# VCFA_v2_mix.net
KiCad netlist of a schematic drawn in EAGLE
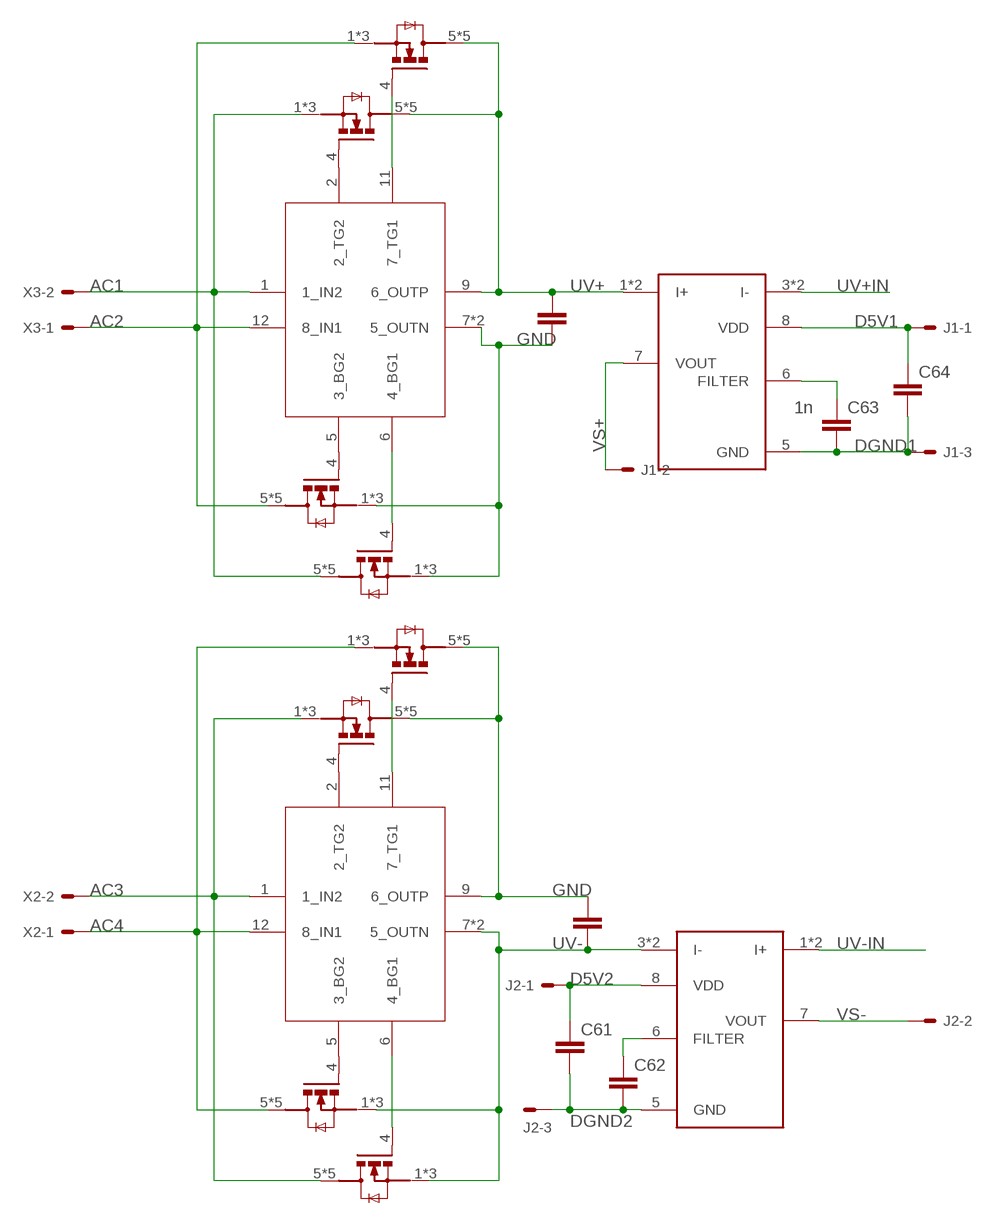
[diagram p0: schematic, sheet 1]
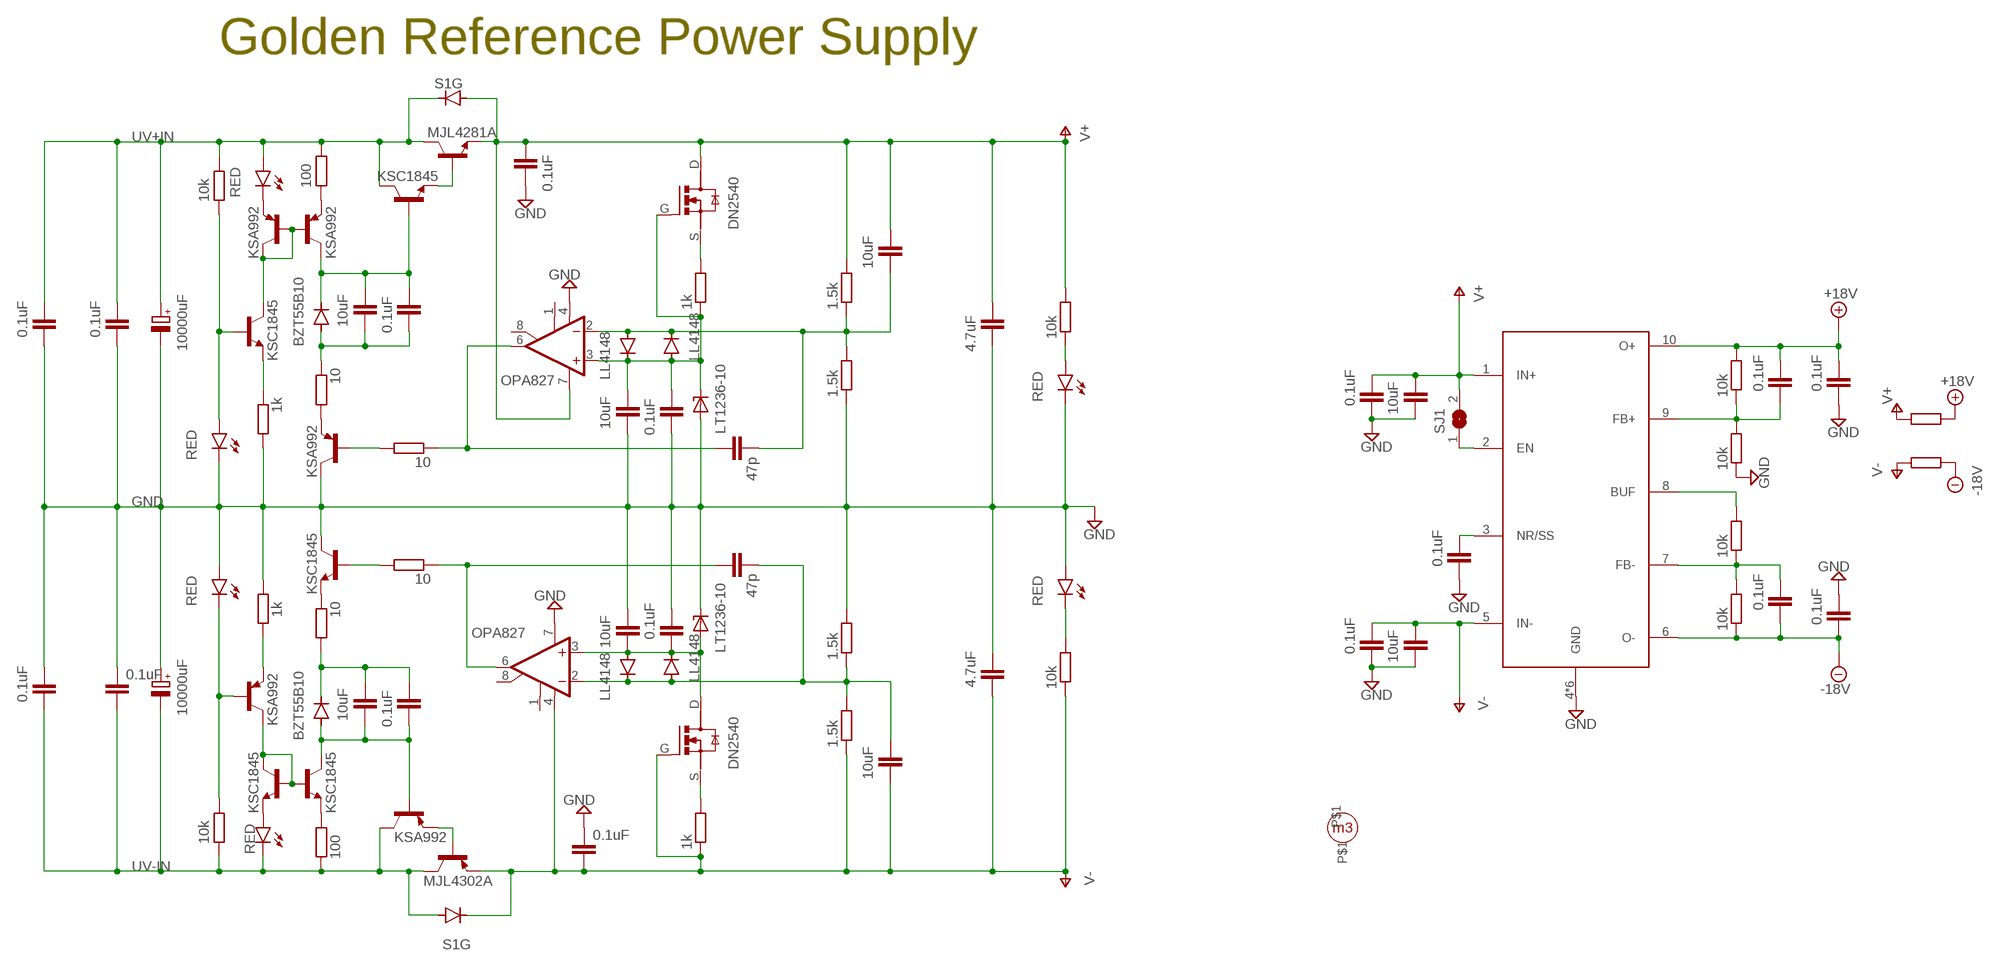
[diagram p1: schematic, sheet 2]
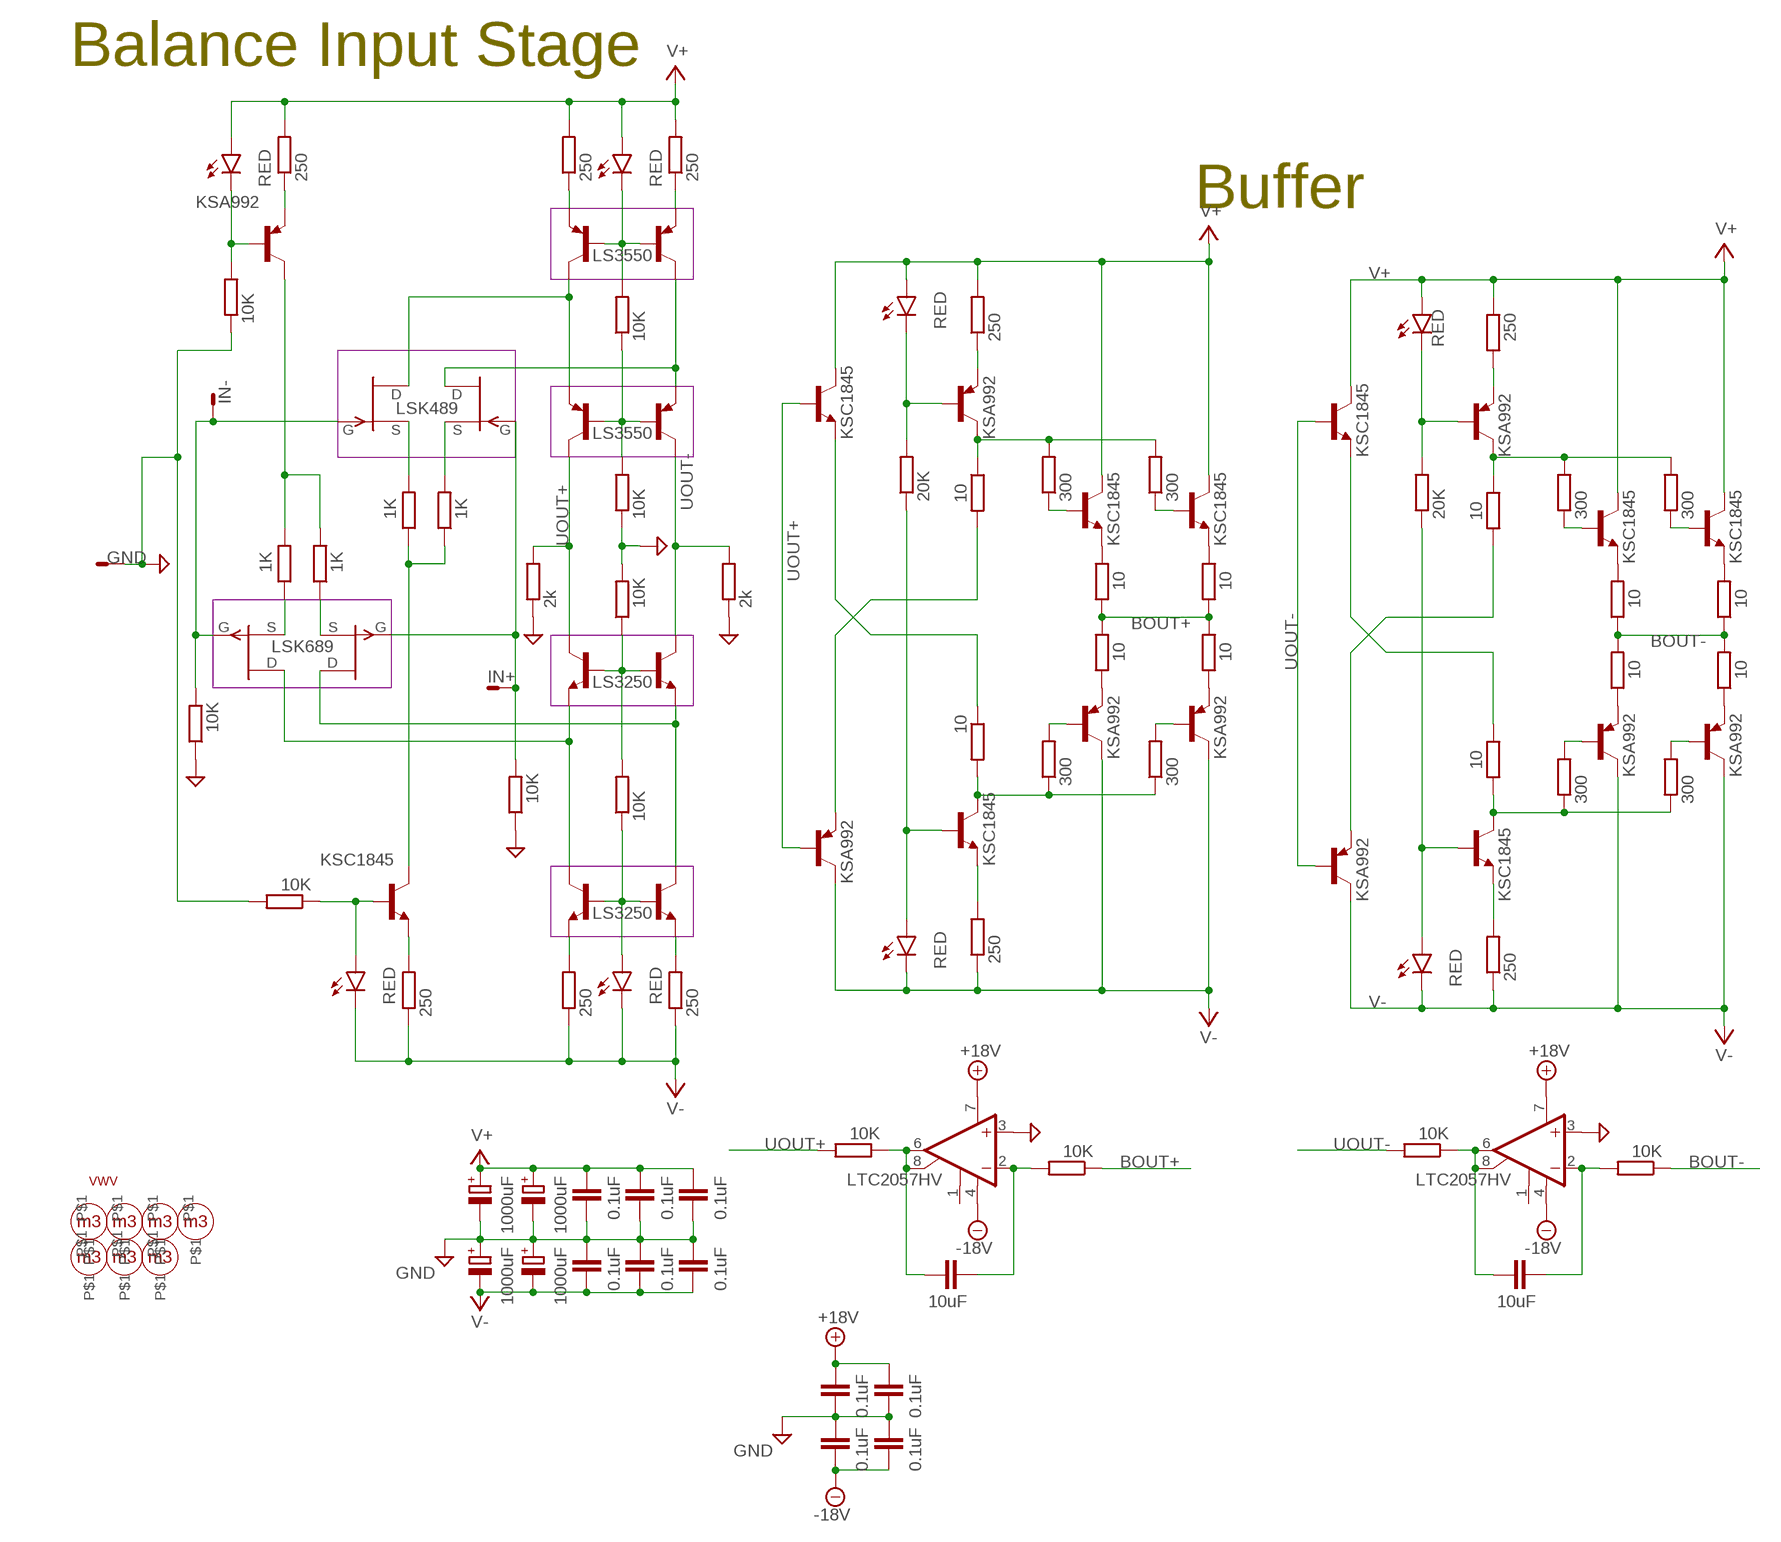
[diagram p2: schematic, sheet 3]
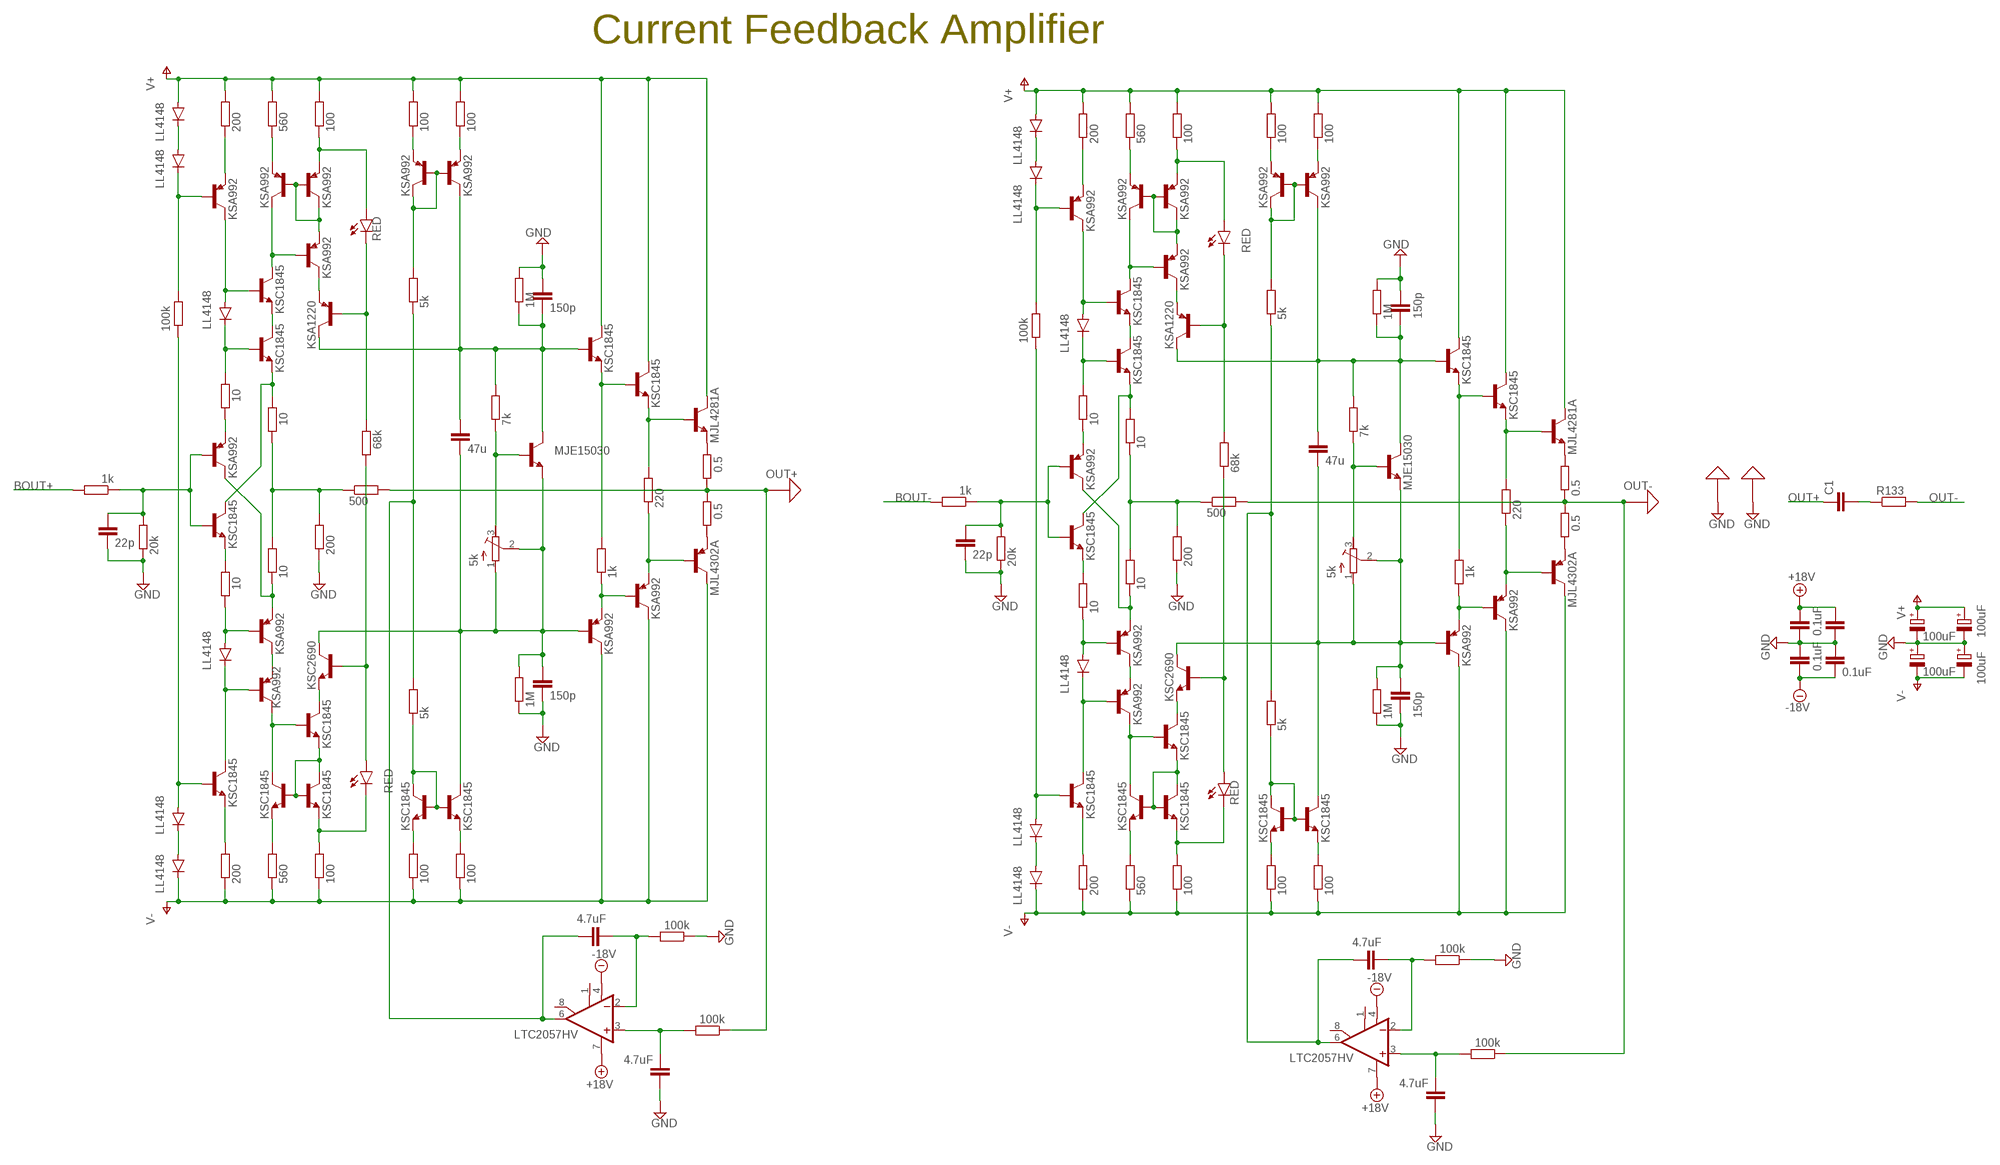
[diagram p3: schematic, sheet 4]

(export (version "E")
  (design (tool "Eeschema 10.0.6"))
  (components
    (comp (ref "C57")
      (value "47uF")
      (footprint "eagle-import:C1206")
      (libsource (lib "eagle-import") (part "C-EUC1206"))
    )
    (comp (ref "C59")
      (value "47uF")
      (footprint "eagle-import:C1206")
      (libsource (lib "eagle-import") (part "C-EUC1206"))
    )
    (comp (ref "C61")
      (value "C-EUC0805")
      (footprint "eagle-import:C0805")
      (libsource (lib "eagle-import") (part "C-EUC0805"))
    )
    (comp (ref "C62")
      (value "C-EUC0805")
      (footprint "eagle-import:C0805")
      (libsource (lib "eagle-import") (part "C-EUC0805"))
    )
    (comp (ref "C63")
      (value "1n")
      (footprint "eagle-import:C0805")
      (libsource (lib "eagle-import") (part "C-EUC0805"))
    )
    (comp (ref "C64")
      (value "C-EUC0805")
      (footprint "eagle-import:C0805")
      (libsource (lib "eagle-import") (part "C-EUC0805"))
    )
    (comp (ref "J1")
      (value "22-27-2031-03")
      (footprint "eagle-import:6410-03")
      (fields (field (name "MF") "MOLEX"))
      (libsource (lib "eagle-import") (part "22-?-0327-2031"))
    )
    (comp (ref "J2")
      (value "22-27-2031-03")
      (footprint "eagle-import:6410-03")
      (fields (field (name "MF") "MOLEX"))
      (libsource (lib "eagle-import") (part "22-?-0327-2031"))
    )
    (comp (ref "Q97")
      (value "MOS_SMDTDSON-8")
      (footprint "eagle-import:PG-TDSON-8")
      (libsource (lib "eagle-import") (part "MOS_SMDTDSON-8"))
    )
    (comp (ref "Q98")
      (value "MOS_SMDTDSON-8")
      (footprint "eagle-import:PG-TDSON-8")
      (libsource (lib "eagle-import") (part "MOS_SMDTDSON-8"))
    )
    (comp (ref "Q99")
      (value "MOS_SMDTDSON-8")
      (footprint "eagle-import:PG-TDSON-8")
      (libsource (lib "eagle-import") (part "MOS_SMDTDSON-8"))
    )
    (comp (ref "Q100")
      (value "MOS_SMDTDSON-8")
      (footprint "eagle-import:PG-TDSON-8")
      (libsource (lib "eagle-import") (part "MOS_SMDTDSON-8"))
    )
    (comp (ref "Q105")
      (value "MOS_SMDTDSON-8")
      (footprint "eagle-import:PG-TDSON-8")
      (libsource (lib "eagle-import") (part "MOS_SMDTDSON-8"))
    )
    (comp (ref "Q106")
      (value "MOS_SMDTDSON-8")
      (footprint "eagle-import:PG-TDSON-8")
      (libsource (lib "eagle-import") (part "MOS_SMDTDSON-8"))
    )
    (comp (ref "Q107")
      (value "MOS_SMDTDSON-8")
      (footprint "eagle-import:PG-TDSON-8")
      (libsource (lib "eagle-import") (part "MOS_SMDTDSON-8"))
    )
    (comp (ref "Q108")
      (value "MOS_SMDTDSON-8")
      (footprint "eagle-import:PG-TDSON-8")
      (libsource (lib "eagle-import") (part "MOS_SMDTDSON-8"))
    )
    (comp (ref "U$1")
      (value "ACHS-712X")
      (footprint "eagle-import:SO8")
      (libsource (lib "eagle-import") (part "ACHS-712X"))
    )
    (comp (ref "U$2")
      (value "LT4320MSOP")
      (footprint "eagle-import:LT4320_MSOP")
      (libsource (lib "eagle-import") (part "LT4320MSOP"))
    )
    (comp (ref "U$3")
      (value "ACHS-712X")
      (footprint "eagle-import:SO8")
      (libsource (lib "eagle-import") (part "ACHS-712X"))
    )
    (comp (ref "U$4")
      (value "LT4320MSOP")
      (footprint "eagle-import:LT4320_MSOP")
      (libsource (lib "eagle-import") (part "LT4320MSOP"))
    )
    (comp (ref "X2")
      (value "KK-156-2")
      (footprint "eagle-import:KK-156-2")
      (fields (field (name "MF") "MOLEX"))
      (libsource (lib "eagle-import") (part "KK-156-2"))
    )
    (comp (ref "X3")
      (value "KK-156-2")
      (footprint "eagle-import:KK-156-2")
      (fields (field (name "MF") "MOLEX"))
      (libsource (lib "eagle-import") (part "KK-156-2"))
    )
    (comp (ref "C3")
      (value "0.1uF")
      (footprint "eagle-import:C0805")
      (libsource (lib "eagle-import") (part "C-EUC0805"))
    )
    (comp (ref "C4")
      (value "0.1uF")
      (footprint "eagle-import:C0805")
      (libsource (lib "eagle-import") (part "C-EUC0805"))
    )
    (comp (ref "C5")
      (value "1000uF")
      (footprint "eagle-import:E7,5-18")
      (libsource (lib "eagle-import") (part "CPOL-EUE7.5-18"))
    )
    (comp (ref "C6")
      (value "1000uF")
      (footprint "eagle-import:E7,5-18")
      (libsource (lib "eagle-import") (part "CPOL-EUE7.5-18"))
    )
    (comp (ref "C7")
      (value "1000uF")
      (footprint "eagle-import:E7,5-18")
      (libsource (lib "eagle-import") (part "CPOL-EUE7.5-18"))
    )
    (comp (ref "C8")
      (value "1000uF")
      (footprint "eagle-import:E7,5-18")
      (libsource (lib "eagle-import") (part "CPOL-EUE7.5-18"))
    )
    (comp (ref "C9")
      (value "0.1uF")
      (footprint "eagle-import:C050-045X075")
      (libsource (lib "eagle-import") (part "C-EU050-045X075"))
    )
    (comp (ref "C10")
      (value "0.1uF")
      (footprint "eagle-import:C050-045X075")
      (libsource (lib "eagle-import") (part "C-EU050-045X075"))
    )
    (comp (ref "C11")
      (value "0.1uF")
      (footprint "eagle-import:C050-045X075")
      (libsource (lib "eagle-import") (part "C-EU050-045X075"))
    )
    (comp (ref "C12")
      (value "0.1uF")
      (footprint "eagle-import:C050-045X075")
      (libsource (lib "eagle-import") (part "C-EU050-045X075"))
    )
    (comp (ref "C13")
      (value "10uF")
      (footprint "eagle-import:C1206")
      (libsource (lib "eagle-import") (part "C-EUC1206"))
    )
    (comp (ref "C14")
      (value "0.1uF")
      (footprint "eagle-import:C0805")
      (libsource (lib "eagle-import") (part "C-EUC0805"))
    )
    (comp (ref "C15")
      (value "0.1uF")
      (footprint "eagle-import:C0805")
      (libsource (lib "eagle-import") (part "C-EUC0805"))
    )
    (comp (ref "C16")
      (value "10uF")
      (footprint "eagle-import:C1206")
      (libsource (lib "eagle-import") (part "C-EUC1206"))
    )
    (comp (ref "C74")
      (value "0.1uF")
      (footprint "eagle-import:C050-045X075")
      (libsource (lib "eagle-import") (part "C-EU050-045X075"))
    )
    (comp (ref "C75")
      (value "0.1uF")
      (footprint "eagle-import:C050-045X075")
      (libsource (lib "eagle-import") (part "C-EU050-045X075"))
    )
    (comp (ref "H1")
      (value "HOLE")
      (footprint "eagle-import:M3_HOLE")
      (libsource (lib "eagle-import") (part "HOLE"))
    )
    (comp (ref "H2")
      (value "HOLE")
      (footprint "eagle-import:M3_HOLE")
      (libsource (lib "eagle-import") (part "HOLE"))
    )
    (comp (ref "H3")
      (value "HOLE")
      (footprint "eagle-import:M3_HOLE")
      (libsource (lib "eagle-import") (part "HOLE"))
    )
    (comp (ref "H4")
      (value "HOLE")
      (footprint "eagle-import:M3_HOLE")
      (libsource (lib "eagle-import") (part "HOLE"))
    )
    (comp (ref "H5")
      (value "HOLE")
      (footprint "eagle-import:M3_HOLE")
      (libsource (lib "eagle-import") (part "HOLE"))
    )
    (comp (ref "H6")
      (value "HOLE")
      (footprint "eagle-import:M3_HOLE")
      (libsource (lib "eagle-import") (part "HOLE"))
    )
    (comp (ref "H7")
      (value "HOLE")
      (footprint "eagle-import:M3_HOLE")
      (libsource (lib "eagle-import") (part "HOLE"))
    )
    (comp (ref "IC1")
      (value "LTC2057HV")
      (footprint "eagle-import:SOIC8")
      (libsource (lib "eagle-import") (part "LT10S807C"))
    )
    (comp (ref "IC2")
      (value "LTC2057HV")
      (footprint "eagle-import:SOIC8")
      (libsource (lib "eagle-import") (part "LT10S807C"))
    )
    (comp (ref "LED1")
      (value "RED")
      (footprint "eagle-import:LED_SML1206")
      (libsource (lib "eagle-import") (part "LEDVWV1206"))
    )
    (comp (ref "LED2")
      (value "RED")
      (footprint "eagle-import:LED_SML1206")
      (fields (field (name "SPICEPREFIX") "D"))
      (libsource (lib "eagle-import") (part "LEDVWV1206"))
    )
    (comp (ref "LED3")
      (value "RED")
      (footprint "eagle-import:LED_SML1206")
      (libsource (lib "eagle-import") (part "LEDVWV1206"))
    )
    (comp (ref "LED4")
      (value "RED")
      (footprint "eagle-import:LED_SML1206")
      (libsource (lib "eagle-import") (part "LEDVWV1206"))
    )
    (comp (ref "LED5")
      (value "RED")
      (footprint "eagle-import:LED_SML1206")
      (libsource (lib "eagle-import") (part "LEDVWV1206"))
    )
    (comp (ref "LED6")
      (value "RED")
      (footprint "eagle-import:LED_SML1206")
      (libsource (lib "eagle-import") (part "LEDVWV1206"))
    )
    (comp (ref "LED7")
      (value "RED")
      (footprint "eagle-import:LED_SML1206")
      (libsource (lib "eagle-import") (part "LEDVWV1206"))
    )
    (comp (ref "LED8")
      (value "RED")
      (footprint "eagle-import:LED_SML1206")
      (libsource (lib "eagle-import") (part "LEDVWV1206"))
    )
    (comp (ref "Q1")
      (value "LSK689")
      (footprint "eagle-import:SOT-23-6")
      (libsource (lib "eagle-import") (part "LSK689"))
    )
    (comp (ref "Q2")
      (value "KSA992")
      (footprint "eagle-import:TRANSISTOR_TO92-ECB_P")
      (libsource (lib "eagle-import") (part "BJT_PNPKSA992"))
    )
    (comp (ref "Q3")
      (value "KSC1845")
      (footprint "eagle-import:TRANSISTOR_TO92-ECB_N")
      (libsource (lib "eagle-import") (part "BJT_NPNKSC1845"))
    )
    (comp (ref "Q4")
      (value "LSK489")
      (footprint "eagle-import:SOT-23-6")
      (libsource (lib "eagle-import") (part "LSK489SOP-6"))
    )
    (comp (ref "Q5")
      (value "LS3550")
      (footprint "eagle-import:SOT-23-6")
      (libsource (lib "eagle-import") (part "LS3550"))
    )
    (comp (ref "Q6")
      (value "LS3250")
      (footprint "eagle-import:SOT-23-6")
      (libsource (lib "eagle-import") (part "LS3250"))
    )
    (comp (ref "Q7")
      (value "LS3250")
      (footprint "eagle-import:SOT-23-6")
      (libsource (lib "eagle-import") (part "LS3250"))
    )
    (comp (ref "Q8")
      (value "LS3550")
      (footprint "eagle-import:SOT-23-6")
      (libsource (lib "eagle-import") (part "LS3550"))
    )
    (comp (ref "Q9")
      (value "KSC1845")
      (footprint "eagle-import:TRANSISTOR_TO92-ECB_N")
      (libsource (lib "eagle-import") (part "BJT_NPNKSC1845"))
    )
    (comp (ref "Q10")
      (value "KSA992")
      (footprint "eagle-import:TRANSISTOR_TO92-ECB_P")
      (libsource (lib "eagle-import") (part "BJT_PNPKSA992"))
    )
    (comp (ref "Q11")
      (value "KSA992")
      (footprint "eagle-import:TRANSISTOR_TO92-ECB_P")
      (libsource (lib "eagle-import") (part "BJT_PNPKSA992"))
    )
    (comp (ref "Q12")
      (value "KSC1845")
      (footprint "eagle-import:TRANSISTOR_TO92-ECB_N")
      (libsource (lib "eagle-import") (part "BJT_NPNKSC1845"))
    )
    (comp (ref "Q13")
      (value "KSC1845")
      (footprint "eagle-import:TRANSISTOR_TO92-ECB_N")
      (libsource (lib "eagle-import") (part "BJT_NPNKSC1845"))
    )
    (comp (ref "Q14")
      (value "KSA992")
      (footprint "eagle-import:TRANSISTOR_TO92-ECB_P")
      (libsource (lib "eagle-import") (part "BJT_PNPKSA992"))
    )
    (comp (ref "Q15")
      (value "KSC1845")
      (footprint "eagle-import:TRANSISTOR_TO92-ECB_N")
      (libsource (lib "eagle-import") (part "BJT_NPNKSC1845"))
    )
    (comp (ref "Q16")
      (value "KSA992")
      (footprint "eagle-import:TRANSISTOR_TO92-ECB_P")
      (libsource (lib "eagle-import") (part "BJT_PNPKSA992"))
    )
    (comp (ref "Q17")
      (value "KSC1845")
      (footprint "eagle-import:TRANSISTOR_TO92-ECB_N")
      (libsource (lib "eagle-import") (part "BJT_NPNKSC1845"))
    )
    (comp (ref "Q18")
      (value "KSA992")
      (footprint "eagle-import:TRANSISTOR_TO92-ECB_P")
      (libsource (lib "eagle-import") (part "BJT_PNPKSA992"))
    )
    (comp (ref "Q19")
      (value "KSA992")
      (footprint "eagle-import:TRANSISTOR_TO92-ECB_P")
      (libsource (lib "eagle-import") (part "BJT_PNPKSA992"))
    )
    (comp (ref "Q20")
      (value "KSC1845")
      (footprint "eagle-import:TRANSISTOR_TO92-ECB_N")
      (libsource (lib "eagle-import") (part "BJT_NPNKSC1845"))
    )
    (comp (ref "Q21")
      (value "KSC1845")
      (footprint "eagle-import:TRANSISTOR_TO92-ECB_N")
      (libsource (lib "eagle-import") (part "BJT_NPNKSC1845"))
    )
    (comp (ref "Q22")
      (value "KSA992")
      (footprint "eagle-import:TRANSISTOR_TO92-ECB_P")
      (libsource (lib "eagle-import") (part "BJT_PNPKSA992"))
    )
    (comp (ref "Q23")
      (value "KSC1845")
      (footprint "eagle-import:TRANSISTOR_TO92-ECB_N")
      (libsource (lib "eagle-import") (part "BJT_NPNKSC1845"))
    )
    (comp (ref "Q24")
      (value "KSA992")
      (footprint "eagle-import:TRANSISTOR_TO92-ECB_P")
      (libsource (lib "eagle-import") (part "BJT_PNPKSA992"))
    )
    (comp (ref "R3")
      (value "10K")
      (footprint "eagle-import:MINI_MELF-0204W")
      (libsource (lib "eagle-import") (part "R-EU_MELF0204W"))
    )
    (comp (ref "R4")
      (value "10K")
      (footprint "eagle-import:MINI_MELF-0204W")
      (libsource (lib "eagle-import") (part "R-EU_MELF0204W"))
    )
    (comp (ref "R5")
      (value "250")
      (footprint "eagle-import:MINI_MELF-0204W")
      (libsource (lib "eagle-import") (part "R-EU_MELF0204W"))
    )
    (comp (ref "R6")
      (value "1K")
      (footprint "eagle-import:MINI_MELF-0204W")
      (libsource (lib "eagle-import") (part "R-EU_MELF0204W"))
    )
    (comp (ref "R7")
      (value "250")
      (footprint "eagle-import:MINI_MELF-0204W")
      (fields (field (name "SPICEPREFIX") "R"))
      (libsource (lib "eagle-import") (part "R-EU_MELF0204W"))
    )
    (comp (ref "R8")
      (value "1K")
      (footprint "eagle-import:MINI_MELF-0204W")
      (libsource (lib "eagle-import") (part "R-EU_MELF0204W"))
    )
    (comp (ref "R9")
      (value "1K")
      (footprint "eagle-import:MINI_MELF-0204W")
      (libsource (lib "eagle-import") (part "R-EU_MELF0204W"))
    )
    (comp (ref "R10")
      (value "1K")
      (footprint "eagle-import:MINI_MELF-0204W")
      (libsource (lib "eagle-import") (part "R-EU_MELF0204W"))
    )
    (comp (ref "R11")
      (value "2k")
      (footprint "eagle-import:MINI_MELF-0204W")
      (libsource (lib "eagle-import") (part "R-EU_MELF0204W"))
    )
    (comp (ref "R12")
      (value "250")
      (footprint "eagle-import:MINI_MELF-0204W")
      (libsource (lib "eagle-import") (part "R-EU_MELF0204W"))
    )
    (comp (ref "R13")
      (value "250")
      (footprint "eagle-import:MINI_MELF-0204W")
      (libsource (lib "eagle-import") (part "R-EU_MELF0204W"))
    )
    (comp (ref "R14")
      (value "10K")
      (footprint "eagle-import:MINI_MELF-0204W")
      (libsource (lib "eagle-import") (part "R-EU_MELF0204W"))
    )
    (comp (ref "R15")
      (value "10K")
      (footprint "eagle-import:MINI_MELF-0204W")
      (libsource (lib "eagle-import") (part "R-EU_MELF0204W"))
    )
    (comp (ref "R16")
      (value "10K")
      (footprint "eagle-import:MINI_MELF-0204W")
      (libsource (lib "eagle-import") (part "R-EU_MELF0204W"))
    )
    (comp (ref "R17")
      (value "10K")
      (footprint "eagle-import:MINI_MELF-0204W")
      (libsource (lib "eagle-import") (part "R-EU_MELF0204W"))
    )
    (comp (ref "R18")
      (value "250")
      (footprint "eagle-import:MINI_MELF-0204W")
      (libsource (lib "eagle-import") (part "R-EU_MELF0204W"))
    )
    (comp (ref "R19")
      (value "250")
      (footprint "eagle-import:MINI_MELF-0204W")
      (libsource (lib "eagle-import") (part "R-EU_MELF0204W"))
    )
    (comp (ref "R20")
      (value "2k")
      (footprint "eagle-import:MINI_MELF-0204W")
      (libsource (lib "eagle-import") (part "R-EU_MELF0204W"))
    )
    (comp (ref "R21")
      (value "10K")
      (footprint "eagle-import:MINI_MELF-0204W")
      (libsource (lib "eagle-import") (part "R-EU_MELF0204W"))
    )
    (comp (ref "R22")
      (value "20K")
      (footprint "eagle-import:MINI_MELF-0204W")
      (libsource (lib "eagle-import") (part "R-EU_MELF0204W"))
    )
    (comp (ref "R23")
      (value "250")
      (footprint "eagle-import:MINI_MELF-0204W")
      (libsource (lib "eagle-import") (part "R-EU_MELF0204W"))
    )
    (comp (ref "R24")
      (value "10")
      (footprint "eagle-import:MINI_MELF-0204W")
      (libsource (lib "eagle-import") (part "R-EU_MELF0204W"))
    )
    (comp (ref "R25")
      (value "10")
      (footprint "eagle-import:MINI_MELF-0204W")
      (libsource (lib "eagle-import") (part "R-EU_MELF0204W"))
    )
    (comp (ref "R26")
      (value "250")
      (footprint "eagle-import:MINI_MELF-0204W")
      (libsource (lib "eagle-import") (part "R-EU_MELF0204W"))
    )
    (comp (ref "R27")
      (value "300")
      (footprint "eagle-import:MINI_MELF-0204W")
      (libsource (lib "eagle-import") (part "R-EU_MELF0204W"))
    )
    (comp (ref "R28")
      (value "300")
      (footprint "eagle-import:MINI_MELF-0204W")
      (libsource (lib "eagle-import") (part "R-EU_MELF0204W"))
    )
    (comp (ref "R29")
      (value "10K")
      (footprint "eagle-import:MINI_MELF-0204W")
      (libsource (lib "eagle-import") (part "R-EU_MELF0204W"))
    )
    (comp (ref "R30")
      (value "10")
      (footprint "eagle-import:MINI_MELF-0204W")
      (libsource (lib "eagle-import") (part "R-EU_MELF0204W"))
    )
    (comp (ref "R31")
      (value "10")
      (footprint "eagle-import:MINI_MELF-0204W")
      (libsource (lib "eagle-import") (part "R-EU_MELF0204W"))
    )
    (comp (ref "R32")
      (value "300")
      (footprint "eagle-import:MINI_MELF-0204W")
      (libsource (lib "eagle-import") (part "R-EU_MELF0204W"))
    )
    (comp (ref "R33")
      (value "300")
      (footprint "eagle-import:MINI_MELF-0204W")
      (libsource (lib "eagle-import") (part "R-EU_MELF0204W"))
    )
    (comp (ref "R34")
      (value "10")
      (footprint "eagle-import:MINI_MELF-0204W")
      (libsource (lib "eagle-import") (part "R-EU_MELF0204W"))
    )
    (comp (ref "R35")
      (value "10")
      (footprint "eagle-import:MINI_MELF-0204W")
      (libsource (lib "eagle-import") (part "R-EU_MELF0204W"))
    )
    (comp (ref "R36")
      (value "10K")
      (footprint "eagle-import:MINI_MELF-0204W")
      (libsource (lib "eagle-import") (part "R-EU_MELF0204W"))
    )
    (comp (ref "R37")
      (value "20K")
      (footprint "eagle-import:MINI_MELF-0204W")
      (libsource (lib "eagle-import") (part "R-EU_MELF0204W"))
    )
    (comp (ref "R38")
      (value "250")
      (footprint "eagle-import:MINI_MELF-0204W")
      (libsource (lib "eagle-import") (part "R-EU_MELF0204W"))
    )
    (comp (ref "R39")
      (value "10")
      (footprint "eagle-import:MINI_MELF-0204W")
      (libsource (lib "eagle-import") (part "R-EU_MELF0204W"))
    )
    (comp (ref "R40")
      (value "10")
      (footprint "eagle-import:MINI_MELF-0204W")
      (libsource (lib "eagle-import") (part "R-EU_MELF0204W"))
    )
    (comp (ref "R41")
      (value "250")
      (footprint "eagle-import:MINI_MELF-0204W")
      (libsource (lib "eagle-import") (part "R-EU_MELF0204W"))
    )
    (comp (ref "R42")
      (value "300")
      (footprint "eagle-import:MINI_MELF-0204W")
      (libsource (lib "eagle-import") (part "R-EU_MELF0204W"))
    )
    (comp (ref "R43")
      (value "300")
      (footprint "eagle-import:MINI_MELF-0204W")
      (libsource (lib "eagle-import") (part "R-EU_MELF0204W"))
    )
    (comp (ref "R44")
      (value "10K")
      (footprint "eagle-import:MINI_MELF-0204W")
      (libsource (lib "eagle-import") (part "R-EU_MELF0204W"))
    )
    (comp (ref "R45")
      (value "10")
      (footprint "eagle-import:MINI_MELF-0204W")
      (libsource (lib "eagle-import") (part "R-EU_MELF0204W"))
    )
    (comp (ref "R46")
      (value "10")
      (footprint "eagle-import:MINI_MELF-0204W")
      (libsource (lib "eagle-import") (part "R-EU_MELF0204W"))
    )
    (comp (ref "R47")
      (value "300")
      (footprint "eagle-import:MINI_MELF-0204W")
      (libsource (lib "eagle-import") (part "R-EU_MELF0204W"))
    )
    (comp (ref "R48")
      (value "300")
      (footprint "eagle-import:MINI_MELF-0204W")
      (libsource (lib "eagle-import") (part "R-EU_MELF0204W"))
    )
    (comp (ref "R49")
      (value "10")
      (footprint "eagle-import:MINI_MELF-0204W")
      (libsource (lib "eagle-import") (part "R-EU_MELF0204W"))
    )
    (comp (ref "R50")
      (value "10")
      (footprint "eagle-import:MINI_MELF-0204W")
      (libsource (lib "eagle-import") (part "R-EU_MELF0204W"))
    )
    (comp (ref "R134")
      (value "10K")
      (footprint "eagle-import:MINI_MELF-0204W")
      (libsource (lib "eagle-import") (part "R-EU_MELF0204W"))
    )
    (comp (ref "R135")
      (value "10K")
      (footprint "eagle-import:MINI_MELF-0204W")
      (libsource (lib "eagle-import") (part "R-EU_MELF0204W"))
    )
    (comp (ref "S1")
      (value "VWV")
      (footprint "eagle-import:VWV")
      (libsource (lib "eagle-import") (part "VWV"))
    )
    (comp (ref "X1")
      (value "KK-156-3")
      (footprint "eagle-import:KK-156-3")
      (fields (field (name "MF") "MOLEX"))
      (libsource (lib "eagle-import") (part "KK-156-3"))
    )
    (comp (ref "C2")
      (value "0.1uF")
      (footprint "eagle-import:C0805")
      (libsource (lib "eagle-import") (part "C-EUC0805"))
    )
    (comp (ref "C37")
      (value "10000uF")
      (footprint "eagle-import:EB35D-8.5")
      (libsource (lib "eagle-import") (part "CPOL-EU"))
    )
    (comp (ref "C38")
      (value "10000uF")
      (footprint "eagle-import:EB35D-8.5")
      (libsource (lib "eagle-import") (part "CPOL-EU"))
    )
    (comp (ref "C39")
      (value "0.1uF")
      (footprint "eagle-import:C050-045X075")
      (libsource (lib "eagle-import") (part "C-EU050-045X075"))
    )
    (comp (ref "C40")
      (value "10uF")
      (footprint "eagle-import:C1206")
      (libsource (lib "eagle-import") (part "C-EUC1206"))
    )
    (comp (ref "C41")
      (value "10uF")
      (footprint "eagle-import:C1206")
      (libsource (lib "eagle-import") (part "C-EUC1206"))
    )
    (comp (ref "C42")
      (value "0.1uF")
      (footprint "eagle-import:C050-045X075")
      (libsource (lib "eagle-import") (part "C-EU050-045X075"))
    )
    (comp (ref "C43")
      (value "0.1uF")
      (footprint "eagle-import:C0805")
      (libsource (lib "eagle-import") (part "C-EUC0805"))
    )
    (comp (ref "C44")
      (value "0.1uF")
      (footprint "eagle-import:C0805")
      (libsource (lib "eagle-import") (part "C-EUC0805"))
    )
    (comp (ref "C45")
      (value "0.1uF")
      (footprint "eagle-import:C0805")
      (libsource (lib "eagle-import") (part "C-EUC0805"))
    )
    (comp (ref "C46")
      (value "0.1uF")
      (footprint "eagle-import:C0805")
      (libsource (lib "eagle-import") (part "C-EUC0805"))
    )
    (comp (ref "C47")
      (value "10uF")
      (footprint "eagle-import:C1206")
      (libsource (lib "eagle-import") (part "C-EUC1206"))
    )
    (comp (ref "C48")
      (value "10uF")
      (footprint "eagle-import:C1206")
      (libsource (lib "eagle-import") (part "C-EUC1206"))
    )
    (comp (ref "C49")
      (value "0.1uF")
      (footprint "eagle-import:C0805")
      (libsource (lib "eagle-import") (part "C-EUC0805"))
    )
    (comp (ref "C50")
      (value "0.1uF")
      (footprint "eagle-import:C0805")
      (libsource (lib "eagle-import") (part "C-EUC0805"))
    )
    (comp (ref "C51")
      (value "47p")
      (footprint "eagle-import:C0805")
      (libsource (lib "eagle-import") (part "C-EUC0805"))
    )
    (comp (ref "C52")
      (value "47p")
      (footprint "eagle-import:C0805")
      (libsource (lib "eagle-import") (part "C-EUC0805"))
    )
    (comp (ref "C53")
      (value "10uF")
      (footprint "eagle-import:C1206")
      (libsource (lib "eagle-import") (part "C-EUC1206"))
    )
    (comp (ref "C54")
      (value "10uF")
      (footprint "eagle-import:C1206")
      (libsource (lib "eagle-import") (part "C-EUC1206"))
    )
    (comp (ref "C55")
      (value "4.7uF")
      (footprint "eagle-import:C050-075X075")
      (libsource (lib "eagle-import") (part "C-EU050-075X075"))
    )
    (comp (ref "C56")
      (value "4.7uF")
      (footprint "eagle-import:C050-075X075")
      (libsource (lib "eagle-import") (part "C-EU050-075X075"))
    )
    (comp (ref "C58")
      (value "0.1uF")
      (footprint "eagle-import:C050-045X075")
      (libsource (lib "eagle-import") (part "C-EU050-045X075"))
    )
    (comp (ref "C60")
      (value "0.1uF")
      (footprint "eagle-import:C050-045X075")
      (libsource (lib "eagle-import") (part "C-EU050-045X075"))
    )
    (comp (ref "C65")
      (value "10uF")
      (footprint "eagle-import:C1206")
      (libsource (lib "eagle-import") (part "C-EUC1206"))
    )
    (comp (ref "C66")
      (value "10uF")
      (footprint "eagle-import:C1206")
      (libsource (lib "eagle-import") (part "C-EUC1206"))
    )
    (comp (ref "C67")
      (value "0.1uF")
      (footprint "eagle-import:C0805")
      (libsource (lib "eagle-import") (part "C-EUC0805"))
    )
    (comp (ref "C68")
      (value "0.1uF")
      (footprint "eagle-import:C0805")
      (libsource (lib "eagle-import") (part "C-EUC0805"))
    )
    (comp (ref "C69")
      (value "0.1uF")
      (footprint "eagle-import:C0805")
      (libsource (lib "eagle-import") (part "C-EUC0805"))
    )
    (comp (ref "C70")
      (value "0.1uF")
      (footprint "eagle-import:C0805")
      (libsource (lib "eagle-import") (part "C-EUC0805"))
    )
    (comp (ref "C71")
      (value "0.1uF")
      (footprint "eagle-import:C0805")
      (libsource (lib "eagle-import") (part "C-EUC0805"))
    )
    (comp (ref "C72")
      (value "0.1uF")
      (footprint "eagle-import:C0805")
      (libsource (lib "eagle-import") (part "C-EUC0805"))
    )
    (comp (ref "D13")
      (value "BZT55B10")
      (footprint "eagle-import:SOD80C")
      (libsource (lib "eagle-import") (part "DIODE-SOD80C"))
    )
    (comp (ref "D14")
      (value "BZT55B10")
      (footprint "eagle-import:SOD80C")
      (libsource (lib "eagle-import") (part "DIODE-SOD80C"))
    )
    (comp (ref "D15")
      (value "S1G")
      (footprint "eagle-import:DO214AA")
      (libsource (lib "eagle-import") (part "DIODE-DO214AA"))
    )
    (comp (ref "D16")
      (value "S1G")
      (footprint "eagle-import:DO214AA")
      (libsource (lib "eagle-import") (part "DIODE-DO214AA"))
    )
    (comp (ref "D17")
      (value "LT1236-10")
      (footprint "eagle-import:SO8")
      (libsource (lib "eagle-import") (part "LINEAR-TECHNOLOGY_LT1021-VSO-8"))
    )
    (comp (ref "D18")
      (value "LT1236-10")
      (footprint "eagle-import:SO8")
      (libsource (lib "eagle-import") (part "LINEAR-TECHNOLOGY_LT1021-VSO-8"))
    )
    (comp (ref "D19")
      (value "LL4148")
      (footprint "eagle-import:SOD80C")
      (fields (field (name "SPICEPREFIX") "D"))
      (libsource (lib "eagle-import") (part "DIODE-SOD80C"))
    )
    (comp (ref "D20")
      (value "LL4148")
      (footprint "eagle-import:SOD80C")
      (fields (field (name "SPICEPREFIX") "D"))
      (libsource (lib "eagle-import") (part "DIODE-SOD80C"))
    )
    (comp (ref "D21")
      (value "LL4148")
      (footprint "eagle-import:SOD80C")
      (fields (field (name "SPICEPREFIX") "D"))
      (libsource (lib "eagle-import") (part "DIODE-SOD80C"))
    )
    (comp (ref "D22")
      (value "LL4148")
      (footprint "eagle-import:SOD80C")
      (fields (field (name "SPICEPREFIX") "D"))
      (libsource (lib "eagle-import") (part "DIODE-SOD80C"))
    )
    (comp (ref "H8")
      (value "HOLE")
      (footprint "eagle-import:M3_HOLE")
      (libsource (lib "eagle-import") (part "HOLE"))
    )
    (comp (ref "IC5")
      (value "OPA827")
      (footprint "eagle-import:SOIC8")
      (libsource (lib "eagle-import") (part "LT10S837C"))
    )
    (comp (ref "IC6")
      (value "OPA827")
      (footprint "eagle-import:SOIC8")
      (libsource (lib "eagle-import") (part "LT10S837C"))
    )
    (comp (ref "LED13")
      (value "RED")
      (footprint "eagle-import:LED_SML1206")
      (libsource (lib "eagle-import") (part "LEDVWV1206"))
    )
    (comp (ref "LED14")
      (value "RED")
      (footprint "eagle-import:LED_SML1206")
      (libsource (lib "eagle-import") (part "LEDVWV1206"))
    )
    (comp (ref "LED15")
      (value "RED")
      (footprint "eagle-import:LED_SML1206")
      (libsource (lib "eagle-import") (part "LEDVWV1206"))
    )
    (comp (ref "LED16")
      (value "RED")
      (footprint "eagle-import:LED_SML1206")
      (libsource (lib "eagle-import") (part "LEDVWV1206"))
    )
    (comp (ref "LED17")
      (value "RED")
      (footprint "eagle-import:LED_SML1206")
      (libsource (lib "eagle-import") (part "LEDVWV1206"))
    )
    (comp (ref "LED18")
      (value "RED")
      (footprint "eagle-import:LED_SML1206")
      (libsource (lib "eagle-import") (part "LEDVWV1206"))
    )
    (comp (ref "Q79")
      (value "KSC1845")
      (footprint "eagle-import:TRANSISTOR_TO92-ECB_N")
      (libsource (lib "eagle-import") (part "BJT_NPNKSC1845"))
    )
    (comp (ref "Q80")
      (value "KSA992")
      (footprint "eagle-import:TRANSISTOR_TO92-ECB_P")
      (libsource (lib "eagle-import") (part "BJT_PNPKSA992"))
    )
    (comp (ref "Q81")
      (value "KSA992")
      (footprint "eagle-import:TRANSISTOR_TO92-ECB_P")
      (libsource (lib "eagle-import") (part "BJT_PNPKSA992"))
    )
    (comp (ref "Q82")
      (value "KSC1845")
      (footprint "eagle-import:TRANSISTOR_TO92-ECB_N")
      (libsource (lib "eagle-import") (part "BJT_NPNKSC1845"))
    )
    (comp (ref "Q83")
      (value "KSA992")
      (footprint "eagle-import:TRANSISTOR_TO92-ECB_P")
      (libsource (lib "eagle-import") (part "BJT_PNPKSA992"))
    )
    (comp (ref "Q84")
      (value "KSC1845")
      (footprint "eagle-import:TRANSISTOR_TO92-ECB_N")
      (libsource (lib "eagle-import") (part "BJT_NPNKSC1845"))
    )
    (comp (ref "Q85")
      (value "KSA992")
      (footprint "eagle-import:TRANSISTOR_TO92-ECB_P")
      (libsource (lib "eagle-import") (part "BJT_PNPKSA992"))
    )
    (comp (ref "Q86")
      (value "KSC1845")
      (footprint "eagle-import:TRANSISTOR_TO92-ECB_N")
      (libsource (lib "eagle-import") (part "BJT_NPNKSC1845"))
    )
    (comp (ref "Q87")
      (value "KSC1845")
      (footprint "eagle-import:TRANSISTOR_TO92-ECB_N")
      (libsource (lib "eagle-import") (part "BJT_NPNKSC1845"))
    )
    (comp (ref "Q88")
      (value "KSA992")
      (footprint "eagle-import:TRANSISTOR_TO92-ECB_P")
      (libsource (lib "eagle-import") (part "BJT_PNPKSA992"))
    )
    (comp (ref "Q89")
      (value "MJL4281A")
      (footprint "eagle-import:TRANSISTOR_TO247_BCE_N")
      (libsource (lib "eagle-import") (part "BJT_NPNMJL4281"))
    )
    (comp (ref "Q90")
      (value "MJL4302A")
      (footprint "eagle-import:TRANSISTOR_TO247_BCE_P")
      (libsource (lib "eagle-import") (part "BJT_PNPMJL4302"))
    )
    (comp (ref "Q91")
      (value "DN2540")
      (footprint "eagle-import:TRANSISTOR_TO92-SGD_N")
      (libsource (lib "eagle-import") (part "DN2540"))
    )
    (comp (ref "Q92")
      (value "DN2540")
      (footprint "eagle-import:TRANSISTOR_TO92-SGD_N")
      (libsource (lib "eagle-import") (part "DN2540"))
    )
    (comp (ref "R115")
      (value "10k")
      (footprint "eagle-import:MINI_MELF-0204W")
      (libsource (lib "eagle-import") (part "R-EU_MELF0204W"))
    )
    (comp (ref "R116")
      (value "10k")
      (footprint "eagle-import:MINI_MELF-0204W")
      (libsource (lib "eagle-import") (part "R-EU_MELF0204W"))
    )
    (comp (ref "R117")
      (value "1k")
      (footprint "eagle-import:MINI_MELF-0204W")
      (libsource (lib "eagle-import") (part "R-EU_MELF0204W"))
    )
    (comp (ref "R118")
      (value "1k")
      (footprint "eagle-import:MINI_MELF-0204W")
      (libsource (lib "eagle-import") (part "R-EU_MELF0204W"))
    )
    (comp (ref "R119")
      (value "100")
      (footprint "eagle-import:MINI_MELF-0204W")
      (libsource (lib "eagle-import") (part "R-EU_MELF0204W"))
    )
    (comp (ref "R120")
      (value "10")
      (footprint "eagle-import:MINI_MELF-0204W")
      (libsource (lib "eagle-import") (part "R-EU_MELF0204W"))
    )
    (comp (ref "R121")
      (value "10")
      (footprint "eagle-import:MINI_MELF-0204W")
      (libsource (lib "eagle-import") (part "R-EU_MELF0204W"))
    )
    (comp (ref "R122")
      (value "100")
      (footprint "eagle-import:MINI_MELF-0204W")
      (libsource (lib "eagle-import") (part "R-EU_MELF0204W"))
    )
    (comp (ref "R123")
      (value "10")
      (footprint "eagle-import:MINI_MELF-0204W")
      (libsource (lib "eagle-import") (part "R-EU_MELF0204W"))
    )
    (comp (ref "R124")
      (value "10")
      (footprint "eagle-import:MINI_MELF-0204W")
      (libsource (lib "eagle-import") (part "R-EU_MELF0204W"))
    )
    (comp (ref "R125")
      (value "1k")
      (footprint "eagle-import:MINI_MELF-0204W")
      (libsource (lib "eagle-import") (part "R-EU_MELF0204W"))
    )
    (comp (ref "R126")
      (value "1k")
      (footprint "eagle-import:MINI_MELF-0204W")
      (libsource (lib "eagle-import") (part "R-EU_MELF0204W"))
    )
    (comp (ref "R127")
      (value "1.5k")
      (footprint "eagle-import:MINI_MELF-0204W")
      (libsource (lib "eagle-import") (part "R-EU_MELF0204W"))
    )
    (comp (ref "R128")
      (value "1.5k")
      (footprint "eagle-import:MINI_MELF-0204W")
      (libsource (lib "eagle-import") (part "R-EU_MELF0204W"))
    )
    (comp (ref "R129")
      (value "1.5k")
      (footprint "eagle-import:MINI_MELF-0204W")
      (libsource (lib "eagle-import") (part "R-EU_MELF0204W"))
    )
    (comp (ref "R130")
      (value "1.5k")
      (footprint "eagle-import:MINI_MELF-0204W")
      (libsource (lib "eagle-import") (part "R-EU_MELF0204W"))
    )
    (comp (ref "R131")
      (value "10k")
      (footprint "eagle-import:MINI_MELF-0204W")
      (libsource (lib "eagle-import") (part "R-EU_MELF0204W"))
    )
    (comp (ref "R132")
      (value "10k")
      (footprint "eagle-import:MINI_MELF-0204W")
      (libsource (lib "eagle-import") (part "R-EU_MELF0204W"))
    )
    (comp (ref "R136")
      (value "10k")
      (footprint "eagle-import:MINI_MELF-0204W")
      (libsource (lib "eagle-import") (part "R-EU_MELF0204W"))
    )
    (comp (ref "R137")
      (value "10k")
      (footprint "eagle-import:MINI_MELF-0204W")
      (libsource (lib "eagle-import") (part "R-EU_MELF0204W"))
    )
    (comp (ref "R138")
      (value "10k")
      (footprint "eagle-import:MINI_MELF-0204W")
      (libsource (lib "eagle-import") (part "R-EU_MELF0204W"))
    )
    (comp (ref "R139")
      (value "10k")
      (footprint "eagle-import:MINI_MELF-0204W")
      (libsource (lib "eagle-import") (part "R-EU_MELF0204W"))
    )
    (comp (ref "R140")
      (value "10k")
      (footprint "eagle-import:MINI_MELF-0204W")
      (libsource (lib "eagle-import") (part "R-EU_MELF0204W"))
    )
    (comp (ref "R141")
      (value "10k")
      (footprint "eagle-import:MINI_MELF-0204W")
      (libsource (lib "eagle-import") (part "R-EU_MELF0204W"))
    )
    (comp (ref "SJ1") (value "SJ") (footprint "eagle-import:SJ") (libsource (lib "eagle-import") (part "SJ")))
    (comp (ref "U$5")
      (value "TPS7A39WSON10-7A39")
      (footprint "eagle-import:SON50P300X300X80-11T165X240N")
      (libsource (lib "eagle-import") (part "TPS7A39WSON10-7A39"))
    )
    (comp (ref "C1")
      (value "C-EUECWU-V")
      (footprint "eagle-import:ECHU-Y")
      (libsource (lib "eagle-import") (part "C-EUECWU-V"))
    )
    (comp (ref "C17")
      (value "22p")
      (footprint "eagle-import:C0805")
      (fields (field (name "SPICEPREFIX") "C"))
      (libsource (lib "eagle-import") (part "C-EUC0805"))
    )
    (comp (ref "C18")
      (value "47u")
      (footprint "eagle-import:C1210")
      (fields (field (name "SPICEPREFIX") "C"))
      (libsource (lib "eagle-import") (part "C-EUC1210"))
    )
    (comp (ref "C19")
      (value "150p")
      (footprint "eagle-import:C0805")
      (fields (field (name "SPICEPREFIX") "C"))
      (libsource (lib "eagle-import") (part "C-EUC0805"))
    )
    (comp (ref "C20")
      (value "150p")
      (footprint "eagle-import:C0805")
      (fields (field (name "SPICEPREFIX") "C"))
      (libsource (lib "eagle-import") (part "C-EUC0805"))
    )
    (comp (ref "C21")
      (value "4.7uF")
      (footprint "eagle-import:C1210")
      (fields (field (name "SPICEPREFIX") "C"))
      (libsource (lib "eagle-import") (part "C-EUC1210"))
    )
    (comp (ref "C22")
      (value "4.7uF")
      (footprint "eagle-import:C1210")
      (fields (field (name "SPICEPREFIX") "C"))
      (libsource (lib "eagle-import") (part "C-EUC1210"))
    )
    (comp (ref "C23")
      (value "0.1uF")
      (footprint "eagle-import:C0603K")
      (libsource (lib "eagle-import") (part "C-EUC0603K"))
    )
    (comp (ref "C24")
      (value "0.1uF")
      (footprint "eagle-import:C0603K")
      (libsource (lib "eagle-import") (part "C-EUC0603K"))
    )
    (comp (ref "C25")
      (value "100uF")
      (footprint "eagle-import:E5-8,5")
      (libsource (lib "eagle-import") (part "CPOL-EUE5-8.5"))
    )
    (comp (ref "C26")
      (value "100uF")
      (footprint "eagle-import:E5-8,5")
      (libsource (lib "eagle-import") (part "CPOL-EUE5-8.5"))
    )
    (comp (ref "C27")
      (value "22p")
      (footprint "eagle-import:C0805")
      (fields (field (name "SPICEPREFIX") "C"))
      (libsource (lib "eagle-import") (part "C-EUC0805"))
    )
    (comp (ref "C28")
      (value "47u")
      (footprint "eagle-import:C1210")
      (fields (field (name "SPICEPREFIX") "C"))
      (libsource (lib "eagle-import") (part "C-EUC1210"))
    )
    (comp (ref "C29")
      (value "150p")
      (footprint "eagle-import:C0805")
      (fields (field (name "SPICEPREFIX") "C"))
      (libsource (lib "eagle-import") (part "C-EUC0805"))
    )
    (comp (ref "C30")
      (value "150p")
      (footprint "eagle-import:C0805")
      (fields (field (name "SPICEPREFIX") "C"))
      (libsource (lib "eagle-import") (part "C-EUC0805"))
    )
    (comp (ref "C31")
      (value "4.7uF")
      (footprint "eagle-import:C1210")
      (fields (field (name "SPICEPREFIX") "C"))
      (libsource (lib "eagle-import") (part "C-EUC1210"))
    )
    (comp (ref "C32")
      (value "4.7uF")
      (footprint "eagle-import:C1210")
      (fields (field (name "SPICEPREFIX") "C"))
      (libsource (lib "eagle-import") (part "C-EUC1210"))
    )
    (comp (ref "C33")
      (value "0.1uF")
      (footprint "eagle-import:C0603K")
      (libsource (lib "eagle-import") (part "C-EUC0603K"))
    )
    (comp (ref "C34")
      (value "0.1uF")
      (footprint "eagle-import:C0603K")
      (libsource (lib "eagle-import") (part "C-EUC0603K"))
    )
    (comp (ref "C35")
      (value "100uF")
      (footprint "eagle-import:E5-8,5")
      (libsource (lib "eagle-import") (part "CPOL-EUE5-8.5"))
    )
    (comp (ref "C36")
      (value "100uF")
      (footprint "eagle-import:E5-8,5")
      (libsource (lib "eagle-import") (part "CPOL-EUE5-8.5"))
    )
    (comp (ref "D1")
      (value "LL4148")
      (footprint "eagle-import:SOD80C")
      (fields (field (name "SPICEPREFIX") "D"))
      (libsource (lib "eagle-import") (part "DIODE-SOD80C"))
    )
    (comp (ref "D2")
      (value "LL4148")
      (footprint "eagle-import:SOD80C")
      (fields (field (name "SPICEPREFIX") "D"))
      (libsource (lib "eagle-import") (part "DIODE-SOD80C"))
    )
    (comp (ref "D3")
      (value "LL4148")
      (footprint "eagle-import:SOD80C")
      (fields (field (name "SPICEPREFIX") "D"))
      (libsource (lib "eagle-import") (part "DIODE-SOD80C"))
    )
    (comp (ref "D4")
      (value "LL4148")
      (footprint "eagle-import:SOD80C")
      (fields (field (name "SPICEPREFIX") "D"))
      (libsource (lib "eagle-import") (part "DIODE-SOD80C"))
    )
    (comp (ref "D5")
      (value "LL4148")
      (footprint "eagle-import:SOD80C")
      (fields (field (name "SPICEPREFIX") "D"))
      (libsource (lib "eagle-import") (part "DIODE-SOD80C"))
    )
    (comp (ref "D6")
      (value "LL4148")
      (footprint "eagle-import:SOD80C")
      (fields (field (name "SPICEPREFIX") "D"))
      (libsource (lib "eagle-import") (part "DIODE-SOD80C"))
    )
    (comp (ref "D7")
      (value "LL4148")
      (footprint "eagle-import:SOD80C")
      (fields (field (name "SPICEPREFIX") "D"))
      (libsource (lib "eagle-import") (part "DIODE-SOD80C"))
    )
    (comp (ref "D8")
      (value "LL4148")
      (footprint "eagle-import:SOD80C")
      (fields (field (name "SPICEPREFIX") "D"))
      (libsource (lib "eagle-import") (part "DIODE-SOD80C"))
    )
    (comp (ref "D9")
      (value "LL4148")
      (footprint "eagle-import:SOD80C")
      (fields (field (name "SPICEPREFIX") "D"))
      (libsource (lib "eagle-import") (part "DIODE-SOD80C"))
    )
    (comp (ref "D10")
      (value "LL4148")
      (footprint "eagle-import:SOD80C")
      (fields (field (name "SPICEPREFIX") "D"))
      (libsource (lib "eagle-import") (part "DIODE-SOD80C"))
    )
    (comp (ref "D11")
      (value "LL4148")
      (footprint "eagle-import:SOD80C")
      (fields (field (name "SPICEPREFIX") "D"))
      (libsource (lib "eagle-import") (part "DIODE-SOD80C"))
    )
    (comp (ref "D12")
      (value "LL4148")
      (footprint "eagle-import:SOD80C")
      (fields (field (name "SPICEPREFIX") "D"))
      (libsource (lib "eagle-import") (part "DIODE-SOD80C"))
    )
    (comp (ref "IC3")
      (value "LTC2057HV")
      (footprint "eagle-import:SOIC8")
      (libsource (lib "eagle-import") (part "LT10S837I"))
    )
    (comp (ref "IC4")
      (value "LTC2057HV")
      (footprint "eagle-import:SOIC8")
      (libsource (lib "eagle-import") (part "LT10S837I"))
    )
    (comp (ref "LED9")
      (value "RED")
      (footprint "eagle-import:LED_SML1206")
      (fields (field (name "SPICEPREFIX") "D"))
      (libsource (lib "eagle-import") (part "LEDVWV1206"))
    )
    (comp (ref "LED10")
      (value "RED")
      (footprint "eagle-import:LED_SML1206")
      (fields (field (name "SPICEPREFIX") "D"))
      (libsource (lib "eagle-import") (part "LEDVWV1206"))
    )
    (comp (ref "LED11")
      (value "RED")
      (footprint "eagle-import:LED_SML1206")
      (fields (field (name "SPICEPREFIX") "D"))
      (libsource (lib "eagle-import") (part "LEDVWV1206"))
    )
    (comp (ref "LED12")
      (value "RED")
      (footprint "eagle-import:LED_SML1206")
      (fields (field (name "SPICEPREFIX") "D"))
      (libsource (lib "eagle-import") (part "LEDVWV1206"))
    )
    (comp (ref "PAD1")
      (value "PAD")
      (footprint "eagle-import:PAD-16")
      (libsource (lib "eagle-import") (part "PAD"))
    )
    (comp (ref "PAD2")
      (value "PAD")
      (footprint "eagle-import:PAD-16")
      (libsource (lib "eagle-import") (part "PAD"))
    )
    (comp (ref "PAD3")
      (value "PAD")
      (footprint "eagle-import:PAD-16")
      (libsource (lib "eagle-import") (part "PAD"))
    )
    (comp (ref "PAD4")
      (value "PAD")
      (footprint "eagle-import:PAD-16")
      (libsource (lib "eagle-import") (part "PAD"))
    )
    (comp (ref "Q25")
      (value "KSA992")
      (footprint "eagle-import:TRANSISTOR_TO92-ECB_P")
      (fields (field (name "SPICEPREFIX") "Q"))
      (libsource (lib "eagle-import") (part "BJT_PNPKSA992"))
    )
    (comp (ref "Q26")
      (value "KSA992")
      (footprint "eagle-import:TRANSISTOR_TO92-ECB_P")
      (fields (field (name "SPICEPREFIX") "Q"))
      (libsource (lib "eagle-import") (part "BJT_PNPKSA992"))
    )
    (comp (ref "Q27")
      (value "KSC1845")
      (footprint "eagle-import:TRANSISTOR_TO92-ECB_N")
      (fields (field (name "SPICEPREFIX") "Q"))
      (libsource (lib "eagle-import") (part "BJT_NPNKSC1845"))
    )
    (comp (ref "Q28")
      (value "KSC1845")
      (footprint "eagle-import:TRANSISTOR_TO92-ECB_N")
      (fields (field (name "SPICEPREFIX") "Q"))
      (libsource (lib "eagle-import") (part "BJT_NPNKSC1845"))
    )
    (comp (ref "Q29")
      (value "KSC1845")
      (footprint "eagle-import:TRANSISTOR_TO92-ECB_N")
      (fields (field (name "SPICEPREFIX") "Q"))
      (libsource (lib "eagle-import") (part "BJT_NPNKSC1845"))
    )
    (comp (ref "Q30")
      (value "KSC1845")
      (footprint "eagle-import:TRANSISTOR_TO92-ECB_N")
      (fields (field (name "SPICEPREFIX") "Q"))
      (libsource (lib "eagle-import") (part "BJT_NPNKSC1845"))
    )
    (comp (ref "Q31")
      (value "KSA992")
      (footprint "eagle-import:TRANSISTOR_TO92-ECB_P")
      (fields (field (name "SPICEPREFIX") "Q"))
      (libsource (lib "eagle-import") (part "BJT_PNPKSA992"))
    )
    (comp (ref "Q32")
      (value "KSA992")
      (footprint "eagle-import:TRANSISTOR_TO92-ECB_P")
      (fields (field (name "SPICEPREFIX") "Q"))
      (libsource (lib "eagle-import") (part "BJT_PNPKSA992"))
    )
    (comp (ref "Q33")
      (value "KSA992")
      (footprint "eagle-import:TRANSISTOR_TO92-ECB_P")
      (fields (field (name "SPICEPREFIX") "Q"))
      (libsource (lib "eagle-import") (part "BJT_PNPKSA992"))
    )
    (comp (ref "Q34")
      (value "KSC1845")
      (footprint "eagle-import:TRANSISTOR_TO92-ECB_N")
      (fields (field (name "SPICEPREFIX") "Q"))
      (libsource (lib "eagle-import") (part "BJT_NPNKSC1845"))
    )
    (comp (ref "Q35")
      (value "KSA992")
      (footprint "eagle-import:TRANSISTOR_TO92-ECB_P")
      (fields (field (name "SPICEPREFIX") "Q"))
      (libsource (lib "eagle-import") (part "BJT_PNPKSA992"))
    )
    (comp (ref "Q36")
      (value "KSA992")
      (footprint "eagle-import:TRANSISTOR_TO92-ECB_P")
      (fields (field (name "SPICEPREFIX") "Q"))
      (libsource (lib "eagle-import") (part "BJT_PNPKSA992"))
    )
    (comp (ref "Q37")
      (value "KSC1845")
      (footprint "eagle-import:TRANSISTOR_TO92-ECB_N")
      (fields (field (name "SPICEPREFIX") "Q"))
      (libsource (lib "eagle-import") (part "BJT_NPNKSC1845"))
    )
    (comp (ref "Q38")
      (value "KSC1845")
      (footprint "eagle-import:TRANSISTOR_TO92-ECB_N")
      (fields (field (name "SPICEPREFIX") "Q"))
      (libsource (lib "eagle-import") (part "BJT_NPNKSC1845"))
    )
    (comp (ref "Q39")
      (value "KSA1220")
      (footprint "eagle-import:TRANSISTOR_TO126_P")
      (fields (field (name "SPICEPREFIX") "Q"))
      (libsource (lib "eagle-import") (part "BJT_PNPKSA1220"))
    )
    (comp (ref "Q40")
      (value "KSC2690")
      (footprint "eagle-import:TRANSISTOR_TO126_N")
      (fields (field (name "SPICEPREFIX") "Q"))
      (libsource (lib "eagle-import") (part "BJT_NPNKSC2690"))
    )
    (comp (ref "Q41")
      (value "KSA992")
      (footprint "eagle-import:TRANSISTOR_TO92-ECB_P")
      (fields (field (name "SPICEPREFIX") "Q"))
      (libsource (lib "eagle-import") (part "BJT_PNPKSA992"))
    )
    (comp (ref "Q42")
      (value "KSC1845")
      (footprint "eagle-import:TRANSISTOR_TO92-ECB_N")
      (fields (field (name "SPICEPREFIX") "Q"))
      (libsource (lib "eagle-import") (part "BJT_NPNKSC1845"))
    )
    (comp (ref "Q43")
      (value "KSA992")
      (footprint "eagle-import:TRANSISTOR_TO92-ECB_P")
      (fields (field (name "SPICEPREFIX") "Q"))
      (libsource (lib "eagle-import") (part "BJT_PNPKSA992"))
    )
    (comp (ref "Q44")
      (value "KSC1845")
      (footprint "eagle-import:TRANSISTOR_TO92-ECB_N")
      (fields (field (name "SPICEPREFIX") "Q"))
      (libsource (lib "eagle-import") (part "BJT_NPNKSC1845"))
    )
    (comp (ref "Q45")
      (value "MJE15030")
      (footprint "eagle-import:TRANSISTOR_TO220_BCE_N")
      (fields (field (name "SPICEPREFIX") "Q"))
      (libsource (lib "eagle-import") (part "BJT_NPNMJE15030"))
    )
    (comp (ref "Q46")
      (value "KSC1845")
      (footprint "eagle-import:TRANSISTOR_TO92-ECB_N")
      (fields (field (name "SPICEPREFIX") "Q"))
      (libsource (lib "eagle-import") (part "BJT_NPNKSC1845"))
    )
    (comp (ref "Q47")
      (value "KSA992")
      (footprint "eagle-import:TRANSISTOR_TO92-ECB_P")
      (fields (field (name "SPICEPREFIX") "Q"))
      (libsource (lib "eagle-import") (part "BJT_PNPKSA992"))
    )
    (comp (ref "Q48")
      (value "KSC1845")
      (footprint "eagle-import:TRANSISTOR_TO92-ECB_N")
      (fields (field (name "SPICEPREFIX") "Q"))
      (libsource (lib "eagle-import") (part "BJT_NPNKSC1845"))
    )
    (comp (ref "Q49")
      (value "KSA992")
      (footprint "eagle-import:TRANSISTOR_TO92-ECB_P")
      (fields (field (name "SPICEPREFIX") "Q"))
      (libsource (lib "eagle-import") (part "BJT_PNPKSA992"))
    )
    (comp (ref "Q50")
      (value "MJL4281A")
      (footprint "eagle-import:TRANSISTOR_TO247_BCE_N")
      (fields (field (name "SPICEPREFIX") "Q"))
      (libsource (lib "eagle-import") (part "BJT_NPNMJL4281"))
    )
    (comp (ref "Q51")
      (value "MJL4302A")
      (footprint "eagle-import:TRANSISTOR_TO247_BCE_P")
      (fields (field (name "SPICEPREFIX") "Q"))
      (libsource (lib "eagle-import") (part "BJT_PNPMJL4302"))
    )
    (comp (ref "Q52")
      (value "KSA992")
      (footprint "eagle-import:TRANSISTOR_TO92-ECB_P")
      (fields (field (name "SPICEPREFIX") "Q"))
      (libsource (lib "eagle-import") (part "BJT_PNPKSA992"))
    )
    (comp (ref "Q53")
      (value "KSA992")
      (footprint "eagle-import:TRANSISTOR_TO92-ECB_P")
      (fields (field (name "SPICEPREFIX") "Q"))
      (libsource (lib "eagle-import") (part "BJT_PNPKSA992"))
    )
    (comp (ref "Q54")
      (value "KSC1845")
      (footprint "eagle-import:TRANSISTOR_TO92-ECB_N")
      (fields (field (name "SPICEPREFIX") "Q"))
      (libsource (lib "eagle-import") (part "BJT_NPNKSC1845"))
    )
    (comp (ref "Q55")
      (value "KSC1845")
      (footprint "eagle-import:TRANSISTOR_TO92-ECB_N")
      (fields (field (name "SPICEPREFIX") "Q"))
      (libsource (lib "eagle-import") (part "BJT_NPNKSC1845"))
    )
    (comp (ref "Q56")
      (value "KSC1845")
      (footprint "eagle-import:TRANSISTOR_TO92-ECB_N")
      (fields (field (name "SPICEPREFIX") "Q"))
      (libsource (lib "eagle-import") (part "BJT_NPNKSC1845"))
    )
    (comp (ref "Q57")
      (value "KSC1845")
      (footprint "eagle-import:TRANSISTOR_TO92-ECB_N")
      (fields (field (name "SPICEPREFIX") "Q"))
      (libsource (lib "eagle-import") (part "BJT_NPNKSC1845"))
    )
    (comp (ref "Q58")
      (value "KSA992")
      (footprint "eagle-import:TRANSISTOR_TO92-ECB_P")
      (fields (field (name "SPICEPREFIX") "Q"))
      (libsource (lib "eagle-import") (part "BJT_PNPKSA992"))
    )
    (comp (ref "Q59")
      (value "KSA992")
      (footprint "eagle-import:TRANSISTOR_TO92-ECB_P")
      (fields (field (name "SPICEPREFIX") "Q"))
      (libsource (lib "eagle-import") (part "BJT_PNPKSA992"))
    )
    (comp (ref "Q60")
      (value "KSA992")
      (footprint "eagle-import:TRANSISTOR_TO92-ECB_P")
      (fields (field (name "SPICEPREFIX") "Q"))
      (libsource (lib "eagle-import") (part "BJT_PNPKSA992"))
    )
    (comp (ref "Q61")
      (value "KSC1845")
      (footprint "eagle-import:TRANSISTOR_TO92-ECB_N")
      (fields (field (name "SPICEPREFIX") "Q"))
      (libsource (lib "eagle-import") (part "BJT_NPNKSC1845"))
    )
    (comp (ref "Q62")
      (value "KSA992")
      (footprint "eagle-import:TRANSISTOR_TO92-ECB_P")
      (fields (field (name "SPICEPREFIX") "Q"))
      (libsource (lib "eagle-import") (part "BJT_PNPKSA992"))
    )
    (comp (ref "Q63")
      (value "KSA992")
      (footprint "eagle-import:TRANSISTOR_TO92-ECB_P")
      (fields (field (name "SPICEPREFIX") "Q"))
      (libsource (lib "eagle-import") (part "BJT_PNPKSA992"))
    )
    (comp (ref "Q64")
      (value "KSC1845")
      (footprint "eagle-import:TRANSISTOR_TO92-ECB_N")
      (fields (field (name "SPICEPREFIX") "Q"))
      (libsource (lib "eagle-import") (part "BJT_NPNKSC1845"))
    )
    (comp (ref "Q65")
      (value "KSC1845")
      (footprint "eagle-import:TRANSISTOR_TO92-ECB_N")
      (fields (field (name "SPICEPREFIX") "Q"))
      (libsource (lib "eagle-import") (part "BJT_NPNKSC1845"))
    )
    (comp (ref "Q66")
      (value "KSA1220")
      (footprint "eagle-import:TRANSISTOR_TO126_P")
      (fields (field (name "SPICEPREFIX") "Q"))
      (libsource (lib "eagle-import") (part "BJT_PNPKSA1220"))
    )
    (comp (ref "Q67")
      (value "KSC2690")
      (footprint "eagle-import:TRANSISTOR_TO126_N")
      (fields (field (name "SPICEPREFIX") "Q"))
      (libsource (lib "eagle-import") (part "BJT_NPNKSC2690"))
    )
    (comp (ref "Q68")
      (value "KSA992")
      (footprint "eagle-import:TRANSISTOR_TO92-ECB_P")
      (fields (field (name "SPICEPREFIX") "Q"))
      (libsource (lib "eagle-import") (part "BJT_PNPKSA992"))
    )
    (comp (ref "Q69")
      (value "KSC1845")
      (footprint "eagle-import:TRANSISTOR_TO92-ECB_N")
      (fields (field (name "SPICEPREFIX") "Q"))
      (libsource (lib "eagle-import") (part "BJT_NPNKSC1845"))
    )
    (comp (ref "Q70")
      (value "KSA992")
      (footprint "eagle-import:TRANSISTOR_TO92-ECB_P")
      (fields (field (name "SPICEPREFIX") "Q"))
      (libsource (lib "eagle-import") (part "BJT_PNPKSA992"))
    )
    (comp (ref "Q71")
      (value "KSC1845")
      (footprint "eagle-import:TRANSISTOR_TO92-ECB_N")
      (fields (field (name "SPICEPREFIX") "Q"))
      (libsource (lib "eagle-import") (part "BJT_NPNKSC1845"))
    )
    (comp (ref "Q72")
      (value "MJE15030")
      (footprint "eagle-import:TRANSISTOR_TO220_BCE_N")
      (fields (field (name "SPICEPREFIX") "Q"))
      (libsource (lib "eagle-import") (part "BJT_NPNMJE15030"))
    )
    (comp (ref "Q73")
      (value "KSC1845")
      (footprint "eagle-import:TRANSISTOR_TO92-ECB_N")
      (fields (field (name "SPICEPREFIX") "Q"))
      (libsource (lib "eagle-import") (part "BJT_NPNKSC1845"))
    )
    (comp (ref "Q74")
      (value "KSA992")
      (footprint "eagle-import:TRANSISTOR_TO92-ECB_P")
      (fields (field (name "SPICEPREFIX") "Q"))
      (libsource (lib "eagle-import") (part "BJT_PNPKSA992"))
    )
    (comp (ref "Q75")
      (value "KSC1845")
      (footprint "eagle-import:TRANSISTOR_TO92-ECB_N")
      (fields (field (name "SPICEPREFIX") "Q"))
      (libsource (lib "eagle-import") (part "BJT_NPNKSC1845"))
    )
    (comp (ref "Q76")
      (value "KSA992")
      (footprint "eagle-import:TRANSISTOR_TO92-ECB_P")
      (fields (field (name "SPICEPREFIX") "Q"))
      (libsource (lib "eagle-import") (part "BJT_PNPKSA992"))
    )
    (comp (ref "Q77")
      (value "MJL4281A")
      (footprint "eagle-import:TRANSISTOR_TO247_BCE_N")
      (fields (field (name "SPICEPREFIX") "Q"))
      (libsource (lib "eagle-import") (part "BJT_NPNMJL4281"))
    )
    (comp (ref "Q78")
      (value "MJL4302A")
      (footprint "eagle-import:TRANSISTOR_TO247_BCE_P")
      (fields (field (name "SPICEPREFIX") "Q"))
      (libsource (lib "eagle-import") (part "BJT_PNPMJL4302"))
    )
    (comp (ref "R51")
      (value "1k")
      (footprint "eagle-import:MINI_MELF-0204W")
      (fields (field (name "SPICEPREFIX") "R"))
      (libsource (lib "eagle-import") (part "R-EU_MELF0204W"))
    )
    (comp (ref "R52")
      (value "20k")
      (footprint "eagle-import:MINI_MELF-0204W")
      (fields (field (name "SPICEPREFIX") "R"))
      (libsource (lib "eagle-import") (part "R-EU_MELF0204W"))
    )
    (comp (ref "R53")
      (value "100k")
      (footprint "eagle-import:MINI_MELF-0204W")
      (fields (field (name "SPICEPREFIX") "R"))
      (libsource (lib "eagle-import") (part "R-EU_MELF0204W"))
    )
    (comp (ref "R54")
      (value "200")
      (footprint "eagle-import:MINI_MELF-0204W")
      (fields (field (name "SPICEPREFIX") "R"))
      (libsource (lib "eagle-import") (part "R-EU_MELF0204W"))
    )
    (comp (ref "R55")
      (value "10")
      (footprint "eagle-import:MINI_MELF-0204W")
      (fields (field (name "SPICEPREFIX") "R"))
      (libsource (lib "eagle-import") (part "R-EU_MELF0204W"))
    )
    (comp (ref "R56")
      (value "10")
      (footprint "eagle-import:MINI_MELF-0204W")
      (fields (field (name "SPICEPREFIX") "R"))
      (libsource (lib "eagle-import") (part "R-EU_MELF0204W"))
    )
    (comp (ref "R57")
      (value "200")
      (footprint "eagle-import:MINI_MELF-0204W")
      (fields (field (name "SPICEPREFIX") "R"))
      (libsource (lib "eagle-import") (part "R-EU_MELF0204W"))
    )
    (comp (ref "R58")
      (value "560")
      (footprint "eagle-import:MINI_MELF-0204W")
      (fields (field (name "SPICEPREFIX") "R"))
      (libsource (lib "eagle-import") (part "R-EU_MELF0204W"))
    )
    (comp (ref "R59")
      (value "10")
      (footprint "eagle-import:MINI_MELF-0204W")
      (fields (field (name "SPICEPREFIX") "R"))
      (libsource (lib "eagle-import") (part "R-EU_MELF0204W"))
    )
    (comp (ref "R60")
      (value "10")
      (footprint "eagle-import:MINI_MELF-0204W")
      (fields (field (name "SPICEPREFIX") "R"))
      (libsource (lib "eagle-import") (part "R-EU_MELF0204W"))
    )
    (comp (ref "R61")
      (value "560")
      (footprint "eagle-import:MINI_MELF-0204W")
      (fields (field (name "SPICEPREFIX") "R"))
      (libsource (lib "eagle-import") (part "R-EU_MELF0204W"))
    )
    (comp (ref "R62")
      (value "100")
      (footprint "eagle-import:MINI_MELF-0204W")
      (fields (field (name "SPICEPREFIX") "R"))
      (libsource (lib "eagle-import") (part "R-EU_MELF0204W"))
    )
    (comp (ref "R63")
      (value "200")
      (footprint "eagle-import:MINI_MELF-0204W")
      (fields (field (name "SPICEPREFIX") "R"))
      (libsource (lib "eagle-import") (part "R-EU_MELF0204W"))
    )
    (comp (ref "R64")
      (value "100")
      (footprint "eagle-import:MINI_MELF-0204W")
      (fields (field (name "SPICEPREFIX") "R"))
      (libsource (lib "eagle-import") (part "R-EU_MELF0204W"))
    )
    (comp (ref "R65")
      (value "68k")
      (footprint "eagle-import:MINI_MELF-0204W")
      (fields (field (name "SPICEPREFIX") "R"))
      (libsource (lib "eagle-import") (part "R-EU_MELF0204W"))
    )
    (comp (ref "R66")
      (value "500")
      (footprint "eagle-import:MINI_MELF-0204W")
      (fields (field (name "SPICEPREFIX") "R"))
      (libsource (lib "eagle-import") (part "R-EU_MELF0204W"))
    )
    (comp (ref "R67")
      (value "100")
      (footprint "eagle-import:MINI_MELF-0204W")
      (fields (field (name "SPICEPREFIX") "R"))
      (libsource (lib "eagle-import") (part "R-EU_MELF0204W"))
    )
    (comp (ref "R68")
      (value "5k")
      (footprint "eagle-import:MINI_MELF-0204W")
      (fields (field (name "SPICEPREFIX") "R"))
      (libsource (lib "eagle-import") (part "R-EU_MELF0204W"))
    )
    (comp (ref "R69")
      (value "5k")
      (footprint "eagle-import:MINI_MELF-0204W")
      (fields (field (name "SPICEPREFIX") "R"))
      (libsource (lib "eagle-import") (part "R-EU_MELF0204W"))
    )
    (comp (ref "R70")
      (value "100")
      (footprint "eagle-import:MINI_MELF-0204W")
      (fields (field (name "SPICEPREFIX") "R"))
      (libsource (lib "eagle-import") (part "R-EU_MELF0204W"))
    )
    (comp (ref "R71")
      (value "100")
      (footprint "eagle-import:MINI_MELF-0204W")
      (fields (field (name "SPICEPREFIX") "R"))
      (libsource (lib "eagle-import") (part "R-EU_MELF0204W"))
    )
    (comp (ref "R72")
      (value "100")
      (footprint "eagle-import:MINI_MELF-0204W")
      (fields (field (name "SPICEPREFIX") "R"))
      (libsource (lib "eagle-import") (part "R-EU_MELF0204W"))
    )
    (comp (ref "R73")
      (value "7k")
      (footprint "eagle-import:MINI_MELF-0204W")
      (fields (field (name "SPICEPREFIX") "R"))
      (libsource (lib "eagle-import") (part "R-EU_MELF0204W"))
    )
    (comp (ref "R74")
      (value "5k")
      (footprint "eagle-import:RTRIM3296W")
      (fields (field (name "SPICEPREFIX") "Z"))
      (libsource (lib "eagle-import") (part "R-TRIMM3296W"))
    )
    (comp (ref "R75")
      (value "1M")
      (footprint "eagle-import:MINI_MELF-0204W")
      (fields (field (name "SPICEPREFIX") "R"))
      (libsource (lib "eagle-import") (part "R-EU_MELF0204W"))
    )
    (comp (ref "R76")
      (value "1M")
      (footprint "eagle-import:MINI_MELF-0204W")
      (fields (field (name "SPICEPREFIX") "R"))
      (libsource (lib "eagle-import") (part "R-EU_MELF0204W"))
    )
    (comp (ref "R77")
      (value "1k")
      (footprint "eagle-import:MINI_MELF-0204W")
      (fields (field (name "SPICEPREFIX") "R"))
      (libsource (lib "eagle-import") (part "R-EU_MELF0204W"))
    )
    (comp (ref "R78")
      (value "220")
      (footprint "eagle-import:MINI_MELF-0204W")
      (fields (field (name "SPICEPREFIX") "R"))
      (libsource (lib "eagle-import") (part "R-EU_MELF0204W"))
    )
    (comp (ref "R79")
      (value "100k")
      (footprint "eagle-import:MINI_MELF-0204W")
      (fields (field (name "SPICEPREFIX") "R"))
      (libsource (lib "eagle-import") (part "R-EU_MELF0204W"))
    )
    (comp (ref "R80")
      (value "0.5")
      (footprint "eagle-import:R2512")
      (fields (field (name "SPICEPREFIX") "R"))
      (libsource (lib "eagle-import") (part "R-EU_R2512"))
    )
    (comp (ref "R81")
      (value "0.5")
      (footprint "eagle-import:R2512")
      (fields (field (name "SPICEPREFIX") "R"))
      (libsource (lib "eagle-import") (part "R-EU_R2512"))
    )
    (comp (ref "R82")
      (value "100k")
      (footprint "eagle-import:MINI_MELF-0204W")
      (fields (field (name "SPICEPREFIX") "R"))
      (libsource (lib "eagle-import") (part "R-EU_MELF0204W"))
    )
    (comp (ref "R83")
      (value "1k")
      (footprint "eagle-import:MINI_MELF-0204W")
      (fields (field (name "SPICEPREFIX") "R"))
      (libsource (lib "eagle-import") (part "R-EU_MELF0204W"))
    )
    (comp (ref "R84")
      (value "20k")
      (footprint "eagle-import:MINI_MELF-0204W")
      (fields (field (name "SPICEPREFIX") "R"))
      (libsource (lib "eagle-import") (part "R-EU_MELF0204W"))
    )
    (comp (ref "R85")
      (value "100k")
      (footprint "eagle-import:MINI_MELF-0204W")
      (fields (field (name "SPICEPREFIX") "R"))
      (libsource (lib "eagle-import") (part "R-EU_MELF0204W"))
    )
    (comp (ref "R86")
      (value "200")
      (footprint "eagle-import:MINI_MELF-0204W")
      (fields (field (name "SPICEPREFIX") "R"))
      (libsource (lib "eagle-import") (part "R-EU_MELF0204W"))
    )
    (comp (ref "R87")
      (value "10")
      (footprint "eagle-import:MINI_MELF-0204W")
      (fields (field (name "SPICEPREFIX") "R"))
      (libsource (lib "eagle-import") (part "R-EU_MELF0204W"))
    )
    (comp (ref "R88")
      (value "10")
      (footprint "eagle-import:MINI_MELF-0204W")
      (fields (field (name "SPICEPREFIX") "R"))
      (libsource (lib "eagle-import") (part "R-EU_MELF0204W"))
    )
    (comp (ref "R89")
      (value "200")
      (footprint "eagle-import:MINI_MELF-0204W")
      (fields (field (name "SPICEPREFIX") "R"))
      (libsource (lib "eagle-import") (part "R-EU_MELF0204W"))
    )
    (comp (ref "R90")
      (value "560")
      (footprint "eagle-import:MINI_MELF-0204W")
      (fields (field (name "SPICEPREFIX") "R"))
      (libsource (lib "eagle-import") (part "R-EU_MELF0204W"))
    )
    (comp (ref "R91")
      (value "10")
      (footprint "eagle-import:MINI_MELF-0204W")
      (fields (field (name "SPICEPREFIX") "R"))
      (libsource (lib "eagle-import") (part "R-EU_MELF0204W"))
    )
    (comp (ref "R92")
      (value "10")
      (footprint "eagle-import:MINI_MELF-0204W")
      (fields (field (name "SPICEPREFIX") "R"))
      (libsource (lib "eagle-import") (part "R-EU_MELF0204W"))
    )
    (comp (ref "R93")
      (value "560")
      (footprint "eagle-import:MINI_MELF-0204W")
      (fields (field (name "SPICEPREFIX") "R"))
      (libsource (lib "eagle-import") (part "R-EU_MELF0204W"))
    )
    (comp (ref "R94")
      (value "100")
      (footprint "eagle-import:MINI_MELF-0204W")
      (fields (field (name "SPICEPREFIX") "R"))
      (libsource (lib "eagle-import") (part "R-EU_MELF0204W"))
    )
    (comp (ref "R95")
      (value "200")
      (footprint "eagle-import:MINI_MELF-0204W")
      (fields (field (name "SPICEPREFIX") "R"))
      (libsource (lib "eagle-import") (part "R-EU_MELF0204W"))
    )
    (comp (ref "R96")
      (value "100")
      (footprint "eagle-import:MINI_MELF-0204W")
      (fields (field (name "SPICEPREFIX") "R"))
      (libsource (lib "eagle-import") (part "R-EU_MELF0204W"))
    )
    (comp (ref "R97")
      (value "68k")
      (footprint "eagle-import:MINI_MELF-0204W")
      (fields (field (name "SPICEPREFIX") "R"))
      (libsource (lib "eagle-import") (part "R-EU_MELF0204W"))
    )
    (comp (ref "R98")
      (value "500")
      (footprint "eagle-import:MINI_MELF-0204W")
      (fields (field (name "SPICEPREFIX") "R"))
      (libsource (lib "eagle-import") (part "R-EU_MELF0204W"))
    )
    (comp (ref "R99")
      (value "100")
      (footprint "eagle-import:MINI_MELF-0204W")
      (fields (field (name "SPICEPREFIX") "R"))
      (libsource (lib "eagle-import") (part "R-EU_MELF0204W"))
    )
    (comp (ref "R100")
      (value "5k")
      (footprint "eagle-import:MINI_MELF-0204W")
      (fields (field (name "SPICEPREFIX") "R"))
      (libsource (lib "eagle-import") (part "R-EU_MELF0204W"))
    )
    (comp (ref "R101")
      (value "5k")
      (footprint "eagle-import:MINI_MELF-0204W")
      (fields (field (name "SPICEPREFIX") "R"))
      (libsource (lib "eagle-import") (part "R-EU_MELF0204W"))
    )
    (comp (ref "R102")
      (value "100")
      (footprint "eagle-import:MINI_MELF-0204W")
      (fields (field (name "SPICEPREFIX") "R"))
      (libsource (lib "eagle-import") (part "R-EU_MELF0204W"))
    )
    (comp (ref "R103")
      (value "100")
      (footprint "eagle-import:MINI_MELF-0204W")
      (fields (field (name "SPICEPREFIX") "R"))
      (libsource (lib "eagle-import") (part "R-EU_MELF0204W"))
    )
    (comp (ref "R104")
      (value "100")
      (footprint "eagle-import:MINI_MELF-0204W")
      (fields (field (name "SPICEPREFIX") "R"))
      (libsource (lib "eagle-import") (part "R-EU_MELF0204W"))
    )
    (comp (ref "R105")
      (value "7k")
      (footprint "eagle-import:MINI_MELF-0204W")
      (fields (field (name "SPICEPREFIX") "R"))
      (libsource (lib "eagle-import") (part "R-EU_MELF0204W"))
    )
    (comp (ref "R106")
      (value "5k")
      (footprint "eagle-import:RTRIM3296W")
      (fields (field (name "SPICEPREFIX") "Z"))
      (libsource (lib "eagle-import") (part "R-TRIMM3296W"))
    )
    (comp (ref "R107")
      (value "1M")
      (footprint "eagle-import:MINI_MELF-0204W")
      (fields (field (name "SPICEPREFIX") "R"))
      (libsource (lib "eagle-import") (part "R-EU_MELF0204W"))
    )
    (comp (ref "R108")
      (value "1M")
      (footprint "eagle-import:MINI_MELF-0204W")
      (fields (field (name "SPICEPREFIX") "R"))
      (libsource (lib "eagle-import") (part "R-EU_MELF0204W"))
    )
    (comp (ref "R109")
      (value "1k")
      (footprint "eagle-import:MINI_MELF-0204W")
      (fields (field (name "SPICEPREFIX") "R"))
      (libsource (lib "eagle-import") (part "R-EU_MELF0204W"))
    )
    (comp (ref "R110")
      (value "220")
      (footprint "eagle-import:MINI_MELF-0204W")
      (fields (field (name "SPICEPREFIX") "R"))
      (libsource (lib "eagle-import") (part "R-EU_MELF0204W"))
    )
    (comp (ref "R111")
      (value "100k")
      (footprint "eagle-import:MINI_MELF-0204W")
      (fields (field (name "SPICEPREFIX") "R"))
      (libsource (lib "eagle-import") (part "R-EU_MELF0204W"))
    )
    (comp (ref "R112")
      (value "0.5")
      (footprint "eagle-import:R2512")
      (fields (field (name "SPICEPREFIX") "R"))
      (libsource (lib "eagle-import") (part "R-EU_R2512"))
    )
    (comp (ref "R113")
      (value "0.5")
      (footprint "eagle-import:R2512")
      (fields (field (name "SPICEPREFIX") "R"))
      (libsource (lib "eagle-import") (part "R-EU_R2512"))
    )
    (comp (ref "R114")
      (value "100k")
      (footprint "eagle-import:MINI_MELF-0204W")
      (fields (field (name "SPICEPREFIX") "R"))
      (libsource (lib "eagle-import") (part "R-EU_MELF0204W"))
    )
    (comp (ref "R133")
      (value "R-EU_R2512")
      (footprint "eagle-import:R2512")
      (libsource (lib "eagle-import") (part "R-EU_R2512"))
    )
  )
  (nets
    (net (code "1") (name "+18V") (class "Default")
      (node (ref "C14") (pin "2") (pinfunction "2_2") (pintype "passive"))
      (node (ref "C23") (pin "1") (pinfunction "1_1") (pintype "passive"))
      (node (ref "C3") (pin "2") (pinfunction "2_2") (pintype "passive"))
      (node (ref "C33") (pin "1") (pinfunction "1_1") (pintype "passive"))
      (node (ref "C69") (pin "1") (pinfunction "1_1") (pintype "passive"))
      (node (ref "C71") (pin "1") (pinfunction "1_1") (pintype "passive"))
      (node (ref "IC1") (pin "7") (pinfunction "V+_7") (pintype "power_in"))
      (node (ref "IC2") (pin "7") (pinfunction "V+_7") (pintype "power_in"))
      (node (ref "IC3") (pin "7") (pinfunction "V+_7") (pintype "power_in"))
      (node (ref "IC4") (pin "7") (pinfunction "V+_7") (pintype "power_in"))
      (node (ref "R136") (pin "2") (pinfunction "2_2") (pintype "passive"))
      (node (ref "R141") (pin "1") (pinfunction "1_1") (pintype "passive"))
      (node (ref "U$5") (pin "10") (pinfunction "O+_10") (pintype "bidirectional"))
    )
    (net (code "2") (name "-18V") (class "Default")
      (node (ref "C15") (pin "1") (pinfunction "1_1") (pintype "passive"))
      (node (ref "C24") (pin "2") (pinfunction "2_2") (pintype "passive"))
      (node (ref "C34") (pin "2") (pinfunction "2_2") (pintype "passive"))
      (node (ref "C4") (pin "1") (pinfunction "1_1") (pintype "passive"))
      (node (ref "C70") (pin "2") (pinfunction "2_2") (pintype "passive"))
      (node (ref "C72") (pin "2") (pinfunction "2_2") (pintype "passive"))
      (node (ref "IC1") (pin "4") (pinfunction "V-_4") (pintype "power_in"))
      (node (ref "IC2") (pin "4") (pinfunction "V-_4") (pintype "power_in"))
      (node (ref "IC3") (pin "4") (pinfunction "V-_4") (pintype "power_in"))
      (node (ref "IC4") (pin "4") (pinfunction "V-_4") (pintype "power_in"))
      (node (ref "R139") (pin "1") (pinfunction "1_1") (pintype "passive"))
      (node (ref "R140") (pin "1") (pinfunction "1_1") (pintype "passive"))
      (node (ref "U$5") (pin "6") (pinfunction "O-_6") (pintype "bidirectional"))
    )
    (net (code "3") (name "AC1") (class "Default")
      (node (ref "Q100") (pin "5") (pinfunction "D_5") (pintype "passive"))
      (node (ref "Q100") (pin "6") (pinfunction "D_6") (pintype "passive"))
      (node (ref "Q100") (pin "7") (pinfunction "D_7") (pintype "passive"))
      (node (ref "Q100") (pin "8") (pinfunction "D_8") (pintype "passive"))
      (node (ref "Q100") (pin "TH") (pinfunction "D_TH") (pintype "passive"))
      (node (ref "Q97") (pin "1") (pinfunction "S_1") (pintype "passive"))
      (node (ref "Q97") (pin "2") (pinfunction "S_2") (pintype "passive"))
      (node (ref "Q97") (pin "3") (pinfunction "S_3") (pintype "passive"))
      (node (ref "U$2") (pin "1") (pinfunction "1_IN2_1") (pintype "bidirectional"))
      (node (ref "X3") (pin "2") (pinfunction "S_2") (pintype "passive"))
    )
    (net (code "4") (name "AC2") (class "Default")
      (node (ref "Q98") (pin "1") (pinfunction "S_1") (pintype "passive"))
      (node (ref "Q98") (pin "2") (pinfunction "S_2") (pintype "passive"))
      (node (ref "Q98") (pin "3") (pinfunction "S_3") (pintype "passive"))
      (node (ref "Q99") (pin "5") (pinfunction "D_5") (pintype "passive"))
      (node (ref "Q99") (pin "6") (pinfunction "D_6") (pintype "passive"))
      (node (ref "Q99") (pin "7") (pinfunction "D_7") (pintype "passive"))
      (node (ref "Q99") (pin "8") (pinfunction "D_8") (pintype "passive"))
      (node (ref "Q99") (pin "TH") (pinfunction "D_TH") (pintype "passive"))
      (node (ref "U$2") (pin "12") (pinfunction "8_IN1_12") (pintype "bidirectional"))
      (node (ref "X3") (pin "1") (pinfunction "S_1") (pintype "passive"))
    )
    (net (code "5") (name "AC3") (class "Default")
      (node (ref "Q105") (pin "1") (pinfunction "S_1") (pintype "passive"))
      (node (ref "Q105") (pin "2") (pinfunction "S_2") (pintype "passive"))
      (node (ref "Q105") (pin "3") (pinfunction "S_3") (pintype "passive"))
      (node (ref "Q108") (pin "5") (pinfunction "D_5") (pintype "passive"))
      (node (ref "Q108") (pin "6") (pinfunction "D_6") (pintype "passive"))
      (node (ref "Q108") (pin "7") (pinfunction "D_7") (pintype "passive"))
      (node (ref "Q108") (pin "8") (pinfunction "D_8") (pintype "passive"))
      (node (ref "Q108") (pin "TH") (pinfunction "D_TH") (pintype "passive"))
      (node (ref "U$4") (pin "1") (pinfunction "1_IN2_1") (pintype "bidirectional"))
      (node (ref "X2") (pin "2") (pinfunction "S_2") (pintype "passive"))
    )
    (net (code "6") (name "AC4") (class "Default")
      (node (ref "Q106") (pin "1") (pinfunction "S_1") (pintype "passive"))
      (node (ref "Q106") (pin "2") (pinfunction "S_2") (pintype "passive"))
      (node (ref "Q106") (pin "3") (pinfunction "S_3") (pintype "passive"))
      (node (ref "Q107") (pin "5") (pinfunction "D_5") (pintype "passive"))
      (node (ref "Q107") (pin "6") (pinfunction "D_6") (pintype "passive"))
      (node (ref "Q107") (pin "7") (pinfunction "D_7") (pintype "passive"))
      (node (ref "Q107") (pin "8") (pinfunction "D_8") (pintype "passive"))
      (node (ref "Q107") (pin "TH") (pinfunction "D_TH") (pintype "passive"))
      (node (ref "U$4") (pin "12") (pinfunction "8_IN1_12") (pintype "bidirectional"))
      (node (ref "X2") (pin "1") (pinfunction "S_1") (pintype "passive"))
    )
    (net (code "7") (name "BOUT+") (class "Default")
      (node (ref "R29") (pin "1") (pinfunction "1_1") (pintype "passive"))
      (node (ref "R30") (pin "1") (pinfunction "1_1") (pintype "passive"))
      (node (ref "R31") (pin "2") (pinfunction "2_2") (pintype "passive"))
      (node (ref "R34") (pin "1") (pinfunction "1_1") (pintype "passive"))
      (node (ref "R35") (pin "2") (pinfunction "2_2") (pintype "passive"))
      (node (ref "R51") (pin "2") (pinfunction "2_2") (pintype "passive"))
    )
    (net (code "8") (name "BOUT-") (class "Default")
      (node (ref "R44") (pin "1") (pinfunction "1_1") (pintype "passive"))
      (node (ref "R45") (pin "1") (pinfunction "1_1") (pintype "passive"))
      (node (ref "R46") (pin "2") (pinfunction "2_2") (pintype "passive"))
      (node (ref "R49") (pin "1") (pinfunction "1_1") (pintype "passive"))
      (node (ref "R50") (pin "2") (pinfunction "2_2") (pintype "passive"))
      (node (ref "R83") (pin "2") (pinfunction "2_2") (pintype "passive"))
    )
    (net (code "9") (name "D5V1") (class "Default")
      (node (ref "C64") (pin "1") (pinfunction "1_1") (pintype "passive"))
      (node (ref "J1") (pin "1") (pinfunction "S_1") (pintype "passive"))
      (node (ref "U$1") (pin "8") (pinfunction "VDD_8") (pintype "bidirectional"))
    )
    (net (code "10") (name "D5V2") (class "Default")
      (node (ref "C61") (pin "1") (pinfunction "1_1") (pintype "passive"))
      (node (ref "J2") (pin "1") (pinfunction "S_1") (pintype "passive"))
      (node (ref "U$3") (pin "8") (pinfunction "VDD_8") (pintype "bidirectional"))
    )
    (net (code "11") (name "DGND1") (class "Default")
      (node (ref "C63") (pin "2") (pinfunction "2_2") (pintype "passive"))
      (node (ref "C64") (pin "2") (pinfunction "2_2") (pintype "passive"))
      (node (ref "J1") (pin "3") (pinfunction "S_3") (pintype "passive"))
      (node (ref "U$1") (pin "5") (pinfunction "GND_5") (pintype "bidirectional"))
    )
    (net (code "12") (name "DGND2") (class "Default")
      (node (ref "C61") (pin "2") (pinfunction "2_2") (pintype "passive"))
      (node (ref "C62") (pin "2") (pinfunction "2_2") (pintype "passive"))
      (node (ref "J2") (pin "3") (pinfunction "S_3") (pintype "passive"))
      (node (ref "U$3") (pin "5") (pinfunction "GND_5") (pintype "bidirectional"))
    )
    (net (code "13") (name "GND") (class "Default")
      (node (ref "C10") (pin "1") (pinfunction "1_1") (pintype "passive"))
      (node (ref "C11") (pin "2") (pinfunction "2_2") (pintype "passive"))
      (node (ref "C12") (pin "1") (pinfunction "1_1") (pintype "passive"))
      (node (ref "C14") (pin "1") (pinfunction "1_1") (pintype "passive"))
      (node (ref "C15") (pin "2") (pinfunction "2_2") (pintype "passive"))
      (node (ref "C17") (pin "2") (pinfunction "2_2") (pintype "passive"))
      (node (ref "C19") (pin "1") (pinfunction "1_1") (pintype "passive"))
      (node (ref "C2") (pin "2") (pinfunction "2_2") (pintype "passive"))
      (node (ref "C20") (pin "2") (pinfunction "2_2") (pintype "passive"))
      (node (ref "C22") (pin "1") (pinfunction "1_1") (pintype "passive"))
      (node (ref "C23") (pin "2") (pinfunction "2_2") (pintype "passive"))
      (node (ref "C24") (pin "1") (pinfunction "1_1") (pintype "passive"))
      (node (ref "C25") (pin "-") (pinfunction "-_-") (pintype "passive"))
      (node (ref "C26") (pin "+") (pinfunction "+_+") (pintype "passive"))
      (node (ref "C27") (pin "2") (pinfunction "2_2") (pintype "passive"))
      (node (ref "C29") (pin "1") (pinfunction "1_1") (pintype "passive"))
      (node (ref "C3") (pin "1") (pinfunction "1_1") (pintype "passive"))
      (node (ref "C30") (pin "2") (pinfunction "2_2") (pintype "passive"))
      (node (ref "C32") (pin "1") (pinfunction "1_1") (pintype "passive"))
      (node (ref "C33") (pin "2") (pinfunction "2_2") (pintype "passive"))
      (node (ref "C34") (pin "1") (pinfunction "1_1") (pintype "passive"))
      (node (ref "C35") (pin "-") (pinfunction "-_-") (pintype "passive"))
      (node (ref "C36") (pin "+") (pinfunction "+_+") (pintype "passive"))
      (node (ref "C37") (pin "-") (pinfunction "-_-") (pintype "passive"))
      (node (ref "C38") (pin "+") (pinfunction "+_+") (pintype "passive"))
      (node (ref "C39") (pin "2") (pinfunction "2_2") (pintype "passive"))
      (node (ref "C4") (pin "2") (pinfunction "2_2") (pintype "passive"))
      (node (ref "C42") (pin "1") (pinfunction "1_1") (pintype "passive"))
      (node (ref "C45") (pin "1") (pinfunction "1_1") (pintype "passive"))
      (node (ref "C46") (pin "2") (pinfunction "2_2") (pintype "passive"))
      (node (ref "C47") (pin "2") (pinfunction "2_2") (pintype "passive"))
      (node (ref "C48") (pin "1") (pinfunction "1_1") (pintype "passive"))
      (node (ref "C49") (pin "2") (pinfunction "2_2") (pintype "passive"))
      (node (ref "C5") (pin "-") (pinfunction "-_-") (pintype "passive"))
      (node (ref "C50") (pin "1") (pinfunction "1_1") (pintype "passive"))
      (node (ref "C55") (pin "1") (pinfunction "1_1") (pintype "passive"))
      (node (ref "C56") (pin "2") (pinfunction "2_2") (pintype "passive"))
      (node (ref "C57") (pin "2") (pinfunction "2_2") (pintype "passive"))
      (node (ref "C58") (pin "1") (pinfunction "1_1") (pintype "passive"))
      (node (ref "C59") (pin "1") (pinfunction "1_1") (pintype "passive"))
      (node (ref "C6") (pin "+") (pinfunction "+_+") (pintype "passive"))
      (node (ref "C60") (pin "2") (pinfunction "2_2") (pintype "passive"))
      (node (ref "C65") (pin "2") (pinfunction "2_2") (pintype "passive"))
      (node (ref "C66") (pin "2") (pinfunction "2_2") (pintype "passive"))
      (node (ref "C67") (pin "2") (pinfunction "2_2") (pintype "passive"))
      (node (ref "C68") (pin "2") (pinfunction "2_2") (pintype "passive"))
      (node (ref "C69") (pin "2") (pinfunction "2_2") (pintype "passive"))
      (node (ref "C7") (pin "-") (pinfunction "-_-") (pintype "passive"))
      (node (ref "C70") (pin "1") (pinfunction "1_1") (pintype "passive"))
      (node (ref "C74") (pin "2") (pinfunction "2_2") (pintype "passive"))
      (node (ref "C75") (pin "1") (pinfunction "1_1") (pintype "passive"))
      (node (ref "C8") (pin "+") (pinfunction "+_+") (pintype "passive"))
      (node (ref "C9") (pin "2") (pinfunction "2_2") (pintype "passive"))
      (node (ref "D17") (pin "4") (pinfunction "GND_4") (pintype "passive"))
      (node (ref "D18") (pin "6") (pinfunction "OUT_6") (pintype "passive"))
      (node (ref "IC1") (pin "3") (pinfunction "+IN_3") (pintype "input"))
      (node (ref "IC2") (pin "3") (pinfunction "+IN_3") (pintype "input"))
      (node (ref "IC5") (pin "7") (pinfunction "V+_7") (pintype "power_in"))
      (node (ref "IC6") (pin "4") (pinfunction "V-_4") (pintype "power_in"))
      (node (ref "LED13") (pin "C") (pinfunction "C_C") (pintype "passive"))
      (node (ref "LED14") (pin "A") (pinfunction "A_A") (pintype "passive"))
      (node (ref "LED17") (pin "C") (pinfunction "C_C") (pintype "passive"))
      (node (ref "LED18") (pin "A") (pinfunction "A_A") (pintype "passive"))
      (node (ref "PAD3") (pin "P$1") (pinfunction "P$1_P$1") (pintype "bidirectional"))
      (node (ref "PAD4") (pin "P$1") (pinfunction "P$1_P$1") (pintype "bidirectional"))
      (node (ref "Q100") (pin "1") (pinfunction "S_1") (pintype "passive"))
      (node (ref "Q100") (pin "2") (pinfunction "S_2") (pintype "passive"))
      (node (ref "Q100") (pin "3") (pinfunction "S_3") (pintype "passive"))
      (node (ref "Q105") (pin "5") (pinfunction "D_5") (pintype "passive"))
      (node (ref "Q105") (pin "6") (pinfunction "D_6") (pintype "passive"))
      (node (ref "Q105") (pin "7") (pinfunction "D_7") (pintype "passive"))
      (node (ref "Q105") (pin "8") (pinfunction "D_8") (pintype "passive"))
      (node (ref "Q105") (pin "TH") (pinfunction "D_TH") (pintype "passive"))
      (node (ref "Q106") (pin "5") (pinfunction "D_5") (pintype "passive"))
      (node (ref "Q106") (pin "6") (pinfunction "D_6") (pintype "passive"))
      (node (ref "Q106") (pin "7") (pinfunction "D_7") (pintype "passive"))
      (node (ref "Q106") (pin "8") (pinfunction "D_8") (pintype "passive"))
      (node (ref "Q106") (pin "TH") (pinfunction "D_TH") (pintype "passive"))
      (node (ref "Q85") (pin "C") (pinfunction "C_C") (pintype "passive"))
      (node (ref "Q86") (pin "C") (pinfunction "C_C") (pintype "passive"))
      (node (ref "Q99") (pin "1") (pinfunction "S_1") (pintype "passive"))
      (node (ref "Q99") (pin "2") (pinfunction "S_2") (pintype "passive"))
      (node (ref "Q99") (pin "3") (pinfunction "S_3") (pintype "passive"))
      (node (ref "R107") (pin "2") (pinfunction "2_2") (pintype "passive"))
      (node (ref "R108") (pin "1") (pinfunction "1_1") (pintype "passive"))
      (node (ref "R11") (pin "1") (pinfunction "1_1") (pintype "passive"))
      (node (ref "R111") (pin "1") (pinfunction "1_1") (pintype "passive"))
      (node (ref "R117") (pin "2") (pinfunction "2_2") (pintype "passive"))
      (node (ref "R118") (pin "1") (pinfunction "1_1") (pintype "passive"))
      (node (ref "R128") (pin "1") (pinfunction "1_1") (pintype "passive"))
      (node (ref "R129") (pin "2") (pinfunction "2_2") (pintype "passive"))
      (node (ref "R134") (pin "1") (pinfunction "1_1") (pintype "passive"))
      (node (ref "R135") (pin "1") (pinfunction "1_1") (pintype "passive"))
      (node (ref "R137") (pin "1") (pinfunction "1_1") (pintype "passive"))
      (node (ref "R15") (pin "1") (pinfunction "1_1") (pintype "passive"))
      (node (ref "R16") (pin "2") (pinfunction "2_2") (pintype "passive"))
      (node (ref "R20") (pin "1") (pinfunction "1_1") (pintype "passive"))
      (node (ref "R3") (pin "1") (pinfunction "1_1") (pintype "passive"))
      (node (ref "R4") (pin "2") (pinfunction "2_2") (pintype "passive"))
      (node (ref "R52") (pin "1") (pinfunction "1_1") (pintype "passive"))
      (node (ref "R63") (pin "1") (pinfunction "1_1") (pintype "passive"))
      (node (ref "R75") (pin "2") (pinfunction "2_2") (pintype "passive"))
      (node (ref "R76") (pin "1") (pinfunction "1_1") (pintype "passive"))
      (node (ref "R79") (pin "1") (pinfunction "1_1") (pintype "passive"))
      (node (ref "R84") (pin "1") (pinfunction "1_1") (pintype "passive"))
      (node (ref "R95") (pin "1") (pinfunction "1_1") (pintype "passive"))
      (node (ref "U$2") (pin "7") (pinfunction "5_OUTN_7") (pintype "bidirectional"))
      (node (ref "U$2") (pin "EXP") (pinfunction "5_OUTN_EXP") (pintype "bidirectional"))
      (node (ref "U$4") (pin "9") (pinfunction "6_OUTP_9") (pintype "bidirectional"))
      (node (ref "U$5") (pin "11") (pinfunction "GND_11") (pintype "bidirectional"))
      (node (ref "U$5") (pin "12") (pinfunction "GND_12") (pintype "bidirectional"))
      (node (ref "U$5") (pin "13") (pinfunction "GND_13") (pintype "bidirectional"))
      (node (ref "U$5") (pin "14") (pinfunction "GND_14") (pintype "bidirectional"))
      (node (ref "U$5") (pin "15") (pinfunction "GND_15") (pintype "bidirectional"))
      (node (ref "U$5") (pin "4") (pinfunction "GND_4") (pintype "bidirectional"))
      (node (ref "X1") (pin "2") (pinfunction "S_2") (pintype "passive"))
    )
    (net (code "14") (name "IN+") (class "Default")
      (node (ref "Q1") (pin "4") (pinfunction "G_4") (pintype "passive"))
      (node (ref "Q4") (pin "4") (pinfunction "G_4") (pintype "passive"))
      (node (ref "R134") (pin "2") (pinfunction "2_2") (pintype "passive"))
      (node (ref "X1") (pin "3") (pinfunction "S_3") (pintype "passive"))
    )
    (net (code "15") (name "IN-") (class "Default")
      (node (ref "Q1") (pin "1") (pinfunction "G_1") (pintype "passive"))
      (node (ref "Q4") (pin "1") (pinfunction "G_1") (pintype "passive"))
      (node (ref "R135") (pin "2") (pinfunction "2_2") (pintype "passive"))
      (node (ref "X1") (pin "1") (pinfunction "S_1") (pintype "passive"))
    )
    (net (code "16") (name "Net-(C1-Pad2)") (class "Default")
      (node (ref "C1") (pin "2") (pinfunction "2_2") (pintype "passive"))
      (node (ref "R133") (pin "1") (pinfunction "1_1") (pintype "passive"))
    )
    (net (code "17") (name "Net-(C17-Pad1)") (class "Default")
      (node (ref "C17") (pin "1") (pinfunction "1_1") (pintype "passive"))
      (node (ref "Q26") (pin "B") (pinfunction "B_B") (pintype "passive"))
      (node (ref "Q27") (pin "B") (pinfunction "B_B") (pintype "passive"))
      (node (ref "R51") (pin "1") (pinfunction "1_1") (pintype "passive"))
      (node (ref "R52") (pin "2") (pinfunction "2_2") (pintype "passive"))
    )
    (net (code "18") (name "Net-(C18-Pad1)") (class "Default")
      (node (ref "C18") (pin "1") (pinfunction "1_1") (pintype "passive"))
      (node (ref "C19") (pin "2") (pinfunction "2_2") (pintype "passive"))
      (node (ref "Q39") (pin "C") (pinfunction "C_C") (pintype "passive"))
      (node (ref "Q43") (pin "C") (pinfunction "C_C") (pintype "passive"))
      (node (ref "Q45") (pin "C") (pinfunction "C_C") (pintype "passive"))
      (node (ref "Q46") (pin "B") (pinfunction "B_B") (pintype "passive"))
      (node (ref "R73") (pin "2") (pinfunction "2_2") (pintype "passive"))
      (node (ref "R75") (pin "1") (pinfunction "1_1") (pintype "passive"))
    )
    (net (code "19") (name "Net-(C27-Pad1)") (class "Default")
      (node (ref "C27") (pin "1") (pinfunction "1_1") (pintype "passive"))
      (node (ref "Q53") (pin "B") (pinfunction "B_B") (pintype "passive"))
      (node (ref "Q54") (pin "B") (pinfunction "B_B") (pintype "passive"))
      (node (ref "R83") (pin "1") (pinfunction "1_1") (pintype "passive"))
      (node (ref "R84") (pin "2") (pinfunction "2_2") (pintype "passive"))
    )
    (net (code "20") (name "Net-(C28-Pad1)") (class "Default")
      (node (ref "C28") (pin "1") (pinfunction "1_1") (pintype "passive"))
      (node (ref "C29") (pin "2") (pinfunction "2_2") (pintype "passive"))
      (node (ref "Q66") (pin "C") (pinfunction "C_C") (pintype "passive"))
      (node (ref "Q70") (pin "C") (pinfunction "C_C") (pintype "passive"))
      (node (ref "Q72") (pin "C") (pinfunction "C_C") (pintype "passive"))
      (node (ref "Q73") (pin "B") (pinfunction "B_B") (pintype "passive"))
      (node (ref "R105") (pin "2") (pinfunction "2_2") (pintype "passive"))
      (node (ref "R107") (pin "1") (pinfunction "1_1") (pintype "passive"))
    )
    (net (code "21") (name "Net-(C40-Pad1)") (class "Default")
      (node (ref "C40") (pin "1") (pinfunction "1_1") (pintype "passive"))
      (node (ref "C43") (pin "1") (pinfunction "1_1") (pintype "passive"))
      (node (ref "D13") (pin "C") (pinfunction "C_C") (pintype "passive"))
      (node (ref "Q83") (pin "C") (pinfunction "C_C") (pintype "passive"))
      (node (ref "Q87") (pin "B") (pinfunction "B_B") (pintype "passive"))
    )
    (net (code "22") (name "Net-(C40-Pad2)") (class "Default")
      (node (ref "C40") (pin "2") (pinfunction "2_2") (pintype "passive"))
      (node (ref "C43") (pin "2") (pinfunction "2_2") (pintype "passive"))
      (node (ref "D13") (pin "A") (pinfunction "A_A") (pintype "passive"))
      (node (ref "R120") (pin "1") (pinfunction "1_1") (pintype "passive"))
    )
    (net (code "23") (name "Net-(C41-Pad1)") (class "Default")
      (node (ref "C41") (pin "1") (pinfunction "1_1") (pintype "passive"))
      (node (ref "C44") (pin "1") (pinfunction "1_1") (pintype "passive"))
      (node (ref "D14") (pin "C") (pinfunction "C_C") (pintype "passive"))
      (node (ref "R121") (pin "2") (pinfunction "2_2") (pintype "passive"))
    )
    (net (code "24") (name "Net-(C41-Pad2)") (class "Default")
      (node (ref "C41") (pin "2") (pinfunction "2_2") (pintype "passive"))
      (node (ref "C44") (pin "2") (pinfunction "2_2") (pintype "passive"))
      (node (ref "D14") (pin "A") (pinfunction "A_A") (pintype "passive"))
      (node (ref "Q84") (pin "C") (pinfunction "C_C") (pintype "passive"))
      (node (ref "Q88") (pin "B") (pinfunction "B_B") (pintype "passive"))
    )
    (net (code "25") (name "Net-(D1-PadC)") (class "Default")
      (node (ref "D1") (pin "C") (pinfunction "C_C") (pintype "passive"))
      (node (ref "D2") (pin "A") (pinfunction "A_A") (pintype "passive"))
    )
    (net (code "26") (name "Net-(D2-PadC)") (class "Default")
      (node (ref "D2") (pin "C") (pinfunction "C_C") (pintype "passive"))
      (node (ref "Q25") (pin "B") (pinfunction "B_B") (pintype "passive"))
      (node (ref "R53") (pin "2") (pinfunction "2_2") (pintype "passive"))
    )
    (net (code "27") (name "Net-(D3-PadA)") (class "Default")
      (node (ref "D3") (pin "A") (pinfunction "A_A") (pintype "passive"))
      (node (ref "Q28") (pin "B") (pinfunction "B_B") (pintype "passive"))
      (node (ref "R53") (pin "1") (pinfunction "1_1") (pintype "passive"))
    )
    (net (code "28") (name "Net-(D3-PadC)") (class "Default")
      (node (ref "D3") (pin "C") (pinfunction "C_C") (pintype "passive"))
      (node (ref "D4") (pin "A") (pinfunction "A_A") (pintype "passive"))
    )
    (net (code "29") (name "Net-(D5-PadA)") (class "Default")
      (node (ref "D5") (pin "A") (pinfunction "A_A") (pintype "passive"))
      (node (ref "Q25") (pin "C") (pinfunction "C_C") (pintype "passive"))
      (node (ref "Q29") (pin "B") (pinfunction "B_B") (pintype "passive"))
    )
    (net (code "30") (name "Net-(D5-PadC)") (class "Default")
      (node (ref "D5") (pin "C") (pinfunction "C_C") (pintype "passive"))
      (node (ref "Q30") (pin "B") (pinfunction "B_B") (pintype "passive"))
      (node (ref "R55") (pin "2") (pinfunction "2_2") (pintype "passive"))
    )
    (net (code "31") (name "Net-(D6-PadA)") (class "Default")
      (node (ref "D6") (pin "A") (pinfunction "A_A") (pintype "passive"))
      (node (ref "Q31") (pin "B") (pinfunction "B_B") (pintype "passive"))
      (node (ref "R56") (pin "1") (pinfunction "1_1") (pintype "passive"))
    )
    (net (code "32") (name "Net-(D6-PadC)") (class "Default")
      (node (ref "D6") (pin "C") (pinfunction "C_C") (pintype "passive"))
      (node (ref "Q28") (pin "C") (pinfunction "C_C") (pintype "passive"))
      (node (ref "Q32") (pin "B") (pinfunction "B_B") (pintype "passive"))
    )
    (net (code "33") (name "Net-(D7-PadC)") (class "Default")
      (node (ref "D7") (pin "C") (pinfunction "C_C") (pintype "passive"))
      (node (ref "D8") (pin "A") (pinfunction "A_A") (pintype "passive"))
    )
    (net (code "34") (name "Net-(D8-PadC)") (class "Default")
      (node (ref "D8") (pin "C") (pinfunction "C_C") (pintype "passive"))
      (node (ref "Q52") (pin "B") (pinfunction "B_B") (pintype "passive"))
      (node (ref "R85") (pin "2") (pinfunction "2_2") (pintype "passive"))
    )
    (net (code "35") (name "Net-(D9-PadA)") (class "Default")
      (node (ref "D9") (pin "A") (pinfunction "A_A") (pintype "passive"))
      (node (ref "Q55") (pin "B") (pinfunction "B_B") (pintype "passive"))
      (node (ref "R85") (pin "1") (pinfunction "1_1") (pintype "passive"))
    )
    (net (code "36") (name "Net-(D10-PadA)") (class "Default")
      (node (ref "D10") (pin "A") (pinfunction "A_A") (pintype "passive"))
      (node (ref "D9") (pin "C") (pinfunction "C_C") (pintype "passive"))
    )
    (net (code "37") (name "Net-(D11-PadA)") (class "Default")
      (node (ref "D11") (pin "A") (pinfunction "A_A") (pintype "passive"))
      (node (ref "Q52") (pin "C") (pinfunction "C_C") (pintype "passive"))
      (node (ref "Q56") (pin "B") (pinfunction "B_B") (pintype "passive"))
    )
    (net (code "38") (name "Net-(D11-PadC)") (class "Default")
      (node (ref "D11") (pin "C") (pinfunction "C_C") (pintype "passive"))
      (node (ref "Q57") (pin "B") (pinfunction "B_B") (pintype "passive"))
      (node (ref "R87") (pin "2") (pinfunction "2_2") (pintype "passive"))
    )
    (net (code "39") (name "Net-(D12-PadA)") (class "Default")
      (node (ref "D12") (pin "A") (pinfunction "A_A") (pintype "passive"))
      (node (ref "Q58") (pin "B") (pinfunction "B_B") (pintype "passive"))
      (node (ref "R88") (pin "1") (pinfunction "1_1") (pintype "passive"))
    )
    (net (code "40") (name "Net-(D12-PadC)") (class "Default")
      (node (ref "D12") (pin "C") (pinfunction "C_C") (pintype "passive"))
      (node (ref "Q55") (pin "C") (pinfunction "C_C") (pintype "passive"))
      (node (ref "Q59") (pin "B") (pinfunction "B_B") (pintype "passive"))
    )
    (net (code "41") (name "Net-(D17-OUT)") (class "Default")
      (node (ref "C47") (pin "1") (pinfunction "1_1") (pintype "passive"))
      (node (ref "C49") (pin "1") (pinfunction "1_1") (pintype "passive"))
      (node (ref "D17") (pin "6") (pinfunction "OUT_6") (pintype "passive"))
      (node (ref "D19") (pin "C") (pinfunction "C_C") (pintype "passive"))
      (node (ref "D20") (pin "A") (pinfunction "A_A") (pintype "passive"))
      (node (ref "IC6") (pin "3") (pinfunction "+IN_3") (pintype "input"))
      (node (ref "Q91") (pin "G") (pinfunction "G_G") (pintype "passive"))
      (node (ref "R125") (pin "1") (pinfunction "1_1") (pintype "passive"))
    )
    (net (code "42") (name "Net-(D18-GND)") (class "Default")
      (node (ref "C48") (pin "2") (pinfunction "2_2") (pintype "passive"))
      (node (ref "C50") (pin "2") (pinfunction "2_2") (pintype "passive"))
      (node (ref "D18") (pin "4") (pinfunction "GND_4") (pintype "passive"))
      (node (ref "D21") (pin "A") (pinfunction "A_A") (pintype "passive"))
      (node (ref "D22") (pin "C") (pinfunction "C_C") (pintype "passive"))
      (node (ref "IC5") (pin "3") (pinfunction "+IN_3") (pintype "input"))
      (node (ref "Q92") (pin "D") (pinfunction "D_D") (pintype "passive"))
    )
    (net (code "43") (name "Net-(IC1--IN)") (class "Default")
      (node (ref "C13") (pin "2") (pinfunction "2_2") (pintype "passive"))
      (node (ref "IC1") (pin "2") (pinfunction "-IN_2") (pintype "input"))
      (node (ref "R29") (pin "2") (pinfunction "2_2") (pintype "passive"))
    )
    (net (code "44") (name "Net-(IC1-CMP2)") (class "Default")
      (node (ref "C13") (pin "1") (pinfunction "1_1") (pintype "passive"))
      (node (ref "IC1") (pin "6") (pinfunction "OUT_6") (pintype "output"))
      (node (ref "IC1") (pin "8") (pinfunction "CMP2_8") (pintype "passive"))
      (node (ref "R21") (pin "1") (pinfunction "1_1") (pintype "passive"))
    )
    (net (code "45") (name "Net-(IC2--IN)") (class "Default")
      (node (ref "C16") (pin "2") (pinfunction "2_2") (pintype "passive"))
      (node (ref "IC2") (pin "2") (pinfunction "-IN_2") (pintype "input"))
      (node (ref "R44") (pin "2") (pinfunction "2_2") (pintype "passive"))
    )
    (net (code "46") (name "Net-(IC2-CMP2)") (class "Default")
      (node (ref "C16") (pin "1") (pinfunction "1_1") (pintype "passive"))
      (node (ref "IC2") (pin "6") (pinfunction "OUT_6") (pintype "output"))
      (node (ref "IC2") (pin "8") (pinfunction "CMP2_8") (pintype "passive"))
      (node (ref "R36") (pin "1") (pinfunction "1_1") (pintype "passive"))
    )
    (net (code "47") (name "Net-(IC3-+IN)") (class "Default")
      (node (ref "C22") (pin "2") (pinfunction "2_2") (pintype "passive"))
      (node (ref "IC3") (pin "3") (pinfunction "+IN_3") (pintype "input"))
      (node (ref "R82") (pin "2") (pinfunction "2_2") (pintype "passive"))
    )
    (net (code "48") (name "Net-(IC3--IN)") (class "Default")
      (node (ref "C21") (pin "2") (pinfunction "2_2") (pintype "passive"))
      (node (ref "IC3") (pin "2") (pinfunction "-IN_2") (pintype "input"))
      (node (ref "R79") (pin "2") (pinfunction "2_2") (pintype "passive"))
    )
    (net (code "49") (name "Net-(IC3-OUT)") (class "Default")
      (node (ref "C21") (pin "1") (pinfunction "1_1") (pintype "passive"))
      (node (ref "IC3") (pin "6") (pinfunction "OUT_6") (pintype "output"))
      (node (ref "R68") (pin "1") (pinfunction "1_1") (pintype "passive"))
      (node (ref "R69") (pin "2") (pinfunction "2_2") (pintype "passive"))
    )
    (net (code "50") (name "Net-(IC4-+IN)") (class "Default")
      (node (ref "C32") (pin "2") (pinfunction "2_2") (pintype "passive"))
      (node (ref "IC4") (pin "3") (pinfunction "+IN_3") (pintype "input"))
      (node (ref "R114") (pin "2") (pinfunction "2_2") (pintype "passive"))
    )
    (net (code "51") (name "Net-(IC4--IN)") (class "Default")
      (node (ref "C31") (pin "2") (pinfunction "2_2") (pintype "passive"))
      (node (ref "IC4") (pin "2") (pinfunction "-IN_2") (pintype "input"))
      (node (ref "R111") (pin "2") (pinfunction "2_2") (pintype "passive"))
    )
    (net (code "52") (name "Net-(IC4-OUT)") (class "Default")
      (node (ref "C31") (pin "1") (pinfunction "1_1") (pintype "passive"))
      (node (ref "IC4") (pin "6") (pinfunction "OUT_6") (pintype "output"))
      (node (ref "R100") (pin "1") (pinfunction "1_1") (pintype "passive"))
      (node (ref "R101") (pin "2") (pinfunction "2_2") (pintype "passive"))
    )
    (net (code "53") (name "Net-(IC5--IN)") (class "Default")
      (node (ref "C52") (pin "2") (pinfunction "2_2") (pintype "passive"))
      (node (ref "C54") (pin "1") (pinfunction "1_1") (pintype "passive"))
      (node (ref "D21") (pin "C") (pinfunction "C_C") (pintype "passive"))
      (node (ref "D22") (pin "A") (pinfunction "A_A") (pintype "passive"))
      (node (ref "IC5") (pin "2") (pinfunction "-IN_2") (pintype "input"))
      (node (ref "R129") (pin "1") (pinfunction "1_1") (pintype "passive"))
      (node (ref "R130") (pin "2") (pinfunction "2_2") (pintype "passive"))
    )
    (net (code "54") (name "Net-(IC5-OUT)") (class "Default")
      (node (ref "C52") (pin "1") (pinfunction "1_1") (pintype "passive"))
      (node (ref "IC5") (pin "6") (pinfunction "OUT_6") (pintype "output"))
      (node (ref "R124") (pin "1") (pinfunction "1_1") (pintype "passive"))
    )
    (net (code "55") (name "Net-(IC6--IN)") (class "Default")
      (node (ref "C51") (pin "2") (pinfunction "2_2") (pintype "passive"))
      (node (ref "C53") (pin "2") (pinfunction "2_2") (pintype "passive"))
      (node (ref "D19") (pin "A") (pinfunction "A_A") (pintype "passive"))
      (node (ref "D20") (pin "C") (pinfunction "C_C") (pintype "passive"))
      (node (ref "IC6") (pin "2") (pinfunction "-IN_2") (pintype "input"))
      (node (ref "R127") (pin "1") (pinfunction "1_1") (pintype "passive"))
      (node (ref "R128") (pin "2") (pinfunction "2_2") (pintype "passive"))
    )
    (net (code "56") (name "Net-(IC6-OUT)") (class "Default")
      (node (ref "C51") (pin "1") (pinfunction "1_1") (pintype "passive"))
      (node (ref "IC6") (pin "6") (pinfunction "OUT_6") (pintype "output"))
      (node (ref "R123") (pin "1") (pinfunction "1_1") (pintype "passive"))
    )
    (net (code "57") (name "Net-(LED1-PadC)") (class "Default")
      (node (ref "LED1") (pin "C") (pinfunction "C_C") (pintype "passive"))
      (node (ref "Q2") (pin "B") (pinfunction "B_B") (pintype "passive"))
      (node (ref "R3") (pin "2") (pinfunction "2_2") (pintype "passive"))
    )
    (net (code "58") (name "Net-(LED2-PadA)") (class "Default")
      (node (ref "LED2") (pin "A") (pinfunction "A_A") (pintype "passive"))
      (node (ref "Q3") (pin "B") (pinfunction "B_B") (pintype "passive"))
      (node (ref "R4") (pin "1") (pinfunction "1_1") (pintype "passive"))
    )
    (net (code "59") (name "Net-(LED5-PadC)") (class "Default")
      (node (ref "LED5") (pin "C") (pinfunction "C_C") (pintype "passive"))
      (node (ref "Q11") (pin "B") (pinfunction "B_B") (pintype "passive"))
      (node (ref "R22") (pin "2") (pinfunction "2_2") (pintype "passive"))
    )
    (net (code "60") (name "Net-(LED6-PadA)") (class "Default")
      (node (ref "LED6") (pin "A") (pinfunction "A_A") (pintype "passive"))
      (node (ref "Q12") (pin "B") (pinfunction "B_B") (pintype "passive"))
      (node (ref "R22") (pin "1") (pinfunction "1_1") (pintype "passive"))
    )
    (net (code "61") (name "Net-(LED7-PadC)") (class "Default")
      (node (ref "LED7") (pin "C") (pinfunction "C_C") (pintype "passive"))
      (node (ref "Q19") (pin "B") (pinfunction "B_B") (pintype "passive"))
      (node (ref "R37") (pin "2") (pinfunction "2_2") (pintype "passive"))
    )
    (net (code "62") (name "Net-(LED8-PadA)") (class "Default")
      (node (ref "LED8") (pin "A") (pinfunction "A_A") (pintype "passive"))
      (node (ref "Q20") (pin "B") (pinfunction "B_B") (pintype "passive"))
      (node (ref "R37") (pin "1") (pinfunction "1_1") (pintype "passive"))
    )
    (net (code "63") (name "Net-(LED9-PadA)") (class "Default")
      (node (ref "LED9") (pin "A") (pinfunction "A_A") (pintype "passive"))
      (node (ref "Q35") (pin "E") (pinfunction "E_E") (pintype "passive"))
      (node (ref "R62") (pin "1") (pinfunction "1_1") (pintype "passive"))
    )
    (net (code "64") (name "Net-(LED9-PadC)") (class "Default")
      (node (ref "LED9") (pin "C") (pinfunction "C_C") (pintype "passive"))
      (node (ref "Q39") (pin "B") (pinfunction "B_B") (pintype "passive"))
      (node (ref "R65") (pin "2") (pinfunction "2_2") (pintype "passive"))
    )
    (net (code "65") (name "Net-(LED10-PadA)") (class "Default")
      (node (ref "LED10") (pin "A") (pinfunction "A_A") (pintype "passive"))
      (node (ref "Q40") (pin "B") (pinfunction "B_B") (pintype "passive"))
      (node (ref "R65") (pin "1") (pinfunction "1_1") (pintype "passive"))
    )
    (net (code "66") (name "Net-(LED10-PadC)") (class "Default")
      (node (ref "LED10") (pin "C") (pinfunction "C_C") (pintype "passive"))
      (node (ref "Q38") (pin "E") (pinfunction "E_E") (pintype "passive"))
      (node (ref "R64") (pin "2") (pinfunction "2_2") (pintype "passive"))
    )
    (net (code "67") (name "Net-(LED11-PadA)") (class "Default")
      (node (ref "LED11") (pin "A") (pinfunction "A_A") (pintype "passive"))
      (node (ref "Q62") (pin "E") (pinfunction "E_E") (pintype "passive"))
      (node (ref "R94") (pin "1") (pinfunction "1_1") (pintype "passive"))
    )
    (net (code "68") (name "Net-(LED11-PadC)") (class "Default")
      (node (ref "LED11") (pin "C") (pinfunction "C_C") (pintype "passive"))
      (node (ref "Q66") (pin "B") (pinfunction "B_B") (pintype "passive"))
      (node (ref "R97") (pin "2") (pinfunction "2_2") (pintype "passive"))
    )
    (net (code "69") (name "Net-(LED12-PadA)") (class "Default")
      (node (ref "LED12") (pin "A") (pinfunction "A_A") (pintype "passive"))
      (node (ref "Q67") (pin "B") (pinfunction "B_B") (pintype "passive"))
      (node (ref "R97") (pin "1") (pinfunction "1_1") (pintype "passive"))
    )
    (net (code "70") (name "Net-(LED12-PadC)") (class "Default")
      (node (ref "LED12") (pin "C") (pinfunction "C_C") (pintype "passive"))
      (node (ref "Q65") (pin "E") (pinfunction "E_E") (pintype "passive"))
      (node (ref "R96") (pin "2") (pinfunction "2_2") (pintype "passive"))
    )
    (net (code "71") (name "Net-(LED13-PadA)") (class "Default")
      (node (ref "LED13") (pin "A") (pinfunction "A_A") (pintype "passive"))
      (node (ref "Q79") (pin "B") (pinfunction "B_B") (pintype "passive"))
      (node (ref "R115") (pin "2") (pinfunction "2_2") (pintype "passive"))
    )
    (net (code "72") (name "Net-(LED14-PadC)") (class "Default")
      (node (ref "LED14") (pin "C") (pinfunction "C_C") (pintype "passive"))
      (node (ref "Q80") (pin "B") (pinfunction "B_B") (pintype "passive"))
      (node (ref "R116") (pin "1") (pinfunction "1_1") (pintype "passive"))
    )
    (net (code "73") (name "Net-(LED15-PadC)") (class "Default")
      (node (ref "LED15") (pin "C") (pinfunction "C_C") (pintype "passive"))
      (node (ref "Q81") (pin "E") (pinfunction "E_E") (pintype "passive"))
    )
    (net (code "74") (name "Net-(LED16-PadA)") (class "Default")
      (node (ref "LED16") (pin "A") (pinfunction "A_A") (pintype "passive"))
      (node (ref "Q82") (pin "E") (pinfunction "E_E") (pintype "passive"))
    )
    (net (code "75") (name "Net-(LED17-PadA)") (class "Default")
      (node (ref "LED17") (pin "A") (pinfunction "A_A") (pintype "passive"))
      (node (ref "R131") (pin "1") (pinfunction "1_1") (pintype "passive"))
    )
    (net (code "76") (name "Net-(LED18-PadC)") (class "Default")
      (node (ref "LED18") (pin "C") (pinfunction "C_C") (pintype "passive"))
      (node (ref "R132") (pin "2") (pinfunction "2_2") (pintype "passive"))
    )
    (net (code "77") (name "Net-(Q1A-D)") (class "Default")
      (node (ref "Q1") (pin "2") (pinfunction "D_2") (pintype "passive"))
      (node (ref "Q6") (pin "5") (pinfunction "E_5") (pintype "passive"))
      (node (ref "Q7") (pin "6") (pinfunction "C_6") (pintype "passive"))
    )
    (net (code "78") (name "Net-(Q1A-S)") (class "Default")
      (node (ref "Q1") (pin "3") (pinfunction "S_3") (pintype "passive"))
      (node (ref "R6") (pin "1") (pinfunction "1_1") (pintype "passive"))
    )
    (net (code "79") (name "Net-(Q1B-D)") (class "Default")
      (node (ref "Q1") (pin "5") (pinfunction "D_5") (pintype "passive"))
      (node (ref "Q6") (pin "2") (pinfunction "E_2") (pintype "passive"))
      (node (ref "Q7") (pin "4") (pinfunction "C_4") (pintype "passive"))
    )
    (net (code "80") (name "Net-(Q1B-S)") (class "Default")
      (node (ref "Q1") (pin "6") (pinfunction "S_6") (pintype "passive"))
      (node (ref "R8") (pin "1") (pinfunction "1_1") (pintype "passive"))
    )
    (net (code "81") (name "Net-(Q2-PadC)") (class "Default")
      (node (ref "Q2") (pin "C") (pinfunction "C_C") (pintype "passive"))
      (node (ref "R6") (pin "2") (pinfunction "2_2") (pintype "passive"))
      (node (ref "R8") (pin "2") (pinfunction "2_2") (pintype "passive"))
    )
    (net (code "82") (name "Net-(Q2-PadE)") (class "Default")
      (node (ref "Q2") (pin "E") (pinfunction "E_E") (pintype "passive"))
      (node (ref "R5") (pin "1") (pinfunction "1_1") (pintype "passive"))
    )
    (net (code "83") (name "Net-(Q3-PadC)") (class "Default")
      (node (ref "Q3") (pin "C") (pinfunction "C_C") (pintype "passive"))
      (node (ref "R10") (pin "1") (pinfunction "1_1") (pintype "passive"))
      (node (ref "R9") (pin "1") (pinfunction "1_1") (pintype "passive"))
    )
    (net (code "84") (name "Net-(Q3-PadE)") (class "Default")
      (node (ref "Q3") (pin "E") (pinfunction "E_E") (pintype "passive"))
      (node (ref "R7") (pin "2") (pinfunction "2_2") (pintype "passive"))
    )
    (net (code "85") (name "Net-(Q4A-D)") (class "Default")
      (node (ref "Q4") (pin "2") (pinfunction "D_2") (pintype "passive"))
      (node (ref "Q5") (pin "5") (pinfunction "E_5") (pintype "passive"))
      (node (ref "Q8") (pin "4") (pinfunction "C_4") (pintype "passive"))
    )
    (net (code "86") (name "Net-(Q4A-S)") (class "Default")
      (node (ref "Q4") (pin "3") (pinfunction "S_3") (pintype "passive"))
      (node (ref "R9") (pin "2") (pinfunction "2_2") (pintype "passive"))
    )
    (net (code "87") (name "Net-(Q4B-D)") (class "Default")
      (node (ref "Q4") (pin "5") (pinfunction "D_5") (pintype "passive"))
      (node (ref "Q5") (pin "2") (pinfunction "E_2") (pintype "passive"))
      (node (ref "Q8") (pin "6") (pinfunction "C_6") (pintype "passive"))
    )
    (net (code "88") (name "Net-(Q4B-S)") (class "Default")
      (node (ref "Q4") (pin "6") (pinfunction "S_6") (pintype "passive"))
      (node (ref "R10") (pin "2") (pinfunction "2_2") (pintype "passive"))
    )
    (net (code "89") (name "Net-(Q5A-B)") (class "Default")
      (node (ref "Q5") (pin "1") (pinfunction "B_1") (pintype "passive"))
      (node (ref "Q5") (pin "3") (pinfunction "B_3") (pintype "passive"))
      (node (ref "R14") (pin "1") (pinfunction "1_1") (pintype "passive"))
      (node (ref "R15") (pin "2") (pinfunction "2_2") (pintype "passive"))
    )
    (net (code "90") (name "Net-(Q6A-B)") (class "Default")
      (node (ref "Q6") (pin "1") (pinfunction "B_1") (pintype "passive"))
      (node (ref "Q6") (pin "3") (pinfunction "B_3") (pintype "passive"))
      (node (ref "R16") (pin "1") (pinfunction "1_1") (pintype "passive"))
      (node (ref "R17") (pin "2") (pinfunction "2_2") (pintype "passive"))
    )
    (net (code "91") (name "Net-(Q7A-B)") (class "Default")
      (node (ref "LED4") (pin "A") (pinfunction "A_A") (pintype "passive"))
      (node (ref "Q7") (pin "1") (pinfunction "B_1") (pintype "passive"))
      (node (ref "Q7") (pin "3") (pinfunction "B_3") (pintype "passive"))
      (node (ref "R17") (pin "1") (pinfunction "1_1") (pintype "passive"))
    )
    (net (code "92") (name "Net-(Q7A-E)") (class "Default")
      (node (ref "Q7") (pin "5") (pinfunction "E_5") (pintype "passive"))
      (node (ref "R13") (pin "2") (pinfunction "2_2") (pintype "passive"))
    )
    (net (code "93") (name "Net-(Q7B-E)") (class "Default")
      (node (ref "Q7") (pin "2") (pinfunction "E_2") (pintype "passive"))
      (node (ref "R19") (pin "2") (pinfunction "2_2") (pintype "passive"))
    )
    (net (code "94") (name "Net-(Q8A-B)") (class "Default")
      (node (ref "LED3") (pin "C") (pinfunction "C_C") (pintype "passive"))
      (node (ref "Q8") (pin "1") (pinfunction "B_1") (pintype "passive"))
      (node (ref "Q8") (pin "3") (pinfunction "B_3") (pintype "passive"))
      (node (ref "R14") (pin "2") (pinfunction "2_2") (pintype "passive"))
    )
    (net (code "95") (name "Net-(Q8A-E)") (class "Default")
      (node (ref "Q8") (pin "5") (pinfunction "E_5") (pintype "passive"))
      (node (ref "R18") (pin "1") (pinfunction "1_1") (pintype "passive"))
    )
    (net (code "96") (name "Net-(Q8B-E)") (class "Default")
      (node (ref "Q8") (pin "2") (pinfunction "E_2") (pintype "passive"))
      (node (ref "R12") (pin "1") (pinfunction "1_1") (pintype "passive"))
    )
    (net (code "97") (name "Net-(Q9-PadE)") (class "Default")
      (node (ref "Q9") (pin "E") (pinfunction "E_E") (pintype "passive"))
      (node (ref "R25") (pin "1") (pinfunction "1_1") (pintype "passive"))
    )
    (net (code "98") (name "Net-(Q10-PadE)") (class "Default")
      (node (ref "Q10") (pin "E") (pinfunction "E_E") (pintype "passive"))
      (node (ref "R24") (pin "2") (pinfunction "2_2") (pintype "passive"))
    )
    (net (code "99") (name "Net-(Q11-PadC)") (class "Default")
      (node (ref "Q11") (pin "C") (pinfunction "C_C") (pintype "passive"))
      (node (ref "R24") (pin "1") (pinfunction "1_1") (pintype "passive"))
      (node (ref "R27") (pin "2") (pinfunction "2_2") (pintype "passive"))
      (node (ref "R32") (pin "2") (pinfunction "2_2") (pintype "passive"))
    )
    (net (code "100") (name "Net-(Q11-PadE)") (class "Default")
      (node (ref "Q11") (pin "E") (pinfunction "E_E") (pintype "passive"))
      (node (ref "R23") (pin "1") (pinfunction "1_1") (pintype "passive"))
    )
    (net (code "101") (name "Net-(Q12-PadC)") (class "Default")
      (node (ref "Q12") (pin "C") (pinfunction "C_C") (pintype "passive"))
      (node (ref "R25") (pin "2") (pinfunction "2_2") (pintype "passive"))
      (node (ref "R28") (pin "1") (pinfunction "1_1") (pintype "passive"))
      (node (ref "R33") (pin "1") (pinfunction "1_1") (pintype "passive"))
    )
    (net (code "102") (name "Net-(Q12-PadE)") (class "Default")
      (node (ref "Q12") (pin "E") (pinfunction "E_E") (pintype "passive"))
      (node (ref "R26") (pin "2") (pinfunction "2_2") (pintype "passive"))
    )
    (net (code "103") (name "Net-(Q13-PadB)") (class "Default")
      (node (ref "Q13") (pin "B") (pinfunction "B_B") (pintype "passive"))
      (node (ref "R27") (pin "1") (pinfunction "1_1") (pintype "passive"))
    )
    (net (code "104") (name "Net-(Q13-PadE)") (class "Default")
      (node (ref "Q13") (pin "E") (pinfunction "E_E") (pintype "passive"))
      (node (ref "R30") (pin "2") (pinfunction "2_2") (pintype "passive"))
    )
    (net (code "105") (name "Net-(Q14-PadB)") (class "Default")
      (node (ref "Q14") (pin "B") (pinfunction "B_B") (pintype "passive"))
      (node (ref "R28") (pin "2") (pinfunction "2_2") (pintype "passive"))
    )
    (net (code "106") (name "Net-(Q14-PadE)") (class "Default")
      (node (ref "Q14") (pin "E") (pinfunction "E_E") (pintype "passive"))
      (node (ref "R31") (pin "1") (pinfunction "1_1") (pintype "passive"))
    )
    (net (code "107") (name "Net-(Q15-PadB)") (class "Default")
      (node (ref "Q15") (pin "B") (pinfunction "B_B") (pintype "passive"))
      (node (ref "R32") (pin "1") (pinfunction "1_1") (pintype "passive"))
    )
    (net (code "108") (name "Net-(Q15-PadE)") (class "Default")
      (node (ref "Q15") (pin "E") (pinfunction "E_E") (pintype "passive"))
      (node (ref "R34") (pin "2") (pinfunction "2_2") (pintype "passive"))
    )
    (net (code "109") (name "Net-(Q16-PadB)") (class "Default")
      (node (ref "Q16") (pin "B") (pinfunction "B_B") (pintype "passive"))
      (node (ref "R33") (pin "2") (pinfunction "2_2") (pintype "passive"))
    )
    (net (code "110") (name "Net-(Q16-PadE)") (class "Default")
      (node (ref "Q16") (pin "E") (pinfunction "E_E") (pintype "passive"))
      (node (ref "R35") (pin "1") (pinfunction "1_1") (pintype "passive"))
    )
    (net (code "111") (name "Net-(Q17-PadE)") (class "Default")
      (node (ref "Q17") (pin "E") (pinfunction "E_E") (pintype "passive"))
      (node (ref "R40") (pin "1") (pinfunction "1_1") (pintype "passive"))
    )
    (net (code "112") (name "Net-(Q18-PadE)") (class "Default")
      (node (ref "Q18") (pin "E") (pinfunction "E_E") (pintype "passive"))
      (node (ref "R39") (pin "2") (pinfunction "2_2") (pintype "passive"))
    )
    (net (code "113") (name "Net-(Q19-PadC)") (class "Default")
      (node (ref "Q19") (pin "C") (pinfunction "C_C") (pintype "passive"))
      (node (ref "R39") (pin "1") (pinfunction "1_1") (pintype "passive"))
      (node (ref "R42") (pin "2") (pinfunction "2_2") (pintype "passive"))
      (node (ref "R47") (pin "2") (pinfunction "2_2") (pintype "passive"))
    )
    (net (code "114") (name "Net-(Q19-PadE)") (class "Default")
      (node (ref "Q19") (pin "E") (pinfunction "E_E") (pintype "passive"))
      (node (ref "R38") (pin "1") (pinfunction "1_1") (pintype "passive"))
    )
    (net (code "115") (name "Net-(Q20-PadC)") (class "Default")
      (node (ref "Q20") (pin "C") (pinfunction "C_C") (pintype "passive"))
      (node (ref "R40") (pin "2") (pinfunction "2_2") (pintype "passive"))
      (node (ref "R43") (pin "1") (pinfunction "1_1") (pintype "passive"))
      (node (ref "R48") (pin "1") (pinfunction "1_1") (pintype "passive"))
    )
    (net (code "116") (name "Net-(Q20-PadE)") (class "Default")
      (node (ref "Q20") (pin "E") (pinfunction "E_E") (pintype "passive"))
      (node (ref "R41") (pin "2") (pinfunction "2_2") (pintype "passive"))
    )
    (net (code "117") (name "Net-(Q21-PadB)") (class "Default")
      (node (ref "Q21") (pin "B") (pinfunction "B_B") (pintype "passive"))
      (node (ref "R42") (pin "1") (pinfunction "1_1") (pintype "passive"))
    )
    (net (code "118") (name "Net-(Q21-PadE)") (class "Default")
      (node (ref "Q21") (pin "E") (pinfunction "E_E") (pintype "passive"))
      (node (ref "R45") (pin "2") (pinfunction "2_2") (pintype "passive"))
    )
    (net (code "119") (name "Net-(Q22-PadB)") (class "Default")
      (node (ref "Q22") (pin "B") (pinfunction "B_B") (pintype "passive"))
      (node (ref "R43") (pin "2") (pinfunction "2_2") (pintype "passive"))
    )
    (net (code "120") (name "Net-(Q22-PadE)") (class "Default")
      (node (ref "Q22") (pin "E") (pinfunction "E_E") (pintype "passive"))
      (node (ref "R46") (pin "1") (pinfunction "1_1") (pintype "passive"))
    )
    (net (code "121") (name "Net-(Q23-PadB)") (class "Default")
      (node (ref "Q23") (pin "B") (pinfunction "B_B") (pintype "passive"))
      (node (ref "R47") (pin "1") (pinfunction "1_1") (pintype "passive"))
    )
    (net (code "122") (name "Net-(Q23-PadE)") (class "Default")
      (node (ref "Q23") (pin "E") (pinfunction "E_E") (pintype "passive"))
      (node (ref "R49") (pin "2") (pinfunction "2_2") (pintype "passive"))
    )
    (net (code "123") (name "Net-(Q24-PadB)") (class "Default")
      (node (ref "Q24") (pin "B") (pinfunction "B_B") (pintype "passive"))
      (node (ref "R48") (pin "2") (pinfunction "2_2") (pintype "passive"))
    )
    (net (code "124") (name "Net-(Q24-PadE)") (class "Default")
      (node (ref "Q24") (pin "E") (pinfunction "E_E") (pintype "passive"))
      (node (ref "R50") (pin "1") (pinfunction "1_1") (pintype "passive"))
    )
    (net (code "125") (name "Net-(Q25-PadE)") (class "Default")
      (node (ref "Q25") (pin "E") (pinfunction "E_E") (pintype "passive"))
      (node (ref "R54") (pin "1") (pinfunction "1_1") (pintype "passive"))
    )
    (net (code "126") (name "Net-(Q26-PadC)") (class "Default")
      (node (ref "Q26") (pin "C") (pinfunction "C_C") (pintype "passive"))
      (node (ref "Q31") (pin "E") (pinfunction "E_E") (pintype "passive"))
      (node (ref "R60") (pin "1") (pinfunction "1_1") (pintype "passive"))
    )
    (net (code "127") (name "Net-(Q26-PadE)") (class "Default")
      (node (ref "Q26") (pin "E") (pinfunction "E_E") (pintype "passive"))
      (node (ref "R55") (pin "1") (pinfunction "1_1") (pintype "passive"))
    )
    (net (code "128") (name "Net-(Q27-PadC)") (class "Default")
      (node (ref "Q27") (pin "C") (pinfunction "C_C") (pintype "passive"))
      (node (ref "Q30") (pin "E") (pinfunction "E_E") (pintype "passive"))
      (node (ref "R59") (pin "2") (pinfunction "2_2") (pintype "passive"))
    )
    (net (code "129") (name "Net-(Q27-PadE)") (class "Default")
      (node (ref "Q27") (pin "E") (pinfunction "E_E") (pintype "passive"))
      (node (ref "R56") (pin "2") (pinfunction "2_2") (pintype "passive"))
    )
    (net (code "130") (name "Net-(Q28-PadE)") (class "Default")
      (node (ref "Q28") (pin "E") (pinfunction "E_E") (pintype "passive"))
      (node (ref "R57") (pin "2") (pinfunction "2_2") (pintype "passive"))
    )
    (net (code "131") (name "Net-(Q29-PadC)") (class "Default")
      (node (ref "Q29") (pin "C") (pinfunction "C_C") (pintype "passive"))
      (node (ref "Q33") (pin "C") (pinfunction "C_C") (pintype "passive"))
      (node (ref "Q36") (pin "B") (pinfunction "B_B") (pintype "passive"))
    )
    (net (code "132") (name "Net-(Q29-PadE)") (class "Default")
      (node (ref "Q29") (pin "E") (pinfunction "E_E") (pintype "passive"))
      (node (ref "Q30") (pin "C") (pinfunction "C_C") (pintype "passive"))
    )
    (net (code "133") (name "Net-(Q31-PadC)") (class "Default")
      (node (ref "Q31") (pin "C") (pinfunction "C_C") (pintype "passive"))
      (node (ref "Q32") (pin "E") (pinfunction "E_E") (pintype "passive"))
    )
    (net (code "134") (name "Net-(Q32-PadC)") (class "Default")
      (node (ref "Q32") (pin "C") (pinfunction "C_C") (pintype "passive"))
      (node (ref "Q34") (pin "C") (pinfunction "C_C") (pintype "passive"))
      (node (ref "Q37") (pin "B") (pinfunction "B_B") (pintype "passive"))
    )
    (net (code "135") (name "Net-(Q33-PadB)") (class "Default")
      (node (ref "Q33") (pin "B") (pinfunction "B_B") (pintype "passive"))
      (node (ref "Q35") (pin "B") (pinfunction "B_B") (pintype "passive"))
      (node (ref "Q35") (pin "C") (pinfunction "C_C") (pintype "passive"))
      (node (ref "Q36") (pin "E") (pinfunction "E_E") (pintype "passive"))
    )
    (net (code "136") (name "Net-(Q33-PadE)") (class "Default")
      (node (ref "Q33") (pin "E") (pinfunction "E_E") (pintype "passive"))
      (node (ref "R58") (pin "1") (pinfunction "1_1") (pintype "passive"))
    )
    (net (code "137") (name "Net-(Q34-PadB)") (class "Default")
      (node (ref "Q34") (pin "B") (pinfunction "B_B") (pintype "passive"))
      (node (ref "Q37") (pin "E") (pinfunction "E_E") (pintype "passive"))
      (node (ref "Q38") (pin "B") (pinfunction "B_B") (pintype "passive"))
      (node (ref "Q38") (pin "C") (pinfunction "C_C") (pintype "passive"))
    )
    (net (code "138") (name "Net-(Q34-PadE)") (class "Default")
      (node (ref "Q34") (pin "E") (pinfunction "E_E") (pintype "passive"))
      (node (ref "R61") (pin "2") (pinfunction "2_2") (pintype "passive"))
    )
    (net (code "139") (name "Net-(Q36-PadC)") (class "Default")
      (node (ref "Q36") (pin "C") (pinfunction "C_C") (pintype "passive"))
      (node (ref "Q39") (pin "E") (pinfunction "E_E") (pintype "passive"))
    )
    (net (code "140") (name "Net-(Q37-PadC)") (class "Default")
      (node (ref "Q37") (pin "C") (pinfunction "C_C") (pintype "passive"))
      (node (ref "Q40") (pin "E") (pinfunction "E_E") (pintype "passive"))
    )
    (net (code "141") (name "Net-(Q41-PadB)") (class "Default")
      (node (ref "Q41") (pin "B") (pinfunction "B_B") (pintype "passive"))
      (node (ref "Q41") (pin "C") (pinfunction "C_C") (pintype "passive"))
      (node (ref "Q43") (pin "B") (pinfunction "B_B") (pintype "passive"))
      (node (ref "R68") (pin "2") (pinfunction "2_2") (pintype "passive"))
    )
    (net (code "142") (name "Net-(Q41-PadE)") (class "Default")
      (node (ref "Q41") (pin "E") (pinfunction "E_E") (pintype "passive"))
      (node (ref "R67") (pin "1") (pinfunction "1_1") (pintype "passive"))
    )
    (net (code "143") (name "Net-(Q42-PadB)") (class "Default")
      (node (ref "Q42") (pin "B") (pinfunction "B_B") (pintype "passive"))
      (node (ref "Q42") (pin "C") (pinfunction "C_C") (pintype "passive"))
      (node (ref "Q44") (pin "B") (pinfunction "B_B") (pintype "passive"))
      (node (ref "R69") (pin "1") (pinfunction "1_1") (pintype "passive"))
    )
    (net (code "144") (name "Net-(Q42-PadE)") (class "Default")
      (node (ref "Q42") (pin "E") (pinfunction "E_E") (pintype "passive"))
      (node (ref "R70") (pin "2") (pinfunction "2_2") (pintype "passive"))
    )
    (net (code "145") (name "Net-(Q43-PadE)") (class "Default")
      (node (ref "Q43") (pin "E") (pinfunction "E_E") (pintype "passive"))
      (node (ref "R71") (pin "1") (pinfunction "1_1") (pintype "passive"))
    )
    (net (code "146") (name "Net-(Q44-PadE)") (class "Default")
      (node (ref "Q44") (pin "E") (pinfunction "E_E") (pintype "passive"))
      (node (ref "R72") (pin "2") (pinfunction "2_2") (pintype "passive"))
    )
    (net (code "147") (name "Net-(Q46-PadE)") (class "Default")
      (node (ref "Q46") (pin "E") (pinfunction "E_E") (pintype "passive"))
      (node (ref "Q48") (pin "B") (pinfunction "B_B") (pintype "passive"))
      (node (ref "R77") (pin "2") (pinfunction "2_2") (pintype "passive"))
    )
    (net (code "148") (name "Net-(Q47-PadE)") (class "Default")
      (node (ref "Q47") (pin "E") (pinfunction "E_E") (pintype "passive"))
      (node (ref "Q49") (pin "B") (pinfunction "B_B") (pintype "passive"))
      (node (ref "R77") (pin "1") (pinfunction "1_1") (pintype "passive"))
    )
    (net (code "149") (name "Net-(Q48-PadE)") (class "Default")
      (node (ref "Q48") (pin "E") (pinfunction "E_E") (pintype "passive"))
      (node (ref "Q50") (pin "B") (pinfunction "B_B") (pintype "passive"))
      (node (ref "R78") (pin "2") (pinfunction "2_2") (pintype "passive"))
    )
    (net (code "150") (name "Net-(Q49-PadE)") (class "Default")
      (node (ref "Q49") (pin "E") (pinfunction "E_E") (pintype "passive"))
      (node (ref "Q51") (pin "B") (pinfunction "B_B") (pintype "passive"))
      (node (ref "R78") (pin "1") (pinfunction "1_1") (pintype "passive"))
    )
    (net (code "151") (name "Net-(Q50-PadE)") (class "Default")
      (node (ref "Q50") (pin "E") (pinfunction "E_E") (pintype "passive"))
      (node (ref "R80") (pin "2") (pinfunction "2_2") (pintype "passive"))
    )
    (net (code "152") (name "Net-(Q51-PadE)") (class "Default")
      (node (ref "Q51") (pin "E") (pinfunction "E_E") (pintype "passive"))
      (node (ref "R81") (pin "1") (pinfunction "1_1") (pintype "passive"))
    )
    (net (code "153") (name "Net-(Q52-PadE)") (class "Default")
      (node (ref "Q52") (pin "E") (pinfunction "E_E") (pintype "passive"))
      (node (ref "R86") (pin "1") (pinfunction "1_1") (pintype "passive"))
    )
    (net (code "154") (name "Net-(Q53-PadC)") (class "Default")
      (node (ref "Q53") (pin "C") (pinfunction "C_C") (pintype "passive"))
      (node (ref "Q58") (pin "E") (pinfunction "E_E") (pintype "passive"))
      (node (ref "R92") (pin "1") (pinfunction "1_1") (pintype "passive"))
    )
    (net (code "155") (name "Net-(Q53-PadE)") (class "Default")
      (node (ref "Q53") (pin "E") (pinfunction "E_E") (pintype "passive"))
      (node (ref "R87") (pin "1") (pinfunction "1_1") (pintype "passive"))
    )
    (net (code "156") (name "Net-(Q54-PadC)") (class "Default")
      (node (ref "Q54") (pin "C") (pinfunction "C_C") (pintype "passive"))
      (node (ref "Q57") (pin "E") (pinfunction "E_E") (pintype "passive"))
      (node (ref "R91") (pin "2") (pinfunction "2_2") (pintype "passive"))
    )
    (net (code "157") (name "Net-(Q54-PadE)") (class "Default")
      (node (ref "Q54") (pin "E") (pinfunction "E_E") (pintype "passive"))
      (node (ref "R88") (pin "2") (pinfunction "2_2") (pintype "passive"))
    )
    (net (code "158") (name "Net-(Q55-PadE)") (class "Default")
      (node (ref "Q55") (pin "E") (pinfunction "E_E") (pintype "passive"))
      (node (ref "R89") (pin "2") (pinfunction "2_2") (pintype "passive"))
    )
    (net (code "159") (name "Net-(Q56-PadC)") (class "Default")
      (node (ref "Q56") (pin "C") (pinfunction "C_C") (pintype "passive"))
      (node (ref "Q60") (pin "C") (pinfunction "C_C") (pintype "passive"))
      (node (ref "Q63") (pin "B") (pinfunction "B_B") (pintype "passive"))
    )
    (net (code "160") (name "Net-(Q56-PadE)") (class "Default")
      (node (ref "Q56") (pin "E") (pinfunction "E_E") (pintype "passive"))
      (node (ref "Q57") (pin "C") (pinfunction "C_C") (pintype "passive"))
    )
    (net (code "161") (name "Net-(Q58-PadC)") (class "Default")
      (node (ref "Q58") (pin "C") (pinfunction "C_C") (pintype "passive"))
      (node (ref "Q59") (pin "E") (pinfunction "E_E") (pintype "passive"))
    )
    (net (code "162") (name "Net-(Q59-PadC)") (class "Default")
      (node (ref "Q59") (pin "C") (pinfunction "C_C") (pintype "passive"))
      (node (ref "Q61") (pin "C") (pinfunction "C_C") (pintype "passive"))
      (node (ref "Q64") (pin "B") (pinfunction "B_B") (pintype "passive"))
    )
    (net (code "163") (name "Net-(Q60-PadB)") (class "Default")
      (node (ref "Q60") (pin "B") (pinfunction "B_B") (pintype "passive"))
      (node (ref "Q62") (pin "B") (pinfunction "B_B") (pintype "passive"))
      (node (ref "Q62") (pin "C") (pinfunction "C_C") (pintype "passive"))
      (node (ref "Q63") (pin "E") (pinfunction "E_E") (pintype "passive"))
    )
    (net (code "164") (name "Net-(Q60-PadE)") (class "Default")
      (node (ref "Q60") (pin "E") (pinfunction "E_E") (pintype "passive"))
      (node (ref "R90") (pin "1") (pinfunction "1_1") (pintype "passive"))
    )
    (net (code "165") (name "Net-(Q61-PadB)") (class "Default")
      (node (ref "Q61") (pin "B") (pinfunction "B_B") (pintype "passive"))
      (node (ref "Q64") (pin "E") (pinfunction "E_E") (pintype "passive"))
      (node (ref "Q65") (pin "B") (pinfunction "B_B") (pintype "passive"))
      (node (ref "Q65") (pin "C") (pinfunction "C_C") (pintype "passive"))
    )
    (net (code "166") (name "Net-(Q61-PadE)") (class "Default")
      (node (ref "Q61") (pin "E") (pinfunction "E_E") (pintype "passive"))
      (node (ref "R93") (pin "2") (pinfunction "2_2") (pintype "passive"))
    )
    (net (code "167") (name "Net-(Q63-PadC)") (class "Default")
      (node (ref "Q63") (pin "C") (pinfunction "C_C") (pintype "passive"))
      (node (ref "Q66") (pin "E") (pinfunction "E_E") (pintype "passive"))
    )
    (net (code "168") (name "Net-(Q64-PadC)") (class "Default")
      (node (ref "Q64") (pin "C") (pinfunction "C_C") (pintype "passive"))
      (node (ref "Q67") (pin "E") (pinfunction "E_E") (pintype "passive"))
    )
    (net (code "169") (name "Net-(Q68-PadB)") (class "Default")
      (node (ref "Q68") (pin "B") (pinfunction "B_B") (pintype "passive"))
      (node (ref "Q68") (pin "C") (pinfunction "C_C") (pintype "passive"))
      (node (ref "Q70") (pin "B") (pinfunction "B_B") (pintype "passive"))
      (node (ref "R100") (pin "2") (pinfunction "2_2") (pintype "passive"))
    )
    (net (code "170") (name "Net-(Q68-PadE)") (class "Default")
      (node (ref "Q68") (pin "E") (pinfunction "E_E") (pintype "passive"))
      (node (ref "R99") (pin "1") (pinfunction "1_1") (pintype "passive"))
    )
    (net (code "171") (name "Net-(Q69-PadB)") (class "Default")
      (node (ref "Q69") (pin "B") (pinfunction "B_B") (pintype "passive"))
      (node (ref "Q69") (pin "C") (pinfunction "C_C") (pintype "passive"))
      (node (ref "Q71") (pin "B") (pinfunction "B_B") (pintype "passive"))
      (node (ref "R101") (pin "1") (pinfunction "1_1") (pintype "passive"))
    )
    (net (code "172") (name "Net-(Q69-PadE)") (class "Default")
      (node (ref "Q69") (pin "E") (pinfunction "E_E") (pintype "passive"))
      (node (ref "R102") (pin "2") (pinfunction "2_2") (pintype "passive"))
    )
    (net (code "173") (name "Net-(Q70-PadE)") (class "Default")
      (node (ref "Q70") (pin "E") (pinfunction "E_E") (pintype "passive"))
      (node (ref "R103") (pin "1") (pinfunction "1_1") (pintype "passive"))
    )
    (net (code "174") (name "Net-(Q71-PadE)") (class "Default")
      (node (ref "Q71") (pin "E") (pinfunction "E_E") (pintype "passive"))
      (node (ref "R104") (pin "2") (pinfunction "2_2") (pintype "passive"))
    )
    (net (code "175") (name "Net-(Q73-PadE)") (class "Default")
      (node (ref "Q73") (pin "E") (pinfunction "E_E") (pintype "passive"))
      (node (ref "Q75") (pin "B") (pinfunction "B_B") (pintype "passive"))
      (node (ref "R109") (pin "2") (pinfunction "2_2") (pintype "passive"))
    )
    (net (code "176") (name "Net-(Q74-PadE)") (class "Default")
      (node (ref "Q74") (pin "E") (pinfunction "E_E") (pintype "passive"))
      (node (ref "Q76") (pin "B") (pinfunction "B_B") (pintype "passive"))
      (node (ref "R109") (pin "1") (pinfunction "1_1") (pintype "passive"))
    )
    (net (code "177") (name "Net-(Q75-PadE)") (class "Default")
      (node (ref "Q75") (pin "E") (pinfunction "E_E") (pintype "passive"))
      (node (ref "Q77") (pin "B") (pinfunction "B_B") (pintype "passive"))
      (node (ref "R110") (pin "2") (pinfunction "2_2") (pintype "passive"))
    )
    (net (code "178") (name "Net-(Q76-PadE)") (class "Default")
      (node (ref "Q76") (pin "E") (pinfunction "E_E") (pintype "passive"))
      (node (ref "Q78") (pin "B") (pinfunction "B_B") (pintype "passive"))
      (node (ref "R110") (pin "1") (pinfunction "1_1") (pintype "passive"))
    )
    (net (code "179") (name "Net-(Q77-PadE)") (class "Default")
      (node (ref "Q77") (pin "E") (pinfunction "E_E") (pintype "passive"))
      (node (ref "R112") (pin "2") (pinfunction "2_2") (pintype "passive"))
    )
    (net (code "180") (name "Net-(Q78-PadE)") (class "Default")
      (node (ref "Q78") (pin "E") (pinfunction "E_E") (pintype "passive"))
      (node (ref "R113") (pin "1") (pinfunction "1_1") (pintype "passive"))
    )
    (net (code "181") (name "Net-(Q79-PadC)") (class "Default")
      (node (ref "Q79") (pin "C") (pinfunction "C_C") (pintype "passive"))
      (node (ref "Q81") (pin "B") (pinfunction "B_B") (pintype "passive"))
      (node (ref "Q81") (pin "C") (pinfunction "C_C") (pintype "passive"))
      (node (ref "Q83") (pin "B") (pinfunction "B_B") (pintype "passive"))
    )
    (net (code "182") (name "Net-(Q79-PadE)") (class "Default")
      (node (ref "Q79") (pin "E") (pinfunction "E_E") (pintype "passive"))
      (node (ref "R117") (pin "1") (pinfunction "1_1") (pintype "passive"))
    )
    (net (code "183") (name "Net-(Q80-PadC)") (class "Default")
      (node (ref "Q80") (pin "C") (pinfunction "C_C") (pintype "passive"))
      (node (ref "Q82") (pin "B") (pinfunction "B_B") (pintype "passive"))
      (node (ref "Q82") (pin "C") (pinfunction "C_C") (pintype "passive"))
      (node (ref "Q84") (pin "B") (pinfunction "B_B") (pintype "passive"))
    )
    (net (code "184") (name "Net-(Q80-PadE)") (class "Default")
      (node (ref "Q80") (pin "E") (pinfunction "E_E") (pintype "passive"))
      (node (ref "R118") (pin "2") (pinfunction "2_2") (pintype "passive"))
    )
    (net (code "185") (name "Net-(Q83-PadE)") (class "Default")
      (node (ref "Q83") (pin "E") (pinfunction "E_E") (pintype "passive"))
      (node (ref "R119") (pin "2") (pinfunction "2_2") (pintype "passive"))
    )
    (net (code "186") (name "Net-(Q84-PadE)") (class "Default")
      (node (ref "Q84") (pin "E") (pinfunction "E_E") (pintype "passive"))
      (node (ref "R122") (pin "1") (pinfunction "1_1") (pintype "passive"))
    )
    (net (code "187") (name "Net-(Q85-PadB)") (class "Default")
      (node (ref "Q85") (pin "B") (pinfunction "B_B") (pintype "passive"))
      (node (ref "R123") (pin "2") (pinfunction "2_2") (pintype "passive"))
    )
    (net (code "188") (name "Net-(Q85-PadE)") (class "Default")
      (node (ref "Q85") (pin "E") (pinfunction "E_E") (pintype "passive"))
      (node (ref "R120") (pin "2") (pinfunction "2_2") (pintype "passive"))
    )
    (net (code "189") (name "Net-(Q86-PadB)") (class "Default")
      (node (ref "Q86") (pin "B") (pinfunction "B_B") (pintype "passive"))
      (node (ref "R124") (pin "2") (pinfunction "2_2") (pintype "passive"))
    )
    (net (code "190") (name "Net-(Q86-PadE)") (class "Default")
      (node (ref "Q86") (pin "E") (pinfunction "E_E") (pintype "passive"))
      (node (ref "R121") (pin "1") (pinfunction "1_1") (pintype "passive"))
    )
    (net (code "191") (name "Net-(Q87-PadE)") (class "Default")
      (node (ref "Q87") (pin "E") (pinfunction "E_E") (pintype "passive"))
      (node (ref "Q89") (pin "B") (pinfunction "B_B") (pintype "passive"))
    )
    (net (code "192") (name "Net-(Q88-PadE)") (class "Default")
      (node (ref "Q88") (pin "E") (pinfunction "E_E") (pintype "passive"))
      (node (ref "Q90") (pin "B") (pinfunction "B_B") (pintype "passive"))
    )
    (net (code "193") (name "Net-(Q91-PadS)") (class "Default")
      (node (ref "Q91") (pin "S") (pinfunction "S_S") (pintype "passive"))
      (node (ref "R125") (pin "2") (pinfunction "2_2") (pintype "passive"))
    )
    (net (code "194") (name "Net-(Q92-PadS)") (class "Default")
      (node (ref "Q92") (pin "S") (pinfunction "S_S") (pintype "passive"))
      (node (ref "R126") (pin "2") (pinfunction "2_2") (pintype "passive"))
    )
    (net (code "195") (name "Net-(Q97-G)") (class "Default")
      (node (ref "Q97") (pin "4") (pinfunction "G_4") (pintype "passive"))
      (node (ref "U$2") (pin "2") (pinfunction "2_TG2_2") (pintype "bidirectional"))
    )
    (net (code "196") (name "Net-(Q98-G)") (class "Default")
      (node (ref "Q98") (pin "4") (pinfunction "G_4") (pintype "passive"))
      (node (ref "U$2") (pin "11") (pinfunction "7_TG1_11") (pintype "bidirectional"))
    )
    (net (code "197") (name "Net-(Q99-G)") (class "Default")
      (node (ref "Q99") (pin "4") (pinfunction "G_4") (pintype "passive"))
      (node (ref "U$2") (pin "5") (pinfunction "3_BG2_5") (pintype "bidirectional"))
    )
    (net (code "198") (name "Net-(Q100-G)") (class "Default")
      (node (ref "Q100") (pin "4") (pinfunction "G_4") (pintype "passive"))
      (node (ref "U$2") (pin "6") (pinfunction "4_BG1_6") (pintype "bidirectional"))
    )
    (net (code "199") (name "Net-(Q105-G)") (class "Default")
      (node (ref "Q105") (pin "4") (pinfunction "G_4") (pintype "passive"))
      (node (ref "U$4") (pin "2") (pinfunction "2_TG2_2") (pintype "bidirectional"))
    )
    (net (code "200") (name "Net-(Q106-G)") (class "Default")
      (node (ref "Q106") (pin "4") (pinfunction "G_4") (pintype "passive"))
      (node (ref "U$4") (pin "11") (pinfunction "7_TG1_11") (pintype "bidirectional"))
    )
    (net (code "201") (name "Net-(Q107-G)") (class "Default")
      (node (ref "Q107") (pin "4") (pinfunction "G_4") (pintype "passive"))
      (node (ref "U$4") (pin "5") (pinfunction "3_BG2_5") (pintype "bidirectional"))
    )
    (net (code "202") (name "Net-(Q108-G)") (class "Default")
      (node (ref "Q108") (pin "4") (pinfunction "G_4") (pintype "passive"))
      (node (ref "U$4") (pin "6") (pinfunction "4_BG1_6") (pintype "bidirectional"))
    )
    (net (code "203") (name "Net-(R59-Pad1)") (class "Default")
      (node (ref "R59") (pin "1") (pinfunction "1_1") (pintype "passive"))
      (node (ref "R60") (pin "2") (pinfunction "2_2") (pintype "passive"))
      (node (ref "R63") (pin "2") (pinfunction "2_2") (pintype "passive"))
      (node (ref "R66") (pin "1") (pinfunction "1_1") (pintype "passive"))
    )
    (net (code "204") (name "Net-(R74-A)") (class "Default")
      (node (ref "C18") (pin "2") (pinfunction "2_2") (pintype "passive"))
      (node (ref "C20") (pin "1") (pinfunction "1_1") (pintype "passive"))
      (node (ref "Q40") (pin "C") (pinfunction "C_C") (pintype "passive"))
      (node (ref "Q44") (pin "C") (pinfunction "C_C") (pintype "passive"))
      (node (ref "Q45") (pin "E") (pinfunction "E_E") (pintype "passive"))
      (node (ref "Q47") (pin "B") (pinfunction "B_B") (pintype "passive"))
      (node (ref "R74") (pin "1") (pinfunction "A_1") (pintype "passive"))
      (node (ref "R74") (pin "2") (pinfunction "S_2") (pintype "passive"))
      (node (ref "R76") (pin "2") (pinfunction "2_2") (pintype "passive"))
    )
    (net (code "205") (name "Net-(R74-E)") (class "Default")
      (node (ref "Q45") (pin "B") (pinfunction "B_B") (pintype "passive"))
      (node (ref "R73") (pin "1") (pinfunction "1_1") (pintype "passive"))
      (node (ref "R74") (pin "3") (pinfunction "E_3") (pintype "passive"))
    )
    (net (code "206") (name "Net-(R91-Pad1)") (class "Default")
      (node (ref "R91") (pin "1") (pinfunction "1_1") (pintype "passive"))
      (node (ref "R92") (pin "2") (pinfunction "2_2") (pintype "passive"))
      (node (ref "R95") (pin "2") (pinfunction "2_2") (pintype "passive"))
      (node (ref "R98") (pin "1") (pinfunction "1_1") (pintype "passive"))
    )
    (net (code "207") (name "Net-(R106-A)") (class "Default")
      (node (ref "C28") (pin "2") (pinfunction "2_2") (pintype "passive"))
      (node (ref "C30") (pin "1") (pinfunction "1_1") (pintype "passive"))
      (node (ref "Q67") (pin "C") (pinfunction "C_C") (pintype "passive"))
      (node (ref "Q71") (pin "C") (pinfunction "C_C") (pintype "passive"))
      (node (ref "Q72") (pin "E") (pinfunction "E_E") (pintype "passive"))
      (node (ref "Q74") (pin "B") (pinfunction "B_B") (pintype "passive"))
      (node (ref "R106") (pin "1") (pinfunction "A_1") (pintype "passive"))
      (node (ref "R106") (pin "2") (pinfunction "S_2") (pintype "passive"))
      (node (ref "R108") (pin "2") (pinfunction "2_2") (pintype "passive"))
    )
    (net (code "208") (name "Net-(R106-E)") (class "Default")
      (node (ref "Q72") (pin "B") (pinfunction "B_B") (pintype "passive"))
      (node (ref "R105") (pin "1") (pinfunction "1_1") (pintype "passive"))
      (node (ref "R106") (pin "3") (pinfunction "E_3") (pintype "passive"))
    )
    (net (code "209") (name "Net-(U$1-FILTER)") (class "Default")
      (node (ref "C63") (pin "1") (pinfunction "1_1") (pintype "passive"))
      (node (ref "U$1") (pin "6") (pinfunction "FILTER_6") (pintype "bidirectional"))
    )
    (net (code "210") (name "Net-(U$3-FILTER)") (class "Default")
      (node (ref "C62") (pin "1") (pinfunction "1_1") (pintype "passive"))
      (node (ref "U$3") (pin "6") (pinfunction "FILTER_6") (pintype "bidirectional"))
    )
    (net (code "211") (name "Net-(U$5-BUF)") (class "Default")
      (node (ref "R138") (pin "2") (pinfunction "2_2") (pintype "passive"))
      (node (ref "U$5") (pin "8") (pinfunction "BUF_8") (pintype "bidirectional"))
    )
    (net (code "212") (name "Net-(U$5-EN)") (class "Default")
      (node (ref "SJ1") (pin "1") (pinfunction "1_1") (pintype "passive"))
      (node (ref "U$5") (pin "2") (pinfunction "EN_2") (pintype "bidirectional"))
    )
    (net (code "213") (name "Net-(U$5-FB+)") (class "Default")
      (node (ref "C71") (pin "2") (pinfunction "2_2") (pintype "passive"))
      (node (ref "R136") (pin "1") (pinfunction "1_1") (pintype "passive"))
      (node (ref "R137") (pin "2") (pinfunction "2_2") (pintype "passive"))
      (node (ref "U$5") (pin "9") (pinfunction "FB+_9") (pintype "bidirectional"))
    )
    (net (code "214") (name "Net-(U$5-FB-)") (class "Default")
      (node (ref "C72") (pin "1") (pinfunction "1_1") (pintype "passive"))
      (node (ref "R138") (pin "1") (pinfunction "1_1") (pintype "passive"))
      (node (ref "R139") (pin "2") (pinfunction "2_2") (pintype "passive"))
      (node (ref "U$5") (pin "7") (pinfunction "FB-_7") (pintype "bidirectional"))
    )
    (net (code "215") (name "Net-(U$5-NR{slash}SS)") (class "Default")
      (node (ref "C2") (pin "1") (pinfunction "1_1") (pintype "passive"))
      (node (ref "U$5") (pin "3") (pinfunction "NR/SS_3") (pintype "bidirectional"))
    )
    (net (code "216") (name "OUT+") (class "Default")
      (node (ref "C1") (pin "1") (pinfunction "1_1") (pintype "passive"))
      (node (ref "PAD1") (pin "P$1") (pinfunction "P$1_P$1") (pintype "bidirectional"))
      (node (ref "R66") (pin "2") (pinfunction "2_2") (pintype "passive"))
      (node (ref "R80") (pin "1") (pinfunction "1_1") (pintype "passive"))
      (node (ref "R81") (pin "2") (pinfunction "2_2") (pintype "passive"))
      (node (ref "R82") (pin "1") (pinfunction "1_1") (pintype "passive"))
    )
    (net (code "217") (name "OUT-") (class "Default")
      (node (ref "PAD2") (pin "P$1") (pinfunction "P$1_P$1") (pintype "bidirectional"))
      (node (ref "R112") (pin "1") (pinfunction "1_1") (pintype "passive"))
      (node (ref "R113") (pin "2") (pinfunction "2_2") (pintype "passive"))
      (node (ref "R114") (pin "1") (pinfunction "1_1") (pintype "passive"))
      (node (ref "R133") (pin "2") (pinfunction "2_2") (pintype "passive"))
      (node (ref "R98") (pin "2") (pinfunction "2_2") (pintype "passive"))
    )
    (net (code "218") (name "UOUT+") (class "Default")
      (node (ref "Q10") (pin "B") (pinfunction "B_B") (pintype "passive"))
      (node (ref "Q5") (pin "6") (pinfunction "C_6") (pintype "passive"))
      (node (ref "Q6") (pin "6") (pinfunction "C_6") (pintype "passive"))
      (node (ref "Q9") (pin "B") (pinfunction "B_B") (pintype "passive"))
      (node (ref "R11") (pin "2") (pinfunction "2_2") (pintype "passive"))
      (node (ref "R21") (pin "2") (pinfunction "2_2") (pintype "passive"))
    )
    (net (code "219") (name "UOUT-") (class "Default")
      (node (ref "Q17") (pin "B") (pinfunction "B_B") (pintype "passive"))
      (node (ref "Q18") (pin "B") (pinfunction "B_B") (pintype "passive"))
      (node (ref "Q5") (pin "4") (pinfunction "C_4") (pintype "passive"))
      (node (ref "Q6") (pin "4") (pinfunction "C_4") (pintype "passive"))
      (node (ref "R20") (pin "2") (pinfunction "2_2") (pintype "passive"))
      (node (ref "R36") (pin "2") (pinfunction "2_2") (pintype "passive"))
    )
    (net (code "220") (name "UV+") (class "Default")
      (node (ref "C57") (pin "1") (pinfunction "1_1") (pintype "passive"))
      (node (ref "Q97") (pin "5") (pinfunction "D_5") (pintype "passive"))
      (node (ref "Q97") (pin "6") (pinfunction "D_6") (pintype "passive"))
      (node (ref "Q97") (pin "7") (pinfunction "D_7") (pintype "passive"))
      (node (ref "Q97") (pin "8") (pinfunction "D_8") (pintype "passive"))
      (node (ref "Q97") (pin "TH") (pinfunction "D_TH") (pintype "passive"))
      (node (ref "Q98") (pin "5") (pinfunction "D_5") (pintype "passive"))
      (node (ref "Q98") (pin "6") (pinfunction "D_6") (pintype "passive"))
      (node (ref "Q98") (pin "7") (pinfunction "D_7") (pintype "passive"))
      (node (ref "Q98") (pin "8") (pinfunction "D_8") (pintype "passive"))
      (node (ref "Q98") (pin "TH") (pinfunction "D_TH") (pintype "passive"))
      (node (ref "U$1") (pin "1") (pinfunction "I+_1") (pintype "bidirectional"))
      (node (ref "U$1") (pin "2") (pinfunction "I+_2") (pintype "bidirectional"))
      (node (ref "U$2") (pin "9") (pinfunction "6_OUTP_9") (pintype "bidirectional"))
    )
    (net (code "221") (name "UV+IN") (class "Default")
      (node (ref "C37") (pin "+") (pinfunction "+_+") (pintype "passive"))
      (node (ref "C42") (pin "2") (pinfunction "2_2") (pintype "passive"))
      (node (ref "C58") (pin "2") (pinfunction "2_2") (pintype "passive"))
      (node (ref "D15") (pin "C") (pinfunction "C_C") (pintype "passive"))
      (node (ref "LED15") (pin "A") (pinfunction "A_A") (pintype "passive"))
      (node (ref "Q87") (pin "C") (pinfunction "C_C") (pintype "passive"))
      (node (ref "Q89") (pin "C") (pinfunction "C_C") (pintype "passive"))
      (node (ref "R115") (pin "1") (pinfunction "1_1") (pintype "passive"))
      (node (ref "R119") (pin "1") (pinfunction "1_1") (pintype "passive"))
      (node (ref "U$1") (pin "3") (pinfunction "I-_3") (pintype "bidirectional"))
      (node (ref "U$1") (pin "4") (pinfunction "I-_4") (pintype "bidirectional"))
    )
    (net (code "222") (name "UV-") (class "Default")
      (node (ref "C59") (pin "2") (pinfunction "2_2") (pintype "passive"))
      (node (ref "Q107") (pin "1") (pinfunction "S_1") (pintype "passive"))
      (node (ref "Q107") (pin "2") (pinfunction "S_2") (pintype "passive"))
      (node (ref "Q107") (pin "3") (pinfunction "S_3") (pintype "passive"))
      (node (ref "Q108") (pin "1") (pinfunction "S_1") (pintype "passive"))
      (node (ref "Q108") (pin "2") (pinfunction "S_2") (pintype "passive"))
      (node (ref "Q108") (pin "3") (pinfunction "S_3") (pintype "passive"))
      (node (ref "U$3") (pin "3") (pinfunction "I-_3") (pintype "bidirectional"))
      (node (ref "U$3") (pin "4") (pinfunction "I-_4") (pintype "bidirectional"))
      (node (ref "U$4") (pin "7") (pinfunction "5_OUTN_7") (pintype "bidirectional"))
      (node (ref "U$4") (pin "EXP") (pinfunction "5_OUTN_EXP") (pintype "bidirectional"))
    )
    (net (code "223") (name "UV-IN") (class "Default")
      (node (ref "C38") (pin "-") (pinfunction "-_-") (pintype "passive"))
      (node (ref "C39") (pin "1") (pinfunction "1_1") (pintype "passive"))
      (node (ref "C60") (pin "1") (pinfunction "1_1") (pintype "passive"))
      (node (ref "D16") (pin "A") (pinfunction "A_A") (pintype "passive"))
      (node (ref "LED16") (pin "C") (pinfunction "C_C") (pintype "passive"))
      (node (ref "Q88") (pin "C") (pinfunction "C_C") (pintype "passive"))
      (node (ref "Q90") (pin "C") (pinfunction "C_C") (pintype "passive"))
      (node (ref "R116") (pin "2") (pinfunction "2_2") (pintype "passive"))
      (node (ref "R122") (pin "2") (pinfunction "2_2") (pintype "passive"))
      (node (ref "U$3") (pin "1") (pinfunction "I+_1") (pintype "bidirectional"))
      (node (ref "U$3") (pin "2") (pinfunction "I+_2") (pintype "bidirectional"))
    )
    (net (code "224") (name "V+") (class "Default")
      (node (ref "C11") (pin "1") (pinfunction "1_1") (pintype "passive"))
      (node (ref "C25") (pin "+") (pinfunction "+_+") (pintype "passive"))
      (node (ref "C35") (pin "+") (pinfunction "+_+") (pintype "passive"))
      (node (ref "C45") (pin "2") (pinfunction "2_2") (pintype "passive"))
      (node (ref "C5") (pin "+") (pinfunction "+_+") (pintype "passive"))
      (node (ref "C53") (pin "1") (pinfunction "1_1") (pintype "passive"))
      (node (ref "C55") (pin "2") (pinfunction "2_2") (pintype "passive"))
      (node (ref "C66") (pin "1") (pinfunction "1_1") (pintype "passive"))
      (node (ref "C68") (pin "1") (pinfunction "1_1") (pintype "passive"))
      (node (ref "C7") (pin "+") (pinfunction "+_+") (pintype "passive"))
      (node (ref "C74") (pin "1") (pinfunction "1_1") (pintype "passive"))
      (node (ref "C9") (pin "1") (pinfunction "1_1") (pintype "passive"))
      (node (ref "D1") (pin "A") (pinfunction "A_A") (pintype "passive"))
      (node (ref "D15") (pin "A") (pinfunction "A_A") (pintype "passive"))
      (node (ref "D7") (pin "A") (pinfunction "A_A") (pintype "passive"))
      (node (ref "IC6") (pin "7") (pinfunction "V+_7") (pintype "power_in"))
      (node (ref "LED1") (pin "A") (pinfunction "A_A") (pintype "passive"))
      (node (ref "LED3") (pin "A") (pinfunction "A_A") (pintype "passive"))
      (node (ref "LED5") (pin "A") (pinfunction "A_A") (pintype "passive"))
      (node (ref "LED7") (pin "A") (pinfunction "A_A") (pintype "passive"))
      (node (ref "Q13") (pin "C") (pinfunction "C_C") (pintype "passive"))
      (node (ref "Q15") (pin "C") (pinfunction "C_C") (pintype "passive"))
      (node (ref "Q17") (pin "C") (pinfunction "C_C") (pintype "passive"))
      (node (ref "Q21") (pin "C") (pinfunction "C_C") (pintype "passive"))
      (node (ref "Q23") (pin "C") (pinfunction "C_C") (pintype "passive"))
      (node (ref "Q46") (pin "C") (pinfunction "C_C") (pintype "passive"))
      (node (ref "Q48") (pin "C") (pinfunction "C_C") (pintype "passive"))
      (node (ref "Q50") (pin "C") (pinfunction "C_C") (pintype "passive"))
      (node (ref "Q73") (pin "C") (pinfunction "C_C") (pintype "passive"))
      (node (ref "Q75") (pin "C") (pinfunction "C_C") (pintype "passive"))
      (node (ref "Q77") (pin "C") (pinfunction "C_C") (pintype "passive"))
      (node (ref "Q89") (pin "E") (pinfunction "E_E") (pintype "passive"))
      (node (ref "Q9") (pin "C") (pinfunction "C_C") (pintype "passive"))
      (node (ref "Q91") (pin "D") (pinfunction "D_D") (pintype "passive"))
      (node (ref "R103") (pin "2") (pinfunction "2_2") (pintype "passive"))
      (node (ref "R12") (pin "2") (pinfunction "2_2") (pintype "passive"))
      (node (ref "R127") (pin "2") (pinfunction "2_2") (pintype "passive"))
      (node (ref "R131") (pin "2") (pinfunction "2_2") (pintype "passive"))
      (node (ref "R141") (pin "2") (pinfunction "2_2") (pintype "passive"))
      (node (ref "R18") (pin "2") (pinfunction "2_2") (pintype "passive"))
      (node (ref "R23") (pin "2") (pinfunction "2_2") (pintype "passive"))
      (node (ref "R38") (pin "2") (pinfunction "2_2") (pintype "passive"))
      (node (ref "R5") (pin "2") (pinfunction "2_2") (pintype "passive"))
      (node (ref "R54") (pin "2") (pinfunction "2_2") (pintype "passive"))
      (node (ref "R58") (pin "2") (pinfunction "2_2") (pintype "passive"))
      (node (ref "R62") (pin "2") (pinfunction "2_2") (pintype "passive"))
      (node (ref "R67") (pin "2") (pinfunction "2_2") (pintype "passive"))
      (node (ref "R71") (pin "2") (pinfunction "2_2") (pintype "passive"))
      (node (ref "R86") (pin "2") (pinfunction "2_2") (pintype "passive"))
      (node (ref "R90") (pin "2") (pinfunction "2_2") (pintype "passive"))
      (node (ref "R94") (pin "2") (pinfunction "2_2") (pintype "passive"))
      (node (ref "R99") (pin "2") (pinfunction "2_2") (pintype "passive"))
      (node (ref "SJ1") (pin "2") (pinfunction "2_2") (pintype "passive"))
      (node (ref "U$5") (pin "1") (pinfunction "IN+_1") (pintype "bidirectional"))
    )
    (net (code "225") (name "V-") (class "Default")
      (node (ref "C10") (pin "2") (pinfunction "2_2") (pintype "passive"))
      (node (ref "C12") (pin "2") (pinfunction "2_2") (pintype "passive"))
      (node (ref "C26") (pin "-") (pinfunction "-_-") (pintype "passive"))
      (node (ref "C36") (pin "-") (pinfunction "-_-") (pintype "passive"))
      (node (ref "C46") (pin "1") (pinfunction "1_1") (pintype "passive"))
      (node (ref "C54") (pin "2") (pinfunction "2_2") (pintype "passive"))
      (node (ref "C56") (pin "1") (pinfunction "1_1") (pintype "passive"))
      (node (ref "C6") (pin "-") (pinfunction "-_-") (pintype "passive"))
      (node (ref "C65") (pin "1") (pinfunction "1_1") (pintype "passive"))
      (node (ref "C67") (pin "1") (pinfunction "1_1") (pintype "passive"))
      (node (ref "C75") (pin "2") (pinfunction "2_2") (pintype "passive"))
      (node (ref "C8") (pin "-") (pinfunction "-_-") (pintype "passive"))
      (node (ref "D10") (pin "C") (pinfunction "C_C") (pintype "passive"))
      (node (ref "D16") (pin "C") (pinfunction "C_C") (pintype "passive"))
      (node (ref "D4") (pin "C") (pinfunction "C_C") (pintype "passive"))
      (node (ref "IC5") (pin "4") (pinfunction "V-_4") (pintype "power_in"))
      (node (ref "LED2") (pin "C") (pinfunction "C_C") (pintype "passive"))
      (node (ref "LED4") (pin "C") (pinfunction "C_C") (pintype "passive"))
      (node (ref "LED6") (pin "C") (pinfunction "C_C") (pintype "passive"))
      (node (ref "LED8") (pin "C") (pinfunction "C_C") (pintype "passive"))
      (node (ref "Q10") (pin "C") (pinfunction "C_C") (pintype "passive"))
      (node (ref "Q14") (pin "C") (pinfunction "C_C") (pintype "passive"))
      (node (ref "Q16") (pin "C") (pinfunction "C_C") (pintype "passive"))
      (node (ref "Q18") (pin "C") (pinfunction "C_C") (pintype "passive"))
      (node (ref "Q22") (pin "C") (pinfunction "C_C") (pintype "passive"))
      (node (ref "Q24") (pin "C") (pinfunction "C_C") (pintype "passive"))
      (node (ref "Q47") (pin "C") (pinfunction "C_C") (pintype "passive"))
      (node (ref "Q49") (pin "C") (pinfunction "C_C") (pintype "passive"))
      (node (ref "Q51") (pin "C") (pinfunction "C_C") (pintype "passive"))
      (node (ref "Q74") (pin "C") (pinfunction "C_C") (pintype "passive"))
      (node (ref "Q76") (pin "C") (pinfunction "C_C") (pintype "passive"))
      (node (ref "Q78") (pin "C") (pinfunction "C_C") (pintype "passive"))
      (node (ref "Q90") (pin "E") (pinfunction "E_E") (pintype "passive"))
      (node (ref "Q92") (pin "G") (pinfunction "G_G") (pintype "passive"))
      (node (ref "R102") (pin "1") (pinfunction "1_1") (pintype "passive"))
      (node (ref "R104") (pin "1") (pinfunction "1_1") (pintype "passive"))
      (node (ref "R126") (pin "1") (pinfunction "1_1") (pintype "passive"))
      (node (ref "R13") (pin "1") (pinfunction "1_1") (pintype "passive"))
      (node (ref "R130") (pin "1") (pinfunction "1_1") (pintype "passive"))
      (node (ref "R132") (pin "1") (pinfunction "1_1") (pintype "passive"))
      (node (ref "R140") (pin "2") (pinfunction "2_2") (pintype "passive"))
      (node (ref "R19") (pin "1") (pinfunction "1_1") (pintype "passive"))
      (node (ref "R26") (pin "1") (pinfunction "1_1") (pintype "passive"))
      (node (ref "R41") (pin "1") (pinfunction "1_1") (pintype "passive"))
      (node (ref "R57") (pin "1") (pinfunction "1_1") (pintype "passive"))
      (node (ref "R61") (pin "1") (pinfunction "1_1") (pintype "passive"))
      (node (ref "R64") (pin "1") (pinfunction "1_1") (pintype "passive"))
      (node (ref "R7") (pin "1") (pinfunction "1_1") (pintype "passive"))
      (node (ref "R70") (pin "1") (pinfunction "1_1") (pintype "passive"))
      (node (ref "R72") (pin "1") (pinfunction "1_1") (pintype "passive"))
      (node (ref "R89") (pin "1") (pinfunction "1_1") (pintype "passive"))
      (node (ref "R93") (pin "1") (pinfunction "1_1") (pintype "passive"))
      (node (ref "R96") (pin "1") (pinfunction "1_1") (pintype "passive"))
      (node (ref "U$5") (pin "5") (pinfunction "IN-_5") (pintype "bidirectional"))
    )
    (net (code "226") (name "VS+") (class "Default")
      (node (ref "J1") (pin "2") (pinfunction "S_2") (pintype "passive"))
      (node (ref "U$1") (pin "7") (pinfunction "VOUT_7") (pintype "bidirectional"))
    )
    (net (code "227") (name "VS-") (class "Default")
      (node (ref "J2") (pin "2") (pinfunction "S_2") (pintype "passive"))
      (node (ref "U$3") (pin "7") (pinfunction "VOUT_7") (pintype "bidirectional"))
    )
    (net (code "228") (name "unconnected-(H1-PadP$1)") (class "Default")
      (node (ref "H1") (pin "P$1") (pinfunction "P$1_P$1") (pintype "bidirectional"))
    )
    (net (code "229") (name "unconnected-(H2-PadP$1)") (class "Default")
      (node (ref "H2") (pin "P$1") (pinfunction "P$1_P$1") (pintype "bidirectional"))
    )
    (net (code "230") (name "unconnected-(H3-PadP$1)") (class "Default")
      (node (ref "H3") (pin "P$1") (pinfunction "P$1_P$1") (pintype "bidirectional"))
    )
    (net (code "231") (name "unconnected-(H4-PadP$1)") (class "Default")
      (node (ref "H4") (pin "P$1") (pinfunction "P$1_P$1") (pintype "bidirectional"))
    )
    (net (code "232") (name "unconnected-(H5-PadP$1)") (class "Default")
      (node (ref "H5") (pin "P$1") (pinfunction "P$1_P$1") (pintype "bidirectional"))
    )
    (net (code "233") (name "unconnected-(H6-PadP$1)") (class "Default")
      (node (ref "H6") (pin "P$1") (pinfunction "P$1_P$1") (pintype "bidirectional"))
    )
    (net (code "234") (name "unconnected-(H7-PadP$1)") (class "Default")
      (node (ref "H7") (pin "P$1") (pinfunction "P$1_P$1") (pintype "bidirectional"))
    )
    (net (code "235") (name "unconnected-(H8-PadP$1)") (class "Default")
      (node (ref "H8") (pin "P$1") (pinfunction "P$1_P$1") (pintype "bidirectional"))
    )
    (net (code "236") (name "unconnected-(IC1-CMP1-Pad1)") (class "Default")
      (node (ref "IC1") (pin "1") (pinfunction "CMP1_1") (pintype "passive"))
    )
    (net (code "237") (name "unconnected-(IC2-CMP1-Pad1)") (class "Default")
      (node (ref "IC2") (pin "1") (pinfunction "CMP1_1") (pintype "passive"))
    )
    (net (code "238") (name "unconnected-(IC3-CMP1-Pad1)") (class "Default")
      (node (ref "IC3") (pin "1") (pinfunction "CMP1_1") (pintype "passive"))
    )
    (net (code "239") (name "unconnected-(IC3-CMP2-Pad8)") (class "Default")
      (node (ref "IC3") (pin "8") (pinfunction "CMP2_8") (pintype "passive"))
    )
    (net (code "240") (name "unconnected-(IC4-CMP1-Pad1)") (class "Default")
      (node (ref "IC4") (pin "1") (pinfunction "CMP1_1") (pintype "passive"))
    )
    (net (code "241") (name "unconnected-(IC4-CMP2-Pad8)") (class "Default")
      (node (ref "IC4") (pin "8") (pinfunction "CMP2_8") (pintype "passive"))
    )
    (net (code "242") (name "unconnected-(IC5-CMP1-Pad1)") (class "Default")
      (node (ref "IC5") (pin "1") (pinfunction "CMP1_1") (pintype "passive"))
    )
    (net (code "243") (name "unconnected-(IC5-CMP2-Pad8)") (class "Default")
      (node (ref "IC5") (pin "8") (pinfunction "CMP2_8") (pintype "passive"))
    )
    (net (code "244") (name "unconnected-(IC6-CMP1-Pad1)") (class "Default")
      (node (ref "IC6") (pin "1") (pinfunction "CMP1_1") (pintype "passive"))
    )
    (net (code "245") (name "unconnected-(IC6-CMP2-Pad8)") (class "Default")
      (node (ref "IC6") (pin "8") (pinfunction "CMP2_8") (pintype "passive"))
    )
  )
)
